# BeagleBone_Blue_3D.net
KiCad netlist of a schematic drawn in EAGLE
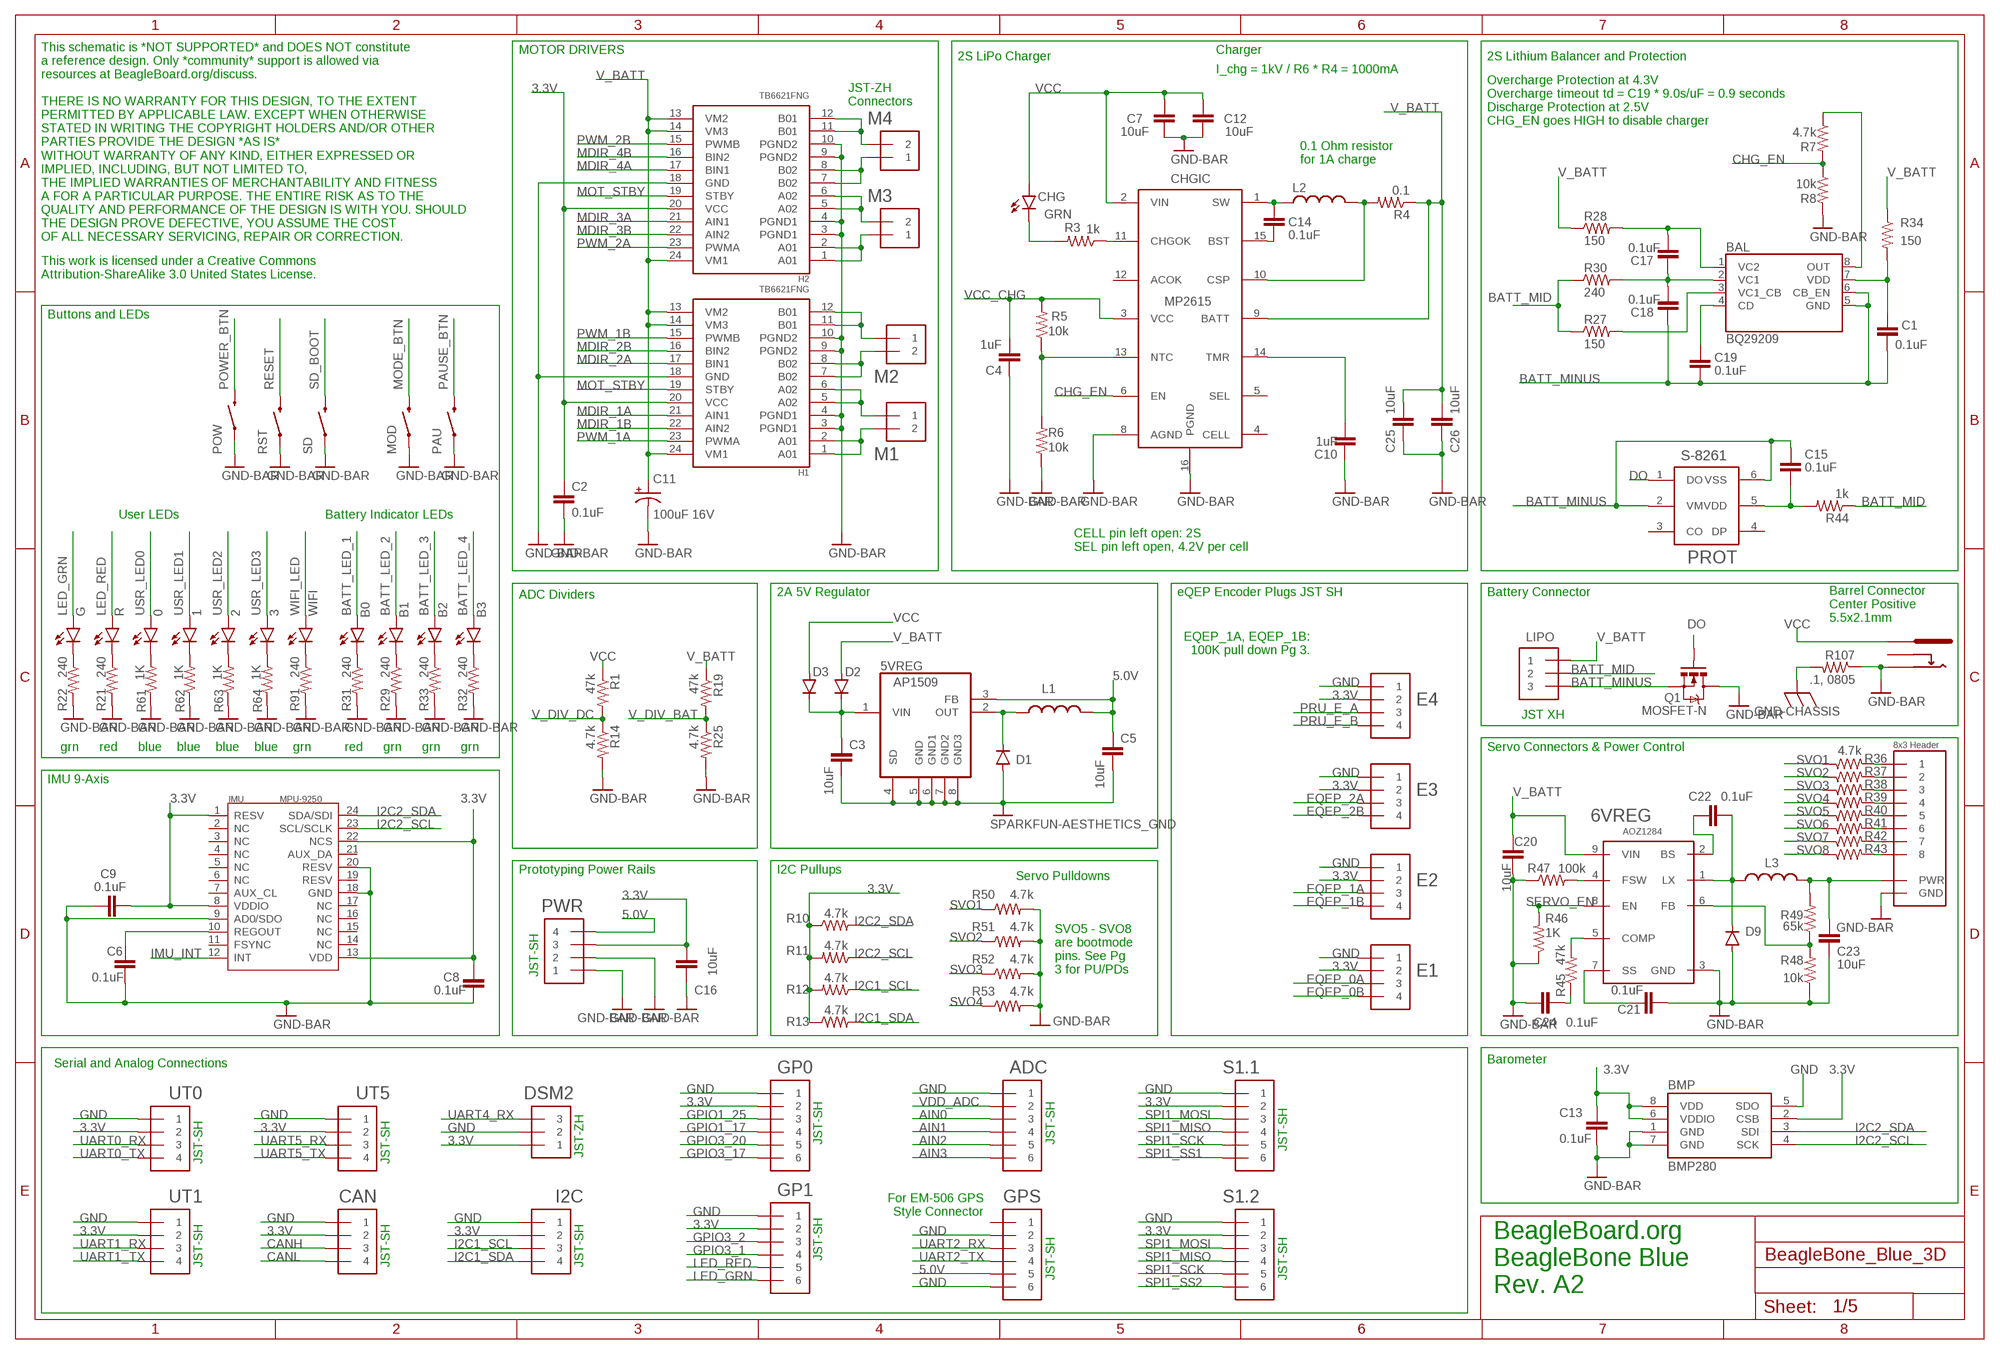
[diagram p0: schematic, sheet 1]
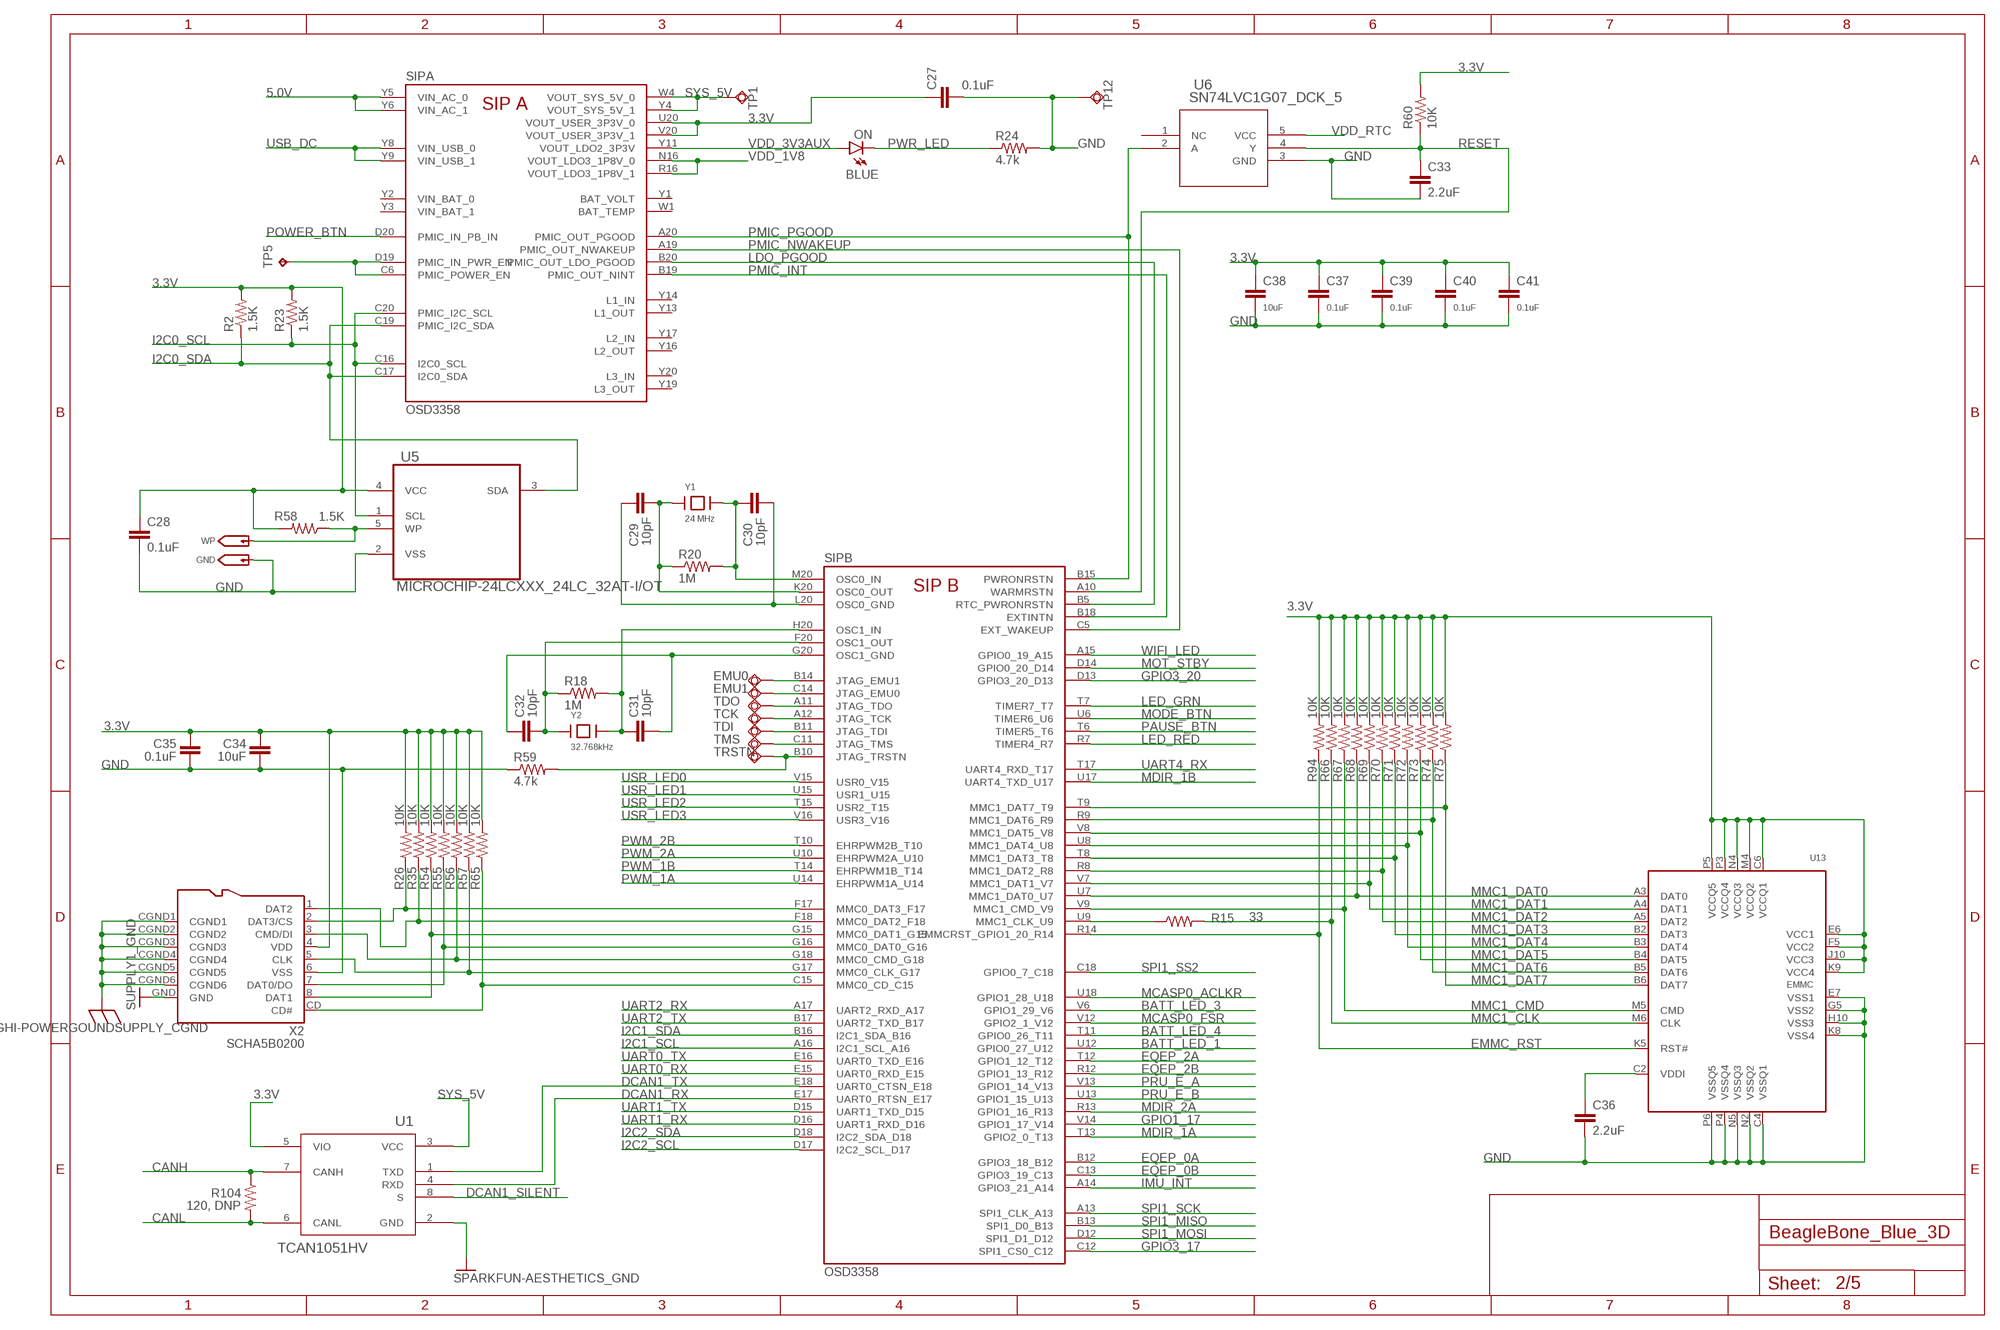
[diagram p1: schematic, sheet 2]
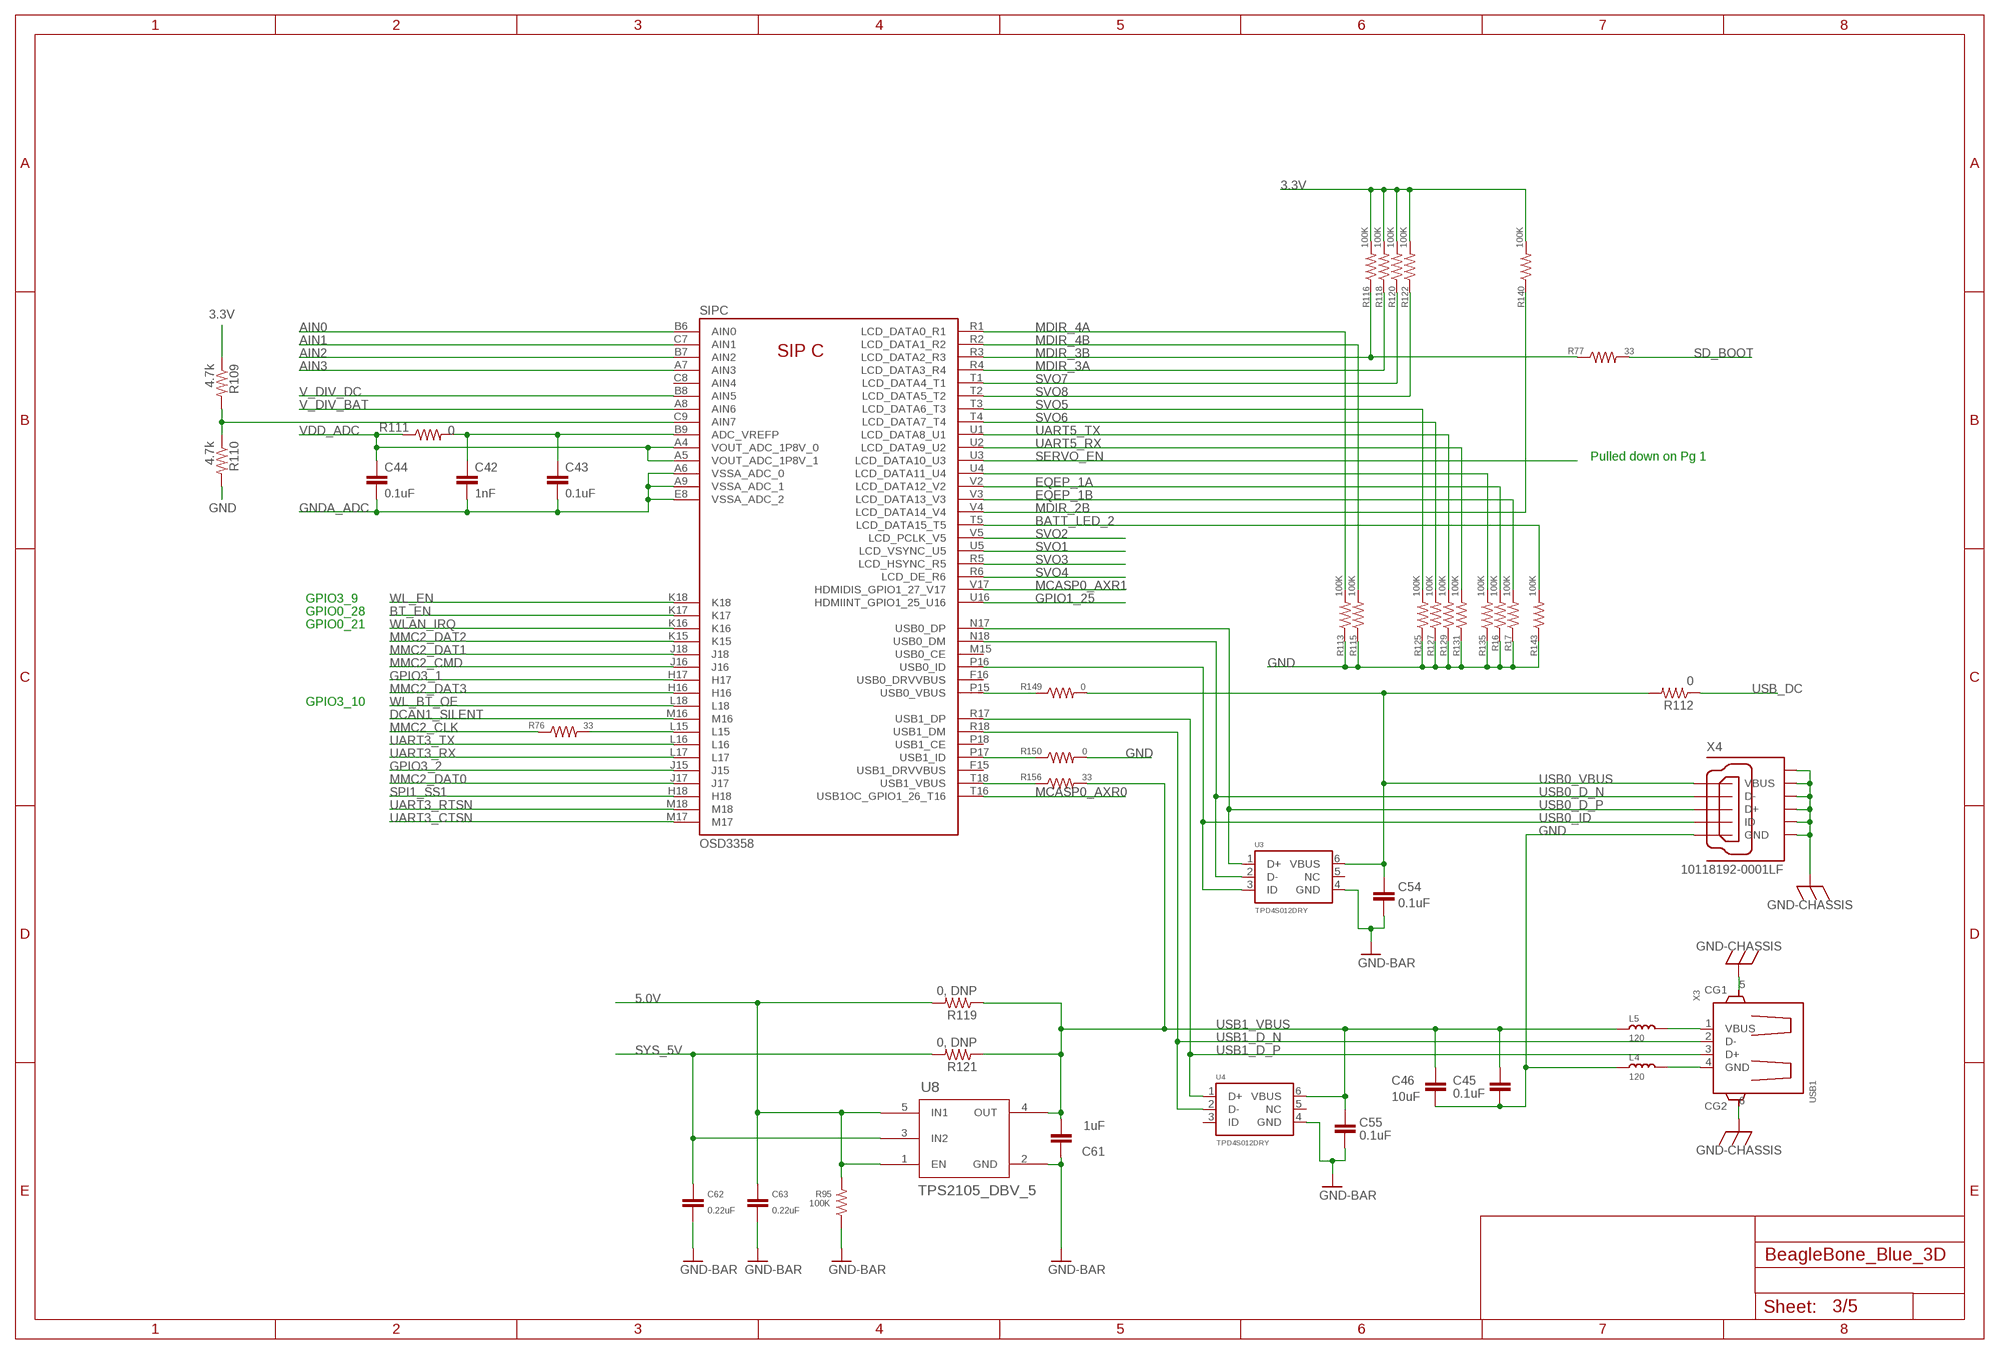
[diagram p2: schematic, sheet 3]
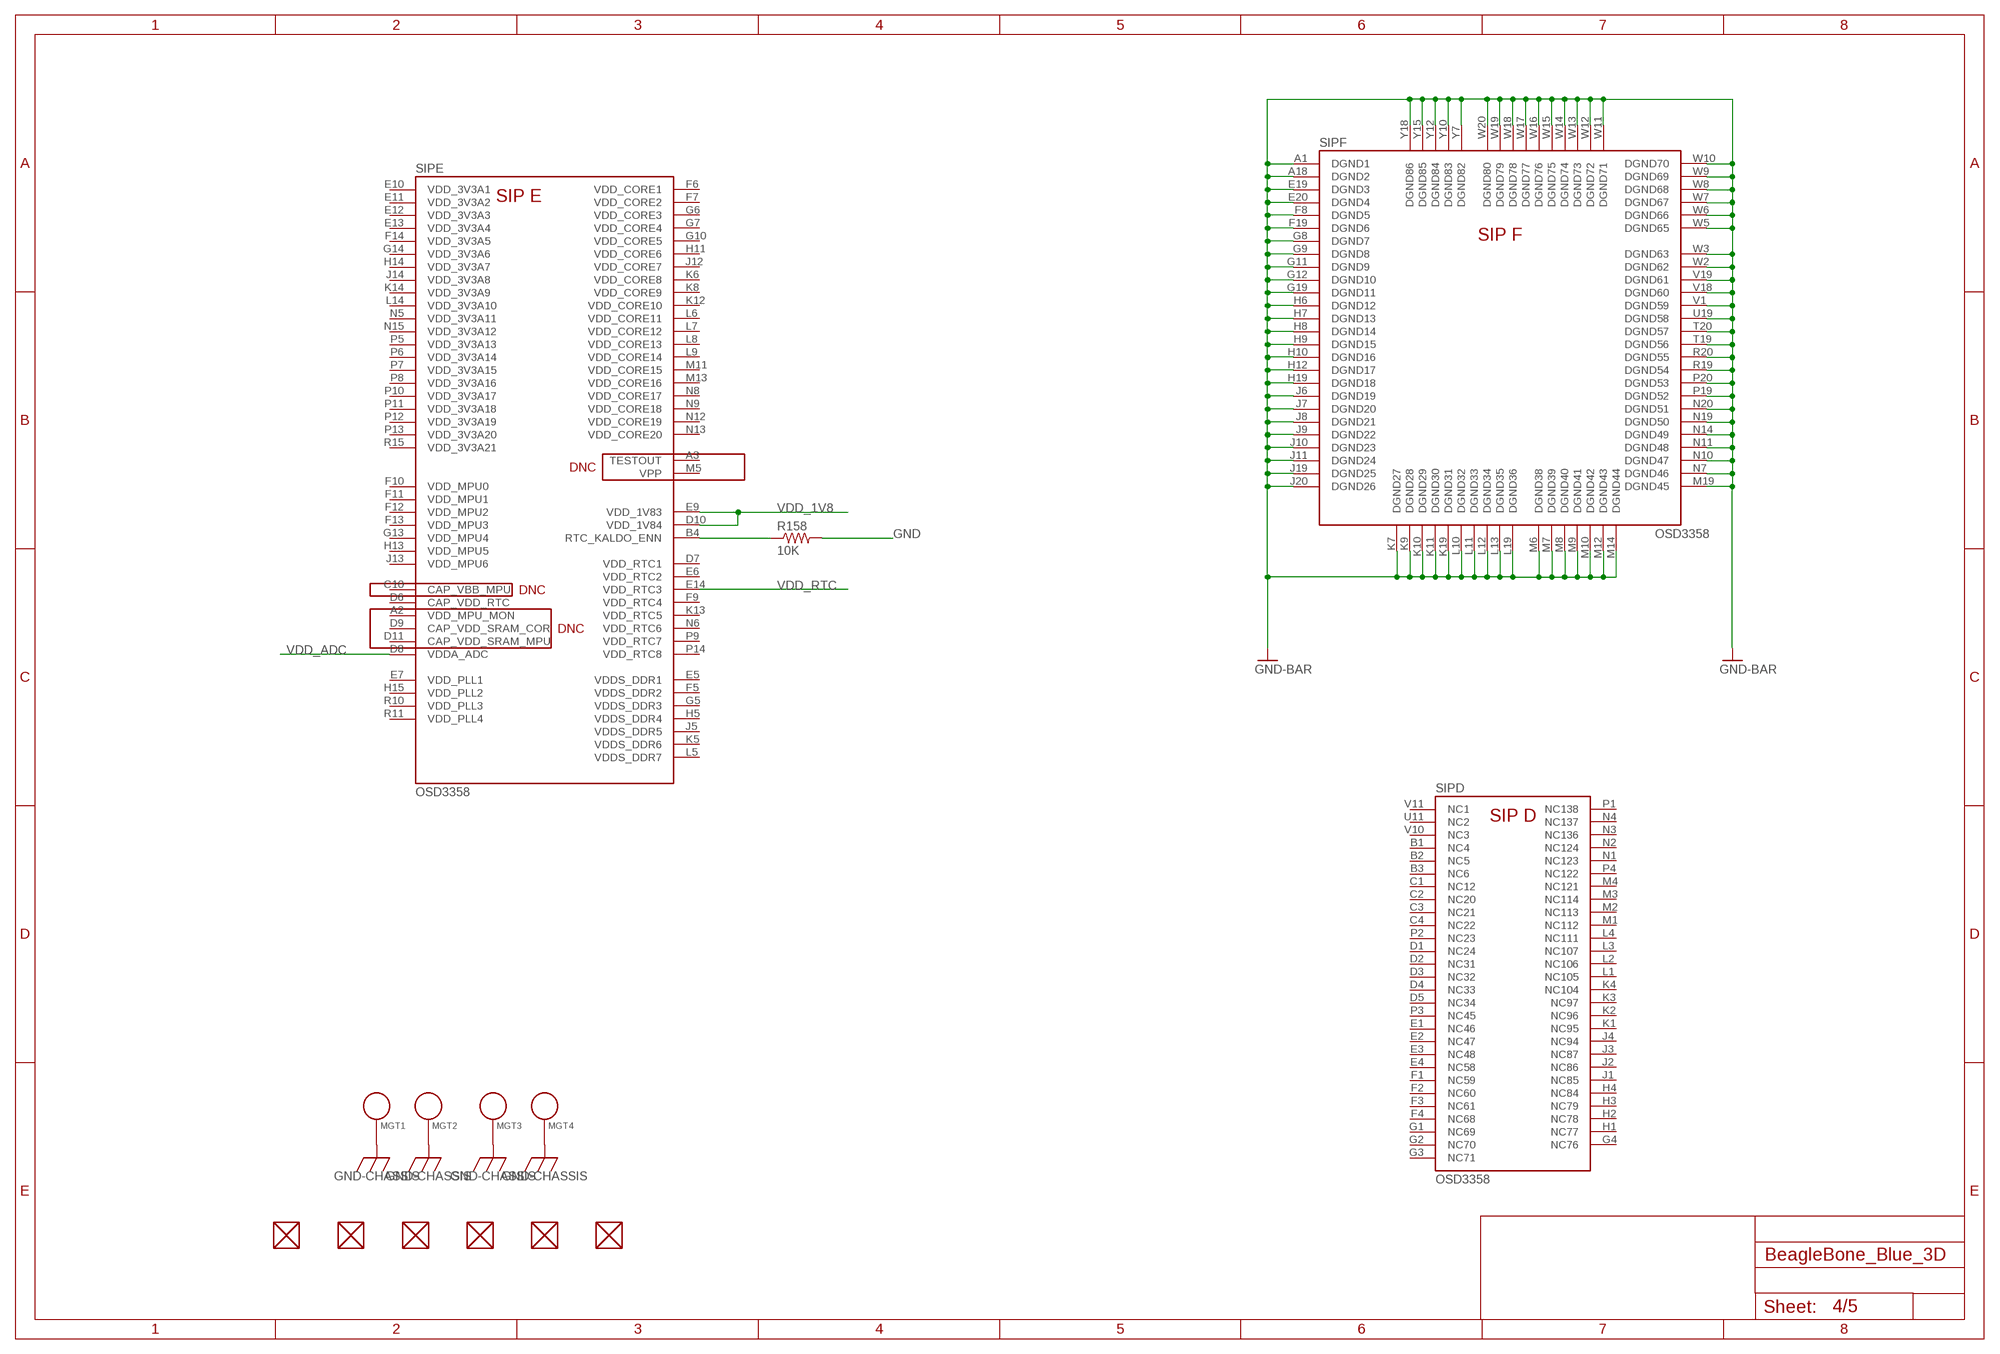
[diagram p3: schematic, sheet 4]
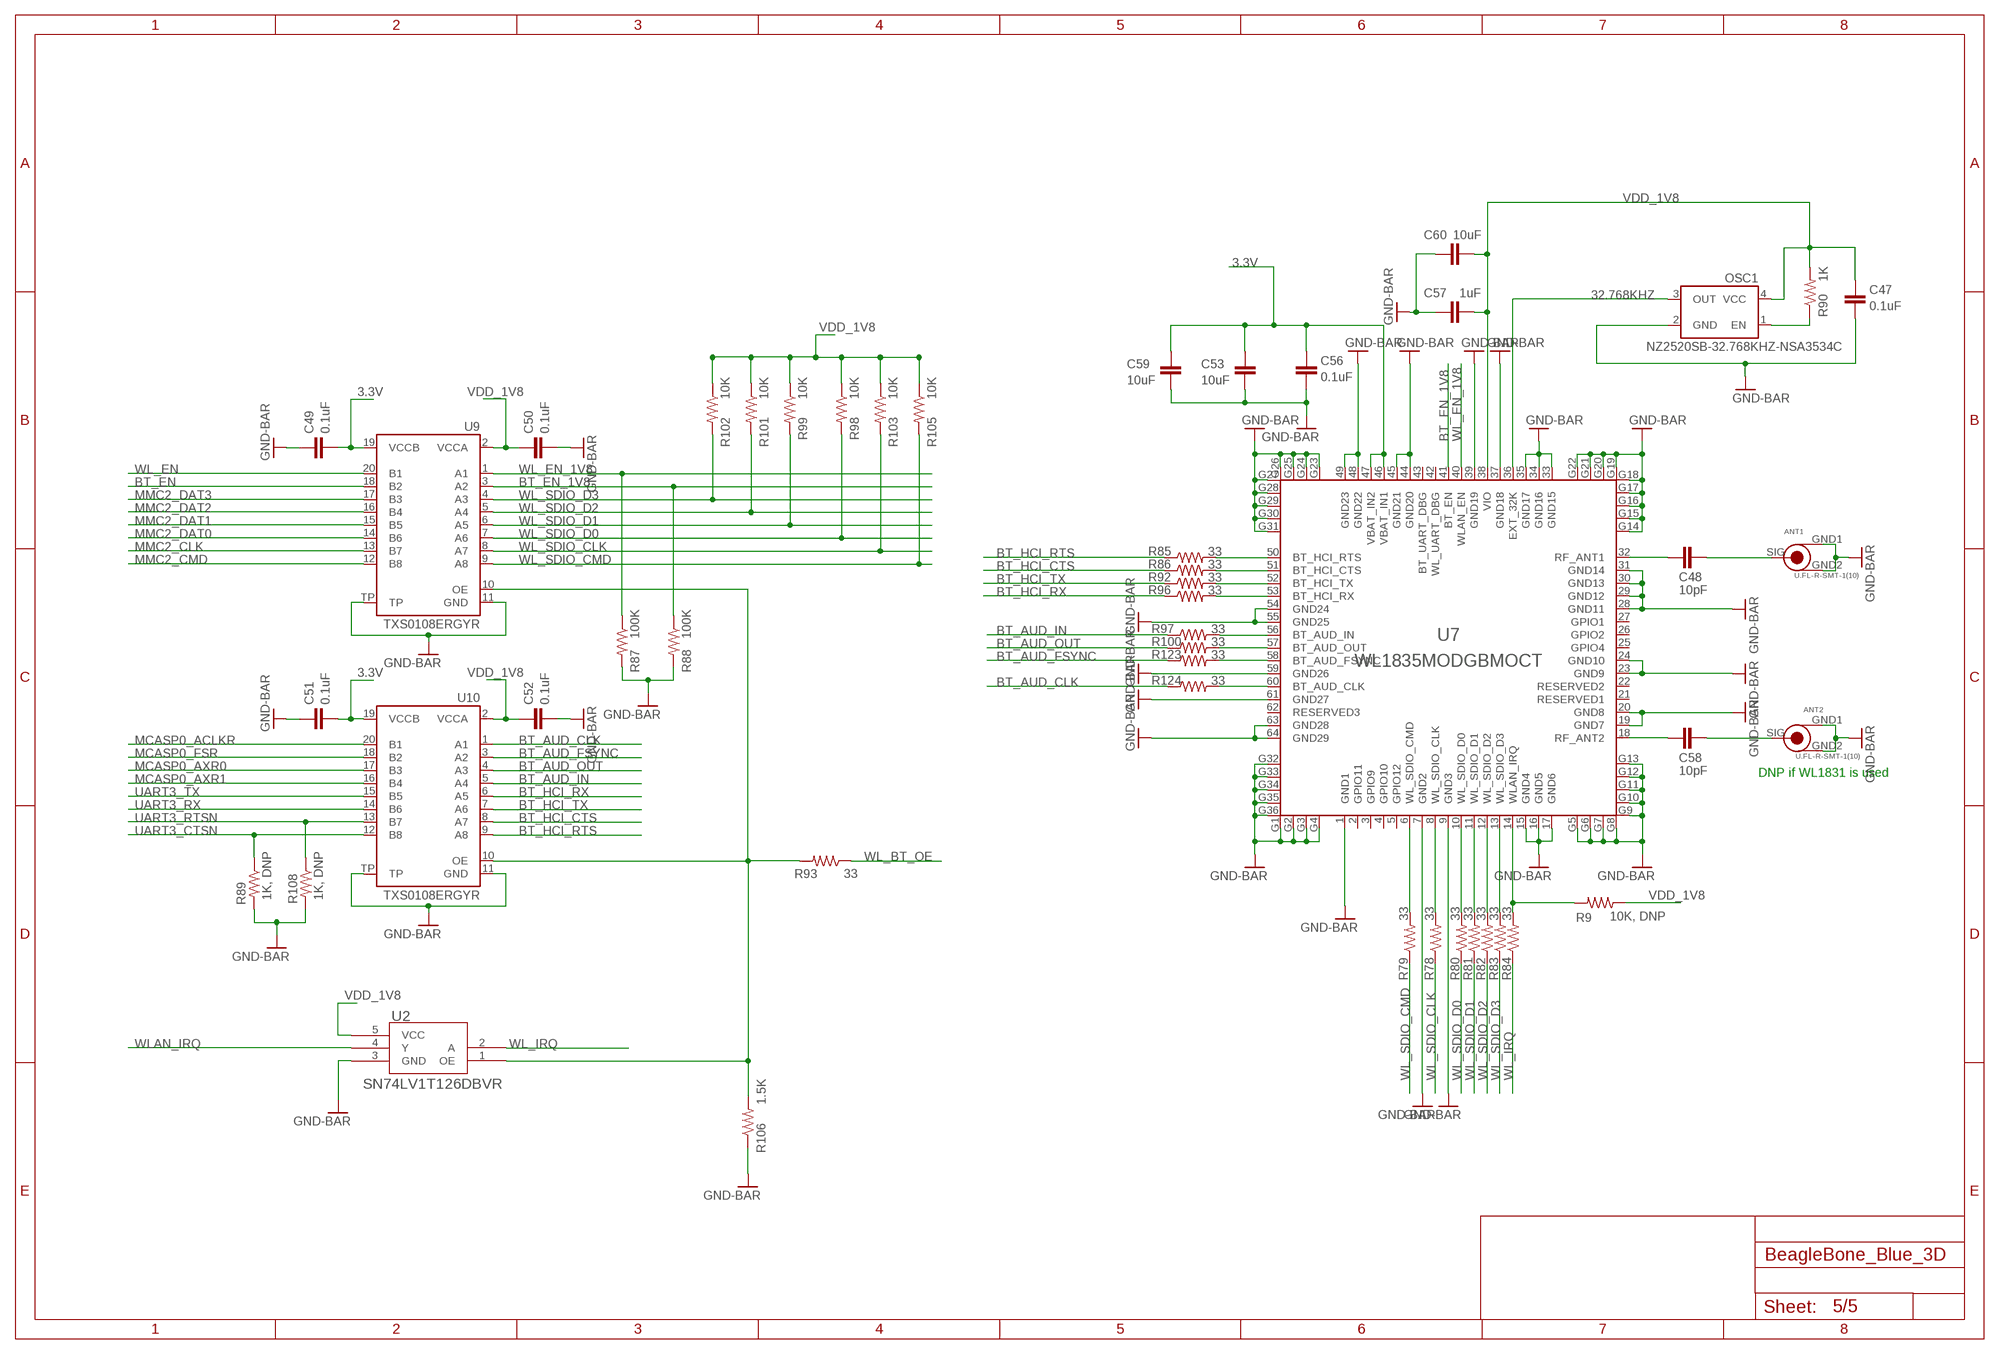
[diagram p4: schematic, sheet 5]

(export (version "E")
  (design (tool "Eeschema 10.0.6"))
  (components
    (comp (ref "FUD1")
      (value "FIDUCIAL")
      (footprint "eagle-import:GHI_FIDUCIAL_40MIL")
      (libsource (lib "eagle-import") (part "FIDUCIAL"))
    )
    (comp (ref "FUD2")
      (value "FIDUCIAL")
      (footprint "eagle-import:GHI_FIDUCIAL_40MIL")
      (libsource (lib "eagle-import") (part "FIDUCIAL"))
    )
    (comp (ref "FUD3")
      (value "FIDUCIAL")
      (footprint "eagle-import:GHI_FIDUCIAL_40MIL")
      (libsource (lib "eagle-import") (part "FIDUCIAL"))
    )
    (comp (ref "FUD4")
      (value "FIDUCIAL")
      (footprint "eagle-import:GHI_FIDUCIAL_40MIL")
      (libsource (lib "eagle-import") (part "FIDUCIAL"))
    )
    (comp (ref "FUD5")
      (value "FIDUCIAL")
      (footprint "eagle-import:GHI_FIDUCIAL_40MIL")
      (libsource (lib "eagle-import") (part "FIDUCIAL"))
    )
    (comp (ref "FUD6")
      (value "FIDUCIAL")
      (footprint "eagle-import:GHI_FIDUCIAL_40MIL")
      (libsource (lib "eagle-import") (part "FIDUCIAL"))
    )
    (comp (ref "MGT1")
      (value "MOUNTING_HOLE")
      (footprint "eagle-import:BEAGLEBONEBLACK_MOUNTING_HOLE")
      (libsource (lib "eagle-import") (part "MOUNTING_HOLE"))
    )
    (comp (ref "MGT2")
      (value "MOUNTING_HOLE")
      (footprint "eagle-import:BEAGLEBONEBLACK_MOUNTING_HOLE")
      (libsource (lib "eagle-import") (part "MOUNTING_HOLE"))
    )
    (comp (ref "MGT3")
      (value "MOUNTING_HOLE")
      (footprint "eagle-import:BEAGLEBONEBLACK_MOUNTING_HOLE")
      (libsource (lib "eagle-import") (part "MOUNTING_HOLE"))
    )
    (comp (ref "MGT4")
      (value "MOUNTING_HOLE")
      (footprint "eagle-import:BEAGLEBONEBLACK_MOUNTING_HOLE")
      (libsource (lib "eagle-import") (part "MOUNTING_HOLE"))
    )
    (comp (ref "R158")
      (value "10K")
      (footprint "eagle-import:0402-RES")
      (libsource (lib "eagle-import") (part "RESISTOR0402"))
    )
    (comp (ref "SIP")
      (value "OSD3358")
      (footprint "eagle-import:OSD3358")
      (libsource (lib "eagle-import") (part "OSD3358"))
    )
    (comp (ref "ANT1")
      (value "U.FL-R-SMT-1(10)")
      (footprint "eagle-import:GHI-CONNECTORS_U.FL-R-SMT-1")
      (libsource (lib "eagle-import") (part "U.FL-R-SMT-1"))
    )
    (comp (ref "ANT2")
      (value "U.FL-R-SMT-1(10)")
      (footprint "eagle-import:GHI-CONNECTORS_U.FL-R-SMT-1")
      (libsource (lib "eagle-import") (part "U.FL-R-SMT-1"))
    )
    (comp (ref "C47")
      (value "0.1uF")
      (footprint "eagle-import:0402-CAP")
      (libsource (lib "eagle-import") (part "CAPACITOR-N0402"))
    )
    (comp (ref "C48")
      (value "10pF")
      (footprint "eagle-import:0402-CAP")
      (libsource (lib "eagle-import") (part "CAPACITOR-N0402"))
    )
    (comp (ref "C49")
      (value "0.1uF")
      (footprint "eagle-import:0402-CAP")
      (libsource (lib "eagle-import") (part "CAPACITOR-N0402"))
    )
    (comp (ref "C50")
      (value "0.1uF")
      (footprint "eagle-import:0402-CAP")
      (libsource (lib "eagle-import") (part "CAPACITOR-N0402"))
    )
    (comp (ref "C51")
      (value "0.1uF")
      (footprint "eagle-import:0402-CAP")
      (libsource (lib "eagle-import") (part "CAPACITOR-N0402"))
    )
    (comp (ref "C52")
      (value "0.1uF")
      (footprint "eagle-import:0402-CAP")
      (libsource (lib "eagle-import") (part "CAPACITOR-N0402"))
    )
    (comp (ref "C53")
      (value "10uF")
      (footprint "eagle-import:0805")
      (libsource (lib "eagle-import") (part "CAPACITOR-N0805"))
    )
    (comp (ref "C56")
      (value "0.1uF")
      (footprint "eagle-import:0402-CAP")
      (libsource (lib "eagle-import") (part "CAPACITOR-N0402"))
    )
    (comp (ref "C57")
      (value "1uF")
      (footprint "eagle-import:0402-CAP")
      (libsource (lib "eagle-import") (part "CAPACITOR-N0402"))
    )
    (comp (ref "C58")
      (value "10pF")
      (footprint "eagle-import:0402-CAP")
      (libsource (lib "eagle-import") (part "CAPACITOR-N0402"))
    )
    (comp (ref "C59")
      (value "10uF")
      (footprint "eagle-import:0805")
      (libsource (lib "eagle-import") (part "CAPACITOR-N0805"))
    )
    (comp (ref "C60")
      (value "10uF")
      (footprint "eagle-import:0805")
      (libsource (lib "eagle-import") (part "CAPACITOR-N0805"))
    )
    (comp (ref "OSC1")
      (value "NZ2520SB-32.768KHZ-NSA3534C")
      (footprint "eagle-import:NZ2520S")
      (libsource (lib "eagle-import") (part "OSCILLATOR"))
    )
    (comp (ref "R9")
      (value "10K, DNP")
      (footprint "eagle-import:0402-RES")
      (libsource (lib "eagle-import") (part "RESISTOR0402"))
    )
    (comp (ref "R78")
      (value "33")
      (footprint "eagle-import:0402-RES")
      (libsource (lib "eagle-import") (part "RESISTOR0402"))
    )
    (comp (ref "R79")
      (value "33")
      (footprint "eagle-import:0402-RES")
      (libsource (lib "eagle-import") (part "RESISTOR0402"))
    )
    (comp (ref "R80")
      (value "33")
      (footprint "eagle-import:0402-RES")
      (libsource (lib "eagle-import") (part "RESISTOR0402"))
    )
    (comp (ref "R81")
      (value "33")
      (footprint "eagle-import:0402-RES")
      (libsource (lib "eagle-import") (part "RESISTOR0402"))
    )
    (comp (ref "R82")
      (value "33")
      (footprint "eagle-import:0402-RES")
      (libsource (lib "eagle-import") (part "RESISTOR0402"))
    )
    (comp (ref "R83")
      (value "33")
      (footprint "eagle-import:0402-RES")
      (libsource (lib "eagle-import") (part "RESISTOR0402"))
    )
    (comp (ref "R84")
      (value "33")
      (footprint "eagle-import:0402-RES")
      (libsource (lib "eagle-import") (part "RESISTOR0402"))
    )
    (comp (ref "R85")
      (value "33")
      (footprint "eagle-import:0402-RES")
      (libsource (lib "eagle-import") (part "RESISTOR0402"))
    )
    (comp (ref "R86")
      (value "33")
      (footprint "eagle-import:0402-RES")
      (libsource (lib "eagle-import") (part "RESISTOR0402"))
    )
    (comp (ref "R87")
      (value "100K")
      (footprint "eagle-import:0402-RES")
      (libsource (lib "eagle-import") (part "RESISTOR0402"))
    )
    (comp (ref "R88")
      (value "100K")
      (footprint "eagle-import:0402-RES")
      (libsource (lib "eagle-import") (part "RESISTOR0402"))
    )
    (comp (ref "R89")
      (value "1K, DNP")
      (footprint "eagle-import:0402-RES")
      (libsource (lib "eagle-import") (part "RESISTOR0402"))
    )
    (comp (ref "R90")
      (value "1K")
      (footprint "eagle-import:0402-RES")
      (libsource (lib "eagle-import") (part "RESISTOR0402"))
    )
    (comp (ref "R92")
      (value "33")
      (footprint "eagle-import:0402-RES")
      (libsource (lib "eagle-import") (part "RESISTOR0402"))
    )
    (comp (ref "R93")
      (value "33")
      (footprint "eagle-import:0402-RES")
      (libsource (lib "eagle-import") (part "RESISTOR0402"))
    )
    (comp (ref "R96")
      (value "33")
      (footprint "eagle-import:0402-RES")
      (libsource (lib "eagle-import") (part "RESISTOR0402"))
    )
    (comp (ref "R97")
      (value "33")
      (footprint "eagle-import:0402-RES")
      (libsource (lib "eagle-import") (part "RESISTOR0402"))
    )
    (comp (ref "R98")
      (value "10K")
      (footprint "eagle-import:0402-RES")
      (libsource (lib "eagle-import") (part "RESISTOR0402"))
    )
    (comp (ref "R99")
      (value "10K")
      (footprint "eagle-import:0402-RES")
      (libsource (lib "eagle-import") (part "RESISTOR0402"))
    )
    (comp (ref "R100")
      (value "33")
      (footprint "eagle-import:0402-RES")
      (libsource (lib "eagle-import") (part "RESISTOR0402"))
    )
    (comp (ref "R101")
      (value "10K")
      (footprint "eagle-import:0402-RES")
      (libsource (lib "eagle-import") (part "RESISTOR0402"))
    )
    (comp (ref "R102")
      (value "10K")
      (footprint "eagle-import:0402-RES")
      (libsource (lib "eagle-import") (part "RESISTOR0402"))
    )
    (comp (ref "R103")
      (value "10K")
      (footprint "eagle-import:0402-RES")
      (libsource (lib "eagle-import") (part "RESISTOR0402"))
    )
    (comp (ref "R105")
      (value "10K")
      (footprint "eagle-import:0402-RES")
      (libsource (lib "eagle-import") (part "RESISTOR0402"))
    )
    (comp (ref "R106")
      (value "1.5K")
      (footprint "eagle-import:0402-RES")
      (libsource (lib "eagle-import") (part "RESISTOR0402"))
    )
    (comp (ref "R108")
      (value "1K, DNP")
      (footprint "eagle-import:0402-RES")
      (libsource (lib "eagle-import") (part "RESISTOR0402"))
    )
    (comp (ref "R123")
      (value "33")
      (footprint "eagle-import:0402-RES")
      (libsource (lib "eagle-import") (part "RESISTOR0402"))
    )
    (comp (ref "R124")
      (value "33")
      (footprint "eagle-import:0402-RES")
      (libsource (lib "eagle-import") (part "RESISTOR0402"))
    )
    (comp (ref "U2")
      (value "SN74LV1T126DBVR")
      (footprint "eagle-import:SOT95P280X145-5")
      (libsource (lib "eagle-import") (part "SN74LV1T126DBVR"))
    )
    (comp (ref "U7")
      (value "WL1835MODGBMOCT")
      (footprint "eagle-import:MOC-100(TI)")
      (libsource (lib "eagle-import") (part "WL1835MOD"))
    )
    (comp (ref "U9")
      (value "TXS0108ERGYR")
      (footprint "eagle-import:R-PVQFN-N20(TI)")
      (libsource (lib "eagle-import") (part "TXS0108ERGYR"))
    )
    (comp (ref "U10")
      (value "TXS0108ERGYR")
      (footprint "eagle-import:R-PVQFN-N20(TI)")
      (libsource (lib "eagle-import") (part "TXS0108ERGYR"))
    )
    (comp (ref "C27")
      (value "0.1uF")
      (footprint "eagle-import:0402-CAP")
      (libsource (lib "eagle-import") (part "CAPACITOR-N0402"))
    )
    (comp (ref "C28")
      (value "0.1uF")
      (footprint "eagle-import:0402-CAP")
      (libsource (lib "eagle-import") (part "CAPACITOR-N0402"))
    )
    (comp (ref "C29")
      (value "10pF")
      (footprint "eagle-import:0402-CAP")
      (libsource (lib "eagle-import") (part "CAPACITOR-N0402"))
    )
    (comp (ref "C30")
      (value "10pF")
      (footprint "eagle-import:0402-CAP")
      (libsource (lib "eagle-import") (part "CAPACITOR-N0402"))
    )
    (comp (ref "C31")
      (value "10pF")
      (footprint "eagle-import:0402-CAP")
      (libsource (lib "eagle-import") (part "CAPACITOR-N0402"))
    )
    (comp (ref "C32")
      (value "10pF")
      (footprint "eagle-import:0402-CAP")
      (libsource (lib "eagle-import") (part "CAPACITOR-N0402"))
    )
    (comp (ref "C33")
      (value "2.2uF")
      (footprint "eagle-import:0402-CAP")
      (libsource (lib "eagle-import") (part "CAPACITOR-N0402"))
    )
    (comp (ref "C34")
      (value "10uF")
      (footprint "eagle-import:0805")
      (libsource (lib "eagle-import") (part "CAPACITOR-N0805"))
    )
    (comp (ref "C35")
      (value "0.1uF")
      (footprint "eagle-import:0402-CAP")
      (libsource (lib "eagle-import") (part "CAPACITOR-N0402"))
    )
    (comp (ref "C36")
      (value "2.2uF")
      (footprint "eagle-import:0402-CAP")
      (libsource (lib "eagle-import") (part "CAPACITOR-N0402"))
    )
    (comp (ref "C37")
      (value "0.1uF")
      (footprint "eagle-import:0402-CAP")
      (libsource (lib "eagle-import") (part "CAPACITOR-N0402"))
    )
    (comp (ref "C38")
      (value "10uF")
      (footprint "eagle-import:0805")
      (libsource (lib "eagle-import") (part "CAPACITOR-N0805"))
    )
    (comp (ref "C39")
      (value "0.1uF")
      (footprint "eagle-import:0402-CAP")
      (libsource (lib "eagle-import") (part "CAPACITOR-N0402"))
    )
    (comp (ref "C40")
      (value "0.1uF")
      (footprint "eagle-import:0402-CAP")
      (libsource (lib "eagle-import") (part "CAPACITOR-N0402"))
    )
    (comp (ref "C41")
      (value "0.1uF")
      (footprint "eagle-import:0402-CAP")
      (libsource (lib "eagle-import") (part "CAPACITOR-N0402"))
    )
    (comp (ref "EMU0")
      (value "TESTPAD_TPSQB1,27")
      (footprint "eagle-import:TESTPAD_B1,27")
      (libsource (lib "eagle-import") (part "TESTPAD_TPSQB1,27"))
    )
    (comp (ref "EMU1")
      (value "TESTPAD_TPSQB1,27")
      (footprint "eagle-import:TESTPAD_B1,27")
      (libsource (lib "eagle-import") (part "TESTPAD_TPSQB1,27"))
    )
    (comp (ref "GND")
      (value "TESTPAD/W_HOLE_1X1")
      (footprint "eagle-import:DIODE_GHI2_TESTPAD_W_HOLE_1X1")
      (libsource (lib "eagle-import") (part "TESTPAD/W_HOLE_1X1"))
    )
    (comp (ref "ON")
      (value "BLUE")
      (footprint "eagle-import:BEAGLEBONE_BLUE_BEAGLEBONE_BLUE_LED-0603")
      (libsource (lib "eagle-import") (part "BEAGLEBONE_BLUE_LED0603"))
    )
    (comp (ref "R2")
      (value "1.5K")
      (footprint "eagle-import:0402-RES")
      (libsource (lib "eagle-import") (part "RESISTOR0402"))
    )
    (comp (ref "R15")
      (value "33")
      (footprint "eagle-import:0402-RES")
      (libsource (lib "eagle-import") (part "RESISTOR0402"))
    )
    (comp (ref "R18")
      (value "1M")
      (footprint "eagle-import:0402-RES")
      (libsource (lib "eagle-import") (part "RESISTOR0402"))
    )
    (comp (ref "R20")
      (value "1M")
      (footprint "eagle-import:0402-RES")
      (libsource (lib "eagle-import") (part "RESISTOR0402"))
    )
    (comp (ref "R23")
      (value "1.5K")
      (footprint "eagle-import:0402-RES")
      (libsource (lib "eagle-import") (part "RESISTOR0402"))
    )
    (comp (ref "R24")
      (value "4.7k")
      (footprint "eagle-import:0402-RES")
      (libsource (lib "eagle-import") (part "RESISTOR0402"))
    )
    (comp (ref "R26")
      (value "10K")
      (footprint "eagle-import:0402-RES")
      (libsource (lib "eagle-import") (part "RESISTOR0402"))
    )
    (comp (ref "R35")
      (value "10K")
      (footprint "eagle-import:0402-RES")
      (libsource (lib "eagle-import") (part "RESISTOR0402"))
    )
    (comp (ref "R54")
      (value "10K")
      (footprint "eagle-import:0402-RES")
      (libsource (lib "eagle-import") (part "RESISTOR0402"))
    )
    (comp (ref "R55")
      (value "10K")
      (footprint "eagle-import:0402-RES")
      (libsource (lib "eagle-import") (part "RESISTOR0402"))
    )
    (comp (ref "R56")
      (value "10K")
      (footprint "eagle-import:0402-RES")
      (libsource (lib "eagle-import") (part "RESISTOR0402"))
    )
    (comp (ref "R57")
      (value "10K")
      (footprint "eagle-import:0402-RES")
      (libsource (lib "eagle-import") (part "RESISTOR0402"))
    )
    (comp (ref "R58")
      (value "1.5K")
      (footprint "eagle-import:0402-RES")
      (libsource (lib "eagle-import") (part "RESISTOR0402"))
    )
    (comp (ref "R59")
      (value "4.7k")
      (footprint "eagle-import:0402-RES")
      (libsource (lib "eagle-import") (part "RESISTOR0402"))
    )
    (comp (ref "R60")
      (value "10K")
      (footprint "eagle-import:0402-RES")
      (libsource (lib "eagle-import") (part "RESISTOR0402"))
    )
    (comp (ref "R65")
      (value "10K")
      (footprint "eagle-import:0402-RES")
      (libsource (lib "eagle-import") (part "RESISTOR0402"))
    )
    (comp (ref "R66")
      (value "10K")
      (footprint "eagle-import:0402-RES")
      (libsource (lib "eagle-import") (part "RESISTOR0402"))
    )
    (comp (ref "R67")
      (value "10K")
      (footprint "eagle-import:0402-RES")
      (libsource (lib "eagle-import") (part "RESISTOR0402"))
    )
    (comp (ref "R68")
      (value "10K")
      (footprint "eagle-import:0402-RES")
      (libsource (lib "eagle-import") (part "RESISTOR0402"))
    )
    (comp (ref "R69")
      (value "10K")
      (footprint "eagle-import:0402-RES")
      (libsource (lib "eagle-import") (part "RESISTOR0402"))
    )
    (comp (ref "R70")
      (value "10K")
      (footprint "eagle-import:0402-RES")
      (libsource (lib "eagle-import") (part "RESISTOR0402"))
    )
    (comp (ref "R71")
      (value "10K")
      (footprint "eagle-import:0402-RES")
      (libsource (lib "eagle-import") (part "RESISTOR0402"))
    )
    (comp (ref "R72")
      (value "10K")
      (footprint "eagle-import:0402-RES")
      (libsource (lib "eagle-import") (part "RESISTOR0402"))
    )
    (comp (ref "R73")
      (value "10K")
      (footprint "eagle-import:0402-RES")
      (libsource (lib "eagle-import") (part "RESISTOR0402"))
    )
    (comp (ref "R74")
      (value "10K")
      (footprint "eagle-import:0402-RES")
      (libsource (lib "eagle-import") (part "RESISTOR0402"))
    )
    (comp (ref "R75")
      (value "10K")
      (footprint "eagle-import:0402-RES")
      (libsource (lib "eagle-import") (part "RESISTOR0402"))
    )
    (comp (ref "R94")
      (value "10K")
      (footprint "eagle-import:0402-RES")
      (libsource (lib "eagle-import") (part "RESISTOR0402"))
    )
    (comp (ref "R104")
      (value "120, DNP")
      (footprint "eagle-import:R0603")
      (libsource (lib "eagle-import") (part "RESISTOR0603"))
    )
    (comp (ref "TCK")
      (value "TESTPAD_TPSQB1,27")
      (footprint "eagle-import:TESTPAD_B1,27")
      (libsource (lib "eagle-import") (part "TESTPAD_TPSQB1,27"))
    )
    (comp (ref "TDI")
      (value "TESTPAD_TPSQB1,27")
      (footprint "eagle-import:TESTPAD_B1,27")
      (libsource (lib "eagle-import") (part "TESTPAD_TPSQB1,27"))
    )
    (comp (ref "TDO")
      (value "TESTPAD_TPSQB1,27")
      (footprint "eagle-import:TESTPAD_B1,27")
      (libsource (lib "eagle-import") (part "TESTPAD_TPSQB1,27"))
    )
    (comp (ref "TMS")
      (value "TESTPAD_TPSQB1,27")
      (footprint "eagle-import:TESTPAD_B1,27")
      (libsource (lib "eagle-import") (part "TESTPAD_TPSQB1,27"))
    )
    (comp (ref "TP1")
      (value "TESTPAD_TPSQB1,27")
      (footprint "eagle-import:TESTPAD_B1,27")
      (libsource (lib "eagle-import") (part "TESTPAD_TPSQB1,27"))
    )
    (comp (ref "TP5")
      (value "TPB0,65")
      (footprint "eagle-import:B0,65")
      (libsource (lib "eagle-import") (part "TPB0,65"))
    )
    (comp (ref "TP12")
      (value "TESTPAD_TPSQB1,27")
      (footprint "eagle-import:TESTPAD_B1,27")
      (libsource (lib "eagle-import") (part "TESTPAD_TPSQB1,27"))
    )
    (comp (ref "TRSTN")
      (value "TESTPAD_TPSQB1,27")
      (footprint "eagle-import:TESTPAD_B1,27")
      (libsource (lib "eagle-import") (part "TESTPAD_TPSQB1,27"))
    )
    (comp (ref "U1")
      (value "TCAN1051HV")
      (footprint "eagle-import:D8")
      (fields
        (field (name "MANUFACTURER") "Texas Instruments")
        (field (name "MANUFACTURER_PART_NUMBER") "TCAN1051HVD")
      )
      (libsource (lib "eagle-import") (part "TCAN1051HV"))
    )
    (comp (ref "U5")
      (value "MICROCHIP-24LCXXX_24LC_32AT-I/OT")
      (footprint "eagle-import:MICROCHIP-24LCXXX_SOT95P290X145-5N")
      (fields (field (name "MPN") "24LC32AT-I/OT"))
      (libsource (lib "eagle-import") (part "MICROCHIP-24LCXXX_24LC_32AT-I/OT"))
    )
    (comp (ref "U6")
      (value "SN74LVC1G07_DCK_5")
      (footprint "eagle-import:DCK5")
      (fields
        (field (name "GENERIC_PART_NUMBER") "SN74LVC1G07")
        (field (name "MANUFACTURER") "Texas Instruments")
        (field (name "MANUFACTURER_PART_NUMBER") "sn74lvc1g07_dck_5")
      )
      (libsource (lib "eagle-import") (part "SN74LVC1G07_DCK_5"))
    )
    (comp (ref "U13")
      (value "EMMC")
      (footprint "eagle-import:MICRON_EMMC_153")
      (libsource (lib "eagle-import") (part "EMMC04G-S100-B08U"))
    )
    (comp (ref "WP")
      (value "TESTPAD/W_HOLE_1X1")
      (footprint "eagle-import:DIODE_GHI2_TESTPAD_W_HOLE_1X1")
      (libsource (lib "eagle-import") (part "TESTPAD/W_HOLE_1X1"))
    )
    (comp (ref "X2")
      (value "SCHA5B0200")
      (footprint "eagle-import:GHI-CONNECTORS_SCHA5B0200")
      (libsource (lib "eagle-import") (part "SCHA5B0200(ALPS_USD)"))
    )
    (comp (ref "Y1")
      (value "24 MHz")
      (footprint "eagle-import:GHI2_CRYSTAL_5X3.2MM")
      (libsource (lib "eagle-import") (part "CRYSTAL_5X3.2MM"))
    )
    (comp (ref "Y2")
      (value "32.768kHz")
      (footprint "eagle-import:GHI2_CRYSTAL_3.2X1.5")
      (libsource (lib "eagle-import") (part "CRYSTAL_3.2X1.5"))
    )
    (comp (ref "C42")
      (value "1nF")
      (footprint "eagle-import:0402-CAP")
      (libsource (lib "eagle-import") (part "CAPACITOR-N0402"))
    )
    (comp (ref "C43")
      (value "0.1uF")
      (footprint "eagle-import:0402-CAP")
      (libsource (lib "eagle-import") (part "CAPACITOR-N0402"))
    )
    (comp (ref "C44")
      (value "0.1uF")
      (footprint "eagle-import:0402-CAP")
      (libsource (lib "eagle-import") (part "CAPACITOR-N0402"))
    )
    (comp (ref "C45")
      (value "0.1uF")
      (footprint "eagle-import:0402-CAP")
      (libsource (lib "eagle-import") (part "CAPACITOR-N0402"))
    )
    (comp (ref "C46")
      (value "10uF")
      (footprint "eagle-import:0805")
      (libsource (lib "eagle-import") (part "CAPACITOR-N0805"))
    )
    (comp (ref "C54")
      (value "0.1uF")
      (footprint "eagle-import:0402-CAP")
      (libsource (lib "eagle-import") (part "CAPACITOR-N0402"))
    )
    (comp (ref "C55")
      (value "0.1uF")
      (footprint "eagle-import:0402-CAP")
      (libsource (lib "eagle-import") (part "CAPACITOR-N0402"))
    )
    (comp (ref "C61")
      (value "1uF")
      (footprint "eagle-import:0402-CAP")
      (libsource (lib "eagle-import") (part "CAPACITOR-N0402"))
    )
    (comp (ref "C62")
      (value "0.22uF")
      (footprint "eagle-import:0402-CAP")
      (libsource (lib "eagle-import") (part "CAPACITOR-N0402"))
    )
    (comp (ref "C63")
      (value "0.22uF")
      (footprint "eagle-import:0402-CAP")
      (libsource (lib "eagle-import") (part "CAPACITOR-N0402"))
    )
    (comp (ref "L4")
      (value "120")
      (footprint "eagle-import:INDUCTOR_L0603")
      (libsource (lib "eagle-import") (part "INDUCTOR/FERRITE-BEAD0603"))
    )
    (comp (ref "L5")
      (value "120")
      (footprint "eagle-import:INDUCTOR_L0603")
      (libsource (lib "eagle-import") (part "INDUCTOR/FERRITE-BEAD0603"))
    )
    (comp (ref "R16")
      (value "100K")
      (footprint "eagle-import:0402-RES")
      (libsource (lib "eagle-import") (part "RESISTOR0402"))
    )
    (comp (ref "R17")
      (value "100K")
      (footprint "eagle-import:0402-RES")
      (libsource (lib "eagle-import") (part "RESISTOR0402"))
    )
    (comp (ref "R76")
      (value "33")
      (footprint "eagle-import:0402-RES")
      (libsource (lib "eagle-import") (part "RESISTOR0402"))
    )
    (comp (ref "R77")
      (value "33")
      (footprint "eagle-import:0402-RES")
      (libsource (lib "eagle-import") (part "RESISTOR0402"))
    )
    (comp (ref "R95")
      (value "100K")
      (footprint "eagle-import:0402-RES")
      (libsource (lib "eagle-import") (part "RESISTOR0402"))
    )
    (comp (ref "R109")
      (value "4.7k")
      (footprint "eagle-import:0402-RES")
      (libsource (lib "eagle-import") (part "RESISTOR0402"))
    )
    (comp (ref "R110")
      (value "4.7k")
      (footprint "eagle-import:0402-RES")
      (libsource (lib "eagle-import") (part "RESISTOR0402"))
    )
    (comp (ref "R111")
      (value "0")
      (footprint "eagle-import:0402-RES")
      (libsource (lib "eagle-import") (part "RESISTOR0402"))
    )
    (comp (ref "R112")
      (value "0")
      (footprint "eagle-import:R0603")
      (libsource (lib "eagle-import") (part "RESISTOR0603"))
    )
    (comp (ref "R113")
      (value "100K")
      (footprint "eagle-import:0402-RES")
      (libsource (lib "eagle-import") (part "RESISTOR0402"))
    )
    (comp (ref "R115")
      (value "100K")
      (footprint "eagle-import:0402-RES")
      (libsource (lib "eagle-import") (part "RESISTOR0402"))
    )
    (comp (ref "R116")
      (value "100K")
      (footprint "eagle-import:0402-RES")
      (libsource (lib "eagle-import") (part "RESISTOR0402"))
    )
    (comp (ref "R118")
      (value "100K")
      (footprint "eagle-import:0402-RES")
      (libsource (lib "eagle-import") (part "RESISTOR0402"))
    )
    (comp (ref "R119")
      (value "0, DNP")
      (footprint "eagle-import:R0603")
      (libsource (lib "eagle-import") (part "RESISTOR0603"))
    )
    (comp (ref "R120")
      (value "100K")
      (footprint "eagle-import:0402-RES")
      (libsource (lib "eagle-import") (part "RESISTOR0402"))
    )
    (comp (ref "R121")
      (value "0, DNP")
      (footprint "eagle-import:R0603")
      (libsource (lib "eagle-import") (part "RESISTOR0603"))
    )
    (comp (ref "R122")
      (value "100K")
      (footprint "eagle-import:0402-RES")
      (libsource (lib "eagle-import") (part "RESISTOR0402"))
    )
    (comp (ref "R125")
      (value "100K")
      (footprint "eagle-import:0402-RES")
      (libsource (lib "eagle-import") (part "RESISTOR0402"))
    )
    (comp (ref "R127")
      (value "100K")
      (footprint "eagle-import:0402-RES")
      (libsource (lib "eagle-import") (part "RESISTOR0402"))
    )
    (comp (ref "R129")
      (value "100K")
      (footprint "eagle-import:0402-RES")
      (libsource (lib "eagle-import") (part "RESISTOR0402"))
    )
    (comp (ref "R131")
      (value "100K")
      (footprint "eagle-import:0402-RES")
      (libsource (lib "eagle-import") (part "RESISTOR0402"))
    )
    (comp (ref "R135")
      (value "100K")
      (footprint "eagle-import:0402-RES")
      (libsource (lib "eagle-import") (part "RESISTOR0402"))
    )
    (comp (ref "R140")
      (value "100K")
      (footprint "eagle-import:0402-RES")
      (libsource (lib "eagle-import") (part "RESISTOR0402"))
    )
    (comp (ref "R143")
      (value "100K")
      (footprint "eagle-import:0402-RES")
      (libsource (lib "eagle-import") (part "RESISTOR0402"))
    )
    (comp (ref "R149")
      (value "0")
      (footprint "eagle-import:0402-RES")
      (libsource (lib "eagle-import") (part "RESISTOR0402"))
    )
    (comp (ref "R150")
      (value "0")
      (footprint "eagle-import:0402-RES")
      (libsource (lib "eagle-import") (part "RESISTOR0402"))
    )
    (comp (ref "R156")
      (value "33")
      (footprint "eagle-import:0402-RES")
      (libsource (lib "eagle-import") (part "RESISTOR0402"))
    )
    (comp (ref "U3")
      (value "TPD4S012DRY")
      (footprint "eagle-import:SON-6(TI)-DRY")
      (libsource (lib "eagle-import") (part "TPD4S012DRYR"))
    )
    (comp (ref "U4")
      (value "TPD4S012DRY")
      (footprint "eagle-import:SON-6(TI)-DRY")
      (libsource (lib "eagle-import") (part "TPD4S012DRYR"))
    )
    (comp (ref "U8")
      (value "TPS2105_DBV_5")
      (footprint "eagle-import:DIODE_DBV5")
      (fields
        (field (name "GENERIC_PART_NUMBER") "TPS2105")
        (field (name "MANUFACTURER") "Texas Instruments")
        (field (name "MANUFACTURER_PART_NUMBER") "tps2105_dbv_5")
      )
      (libsource (lib "eagle-import") (part "TPS2105_DBV_5"))
    )
    (comp (ref "X3")
      (value "USB1")
      (footprint "eagle-import:GHI2_USB_HOST_HORIZONTAL_W_CHASSIS_GND")
      (libsource (lib "eagle-import") (part "USB_HOST_W/CHASSIS_GND"))
    )
    (comp (ref "X4")
      (value "10118192-0001LF")
      (footprint "eagle-import:GHI-CONNECTORS_10118192-0001LF(MICRO-USB-B-AMPHENOL-FCI)")
      (libsource (lib "eagle-import") (part "10118192-0001LF"))
    )
    (comp (ref "0")
      (value "BLUE")
      (footprint "eagle-import:0603-BLUE")
      (libsource (lib "eagle-import") (part "LED-BLUE0603"))
    )
    (comp (ref "1")
      (value "BLUE")
      (footprint "eagle-import:0603-BLUE")
      (libsource (lib "eagle-import") (part "LED-BLUE0603"))
    )
    (comp (ref "2")
      (value "BLUE")
      (footprint "eagle-import:0603-BLUE")
      (libsource (lib "eagle-import") (part "LED-BLUE0603"))
    )
    (comp (ref "3")
      (value "BLUE")
      (footprint "eagle-import:0603-BLUE")
      (libsource (lib "eagle-import") (part "LED-BLUE0603"))
    )
    (comp (ref "5VREG")
      (value "AP1509SOIC-8-TIGHT")
      (footprint "eagle-import:SO08-H")
      (libsource (lib "eagle-import") (part "AP1509SOIC-8-TIGHT"))
    )
    (comp (ref "6VREG")
      (value "AOZ1284")
      (footprint "eagle-import:SO08-EXPOSED")
      (libsource (lib "eagle-import") (part "AOZ1284"))
    )
    (comp (ref "12V")
      (value "PJ-102B_POWER_CON")
      (footprint "eagle-import:GHI_PJ-102B_POWER_CON")
      (libsource (lib "eagle-import") (part "PJ-102B_POWER_CON"))
    )
    (comp (ref "ADC")
      (value "JST_SH_6")
      (footprint "eagle-import:JST_SH_6")
      (libsource (lib "eagle-import") (part "JST_SH_6"))
    )
    (comp (ref "B0")
      (value "RED")
      (footprint "eagle-import:LED-0603")
      (libsource (lib "eagle-import") (part "BLUE_LED0603"))
    )
    (comp (ref "B1")
      (value "GREEN")
      (footprint "eagle-import:LED-0603")
      (libsource (lib "eagle-import") (part "BLUE_LED0603"))
    )
    (comp (ref "B2")
      (value "GREEN")
      (footprint "eagle-import:LED-0603")
      (libsource (lib "eagle-import") (part "BLUE_LED0603"))
    )
    (comp (ref "B3")
      (value "GREEN")
      (footprint "eagle-import:LED-0603")
      (libsource (lib "eagle-import") (part "BLUE_LED0603"))
    )
    (comp (ref "BAL")
      (value "BQ29209")
      (footprint "eagle-import:8-SON_3X3MM")
      (libsource (lib "eagle-import") (part "BQ29209"))
    )
    (comp (ref "BMP")
      (value "BMP280")
      (footprint "eagle-import:BMP280")
      (libsource (lib "eagle-import") (part "BMP280"))
    )
    (comp (ref "C1")
      (value "0.1uF")
      (footprint "eagle-import:0402-CAP")
      (libsource (lib "eagle-import") (part "CAPACITOR-N0402"))
    )
    (comp (ref "C2")
      (value "0.1uF")
      (footprint "eagle-import:0402-CAP")
      (libsource (lib "eagle-import") (part "CAPACITOR-N0402"))
    )
    (comp (ref "C3")
      (value "10uF")
      (footprint "eagle-import:0805")
      (libsource (lib "eagle-import") (part "CAPACITOR-N0805"))
    )
    (comp (ref "C4")
      (value "1uF")
      (footprint "eagle-import:0402-CAP")
      (libsource (lib "eagle-import") (part "CAPACITOR-N0402"))
    )
    (comp (ref "C5")
      (value "10uF")
      (footprint "eagle-import:0805")
      (libsource (lib "eagle-import") (part "CAPACITOR-N0805"))
    )
    (comp (ref "C6")
      (value "0.1uF")
      (footprint "eagle-import:0402-CAP")
      (libsource (lib "eagle-import") (part "CAPACITOR-N0402"))
    )
    (comp (ref "C7")
      (value "10uF")
      (footprint "eagle-import:0805")
      (libsource (lib "eagle-import") (part "CAPACITOR-N0805"))
    )
    (comp (ref "C8")
      (value "0.1uF")
      (footprint "eagle-import:0402-CAP")
      (libsource (lib "eagle-import") (part "CAPACITOR-N0402"))
    )
    (comp (ref "C9")
      (value "0.1uF")
      (footprint "eagle-import:0402-CAP")
      (libsource (lib "eagle-import") (part "CAPACITOR-N0402"))
    )
    (comp (ref "C10")
      (value "1uF")
      (footprint "eagle-import:0402-CAP")
      (libsource (lib "eagle-import") (part "CAPACITOR-N0402"))
    )
    (comp (ref "C11")
      (value "100uF 16V")
      (footprint "eagle-import:PANASONIC_D")
      (libsource (lib "eagle-import") (part "CAPACITOR-PD"))
    )
    (comp (ref "C12")
      (value "10uF")
      (footprint "eagle-import:0805")
      (libsource (lib "eagle-import") (part "CAPACITOR-N0805"))
    )
    (comp (ref "C13")
      (value "0.1uF")
      (footprint "eagle-import:0402-CAP")
      (libsource (lib "eagle-import") (part "CAPACITOR-N0402"))
    )
    (comp (ref "C14")
      (value "0.1uF")
      (footprint "eagle-import:0402-CAP")
      (libsource (lib "eagle-import") (part "CAPACITOR-N0402"))
    )
    (comp (ref "C15")
      (value "0.1uF")
      (footprint "eagle-import:0402-CAP")
      (libsource (lib "eagle-import") (part "CAPACITOR-N0402"))
    )
    (comp (ref "C16")
      (value "10uF")
      (footprint "eagle-import:0805")
      (libsource (lib "eagle-import") (part "CAPACITOR-N0805"))
    )
    (comp (ref "C17")
      (value "0.1uF")
      (footprint "eagle-import:0402-CAP")
      (libsource (lib "eagle-import") (part "CAPACITOR-N0402"))
    )
    (comp (ref "C18")
      (value "0.1uF")
      (footprint "eagle-import:0402-CAP")
      (libsource (lib "eagle-import") (part "CAPACITOR-N0402"))
    )
    (comp (ref "C19")
      (value "0.1uF")
      (footprint "eagle-import:0402-CAP")
      (libsource (lib "eagle-import") (part "CAPACITOR-N0402"))
    )
    (comp (ref "C20")
      (value "10uF")
      (footprint "eagle-import:0805")
      (libsource (lib "eagle-import") (part "CAPACITOR-N0805"))
    )
    (comp (ref "C21")
      (value "0.1uF")
      (footprint "eagle-import:0402-CAP")
      (libsource (lib "eagle-import") (part "CAPACITOR-N0402"))
    )
    (comp (ref "C22")
      (value "0.1uF")
      (footprint "eagle-import:0402-CAP")
      (libsource (lib "eagle-import") (part "CAPACITOR-N0402"))
    )
    (comp (ref "C23")
      (value "10uF")
      (footprint "eagle-import:0805")
      (libsource (lib "eagle-import") (part "CAPACITOR-N0805"))
    )
    (comp (ref "C24")
      (value "0.1uF")
      (footprint "eagle-import:0402-CAP")
      (libsource (lib "eagle-import") (part "CAPACITOR-N0402"))
    )
    (comp (ref "C25")
      (value "10uF")
      (footprint "eagle-import:0805")
      (libsource (lib "eagle-import") (part "CAPACITOR-N0805"))
    )
    (comp (ref "C26")
      (value "10uF")
      (footprint "eagle-import:0805")
      (libsource (lib "eagle-import") (part "CAPACITOR-N0805"))
    )
    (comp (ref "CAN")
      (value "JST_SH_4")
      (footprint "eagle-import:JST_SH_4_SMD")
      (libsource (lib "eagle-import") (part "JST_SH_4"))
    )
    (comp (ref "CHG")
      (value "GRN")
      (footprint "eagle-import:LED-0603")
      (libsource (lib "eagle-import") (part "BLUE_LED0603"))
    )
    (comp (ref "CHGIC")
      (value "MP2615")
      (footprint "eagle-import:QFN50P300X300X100-16")
      (libsource (lib "eagle-import") (part "MP2615"))
    )
    (comp (ref "D1")
      (value "DIODEDIODE-123FL")
      (footprint "eagle-import:DIODE_SOD-123FL")
      (libsource (lib "eagle-import") (part "DIODEDIODE-123FL"))
    )
    (comp (ref "D2")
      (value "DIODEDIODE-123FL")
      (footprint "eagle-import:DIODE_SOD-123FL")
      (libsource (lib "eagle-import") (part "DIODEDIODE-123FL"))
    )
    (comp (ref "D3")
      (value "DIODEDIODE-123FL")
      (footprint "eagle-import:DIODE_SOD-123FL")
      (libsource (lib "eagle-import") (part "DIODEDIODE-123FL"))
    )
    (comp (ref "D9")
      (value "DIODEDO214AA")
      (footprint "eagle-import:DO-214AA")
      (libsource (lib "eagle-import") (part "DIODEDO214AA"))
    )
    (comp (ref "DSM2")
      (value "JST_ZH_3")
      (footprint "eagle-import:JST_ZH_3")
      (libsource (lib "eagle-import") (part "JST_ZH_3"))
    )
    (comp (ref "E1")
      (value "JST_SH_4")
      (footprint "eagle-import:JST_SH_4_SMD")
      (libsource (lib "eagle-import") (part "JST_SH_4"))
    )
    (comp (ref "E2")
      (value "JST_SH_4")
      (footprint "eagle-import:JST_SH_4_SMD")
      (libsource (lib "eagle-import") (part "JST_SH_4"))
    )
    (comp (ref "E3")
      (value "JST_SH_4")
      (footprint "eagle-import:JST_SH_4_SMD")
      (libsource (lib "eagle-import") (part "JST_SH_4"))
    )
    (comp (ref "E4")
      (value "JST_SH_4")
      (footprint "eagle-import:JST_SH_4_SMD")
      (libsource (lib "eagle-import") (part "JST_SH_4"))
    )
    (comp (ref "G")
      (value "GREEN")
      (footprint "eagle-import:0603-GREEN")
      (libsource (lib "eagle-import") (part "LED-GREEN0603"))
    )
    (comp (ref "GP0")
      (value "JST_SH_6")
      (footprint "eagle-import:JST_SH_6")
      (libsource (lib "eagle-import") (part "JST_SH_6"))
    )
    (comp (ref "GP1")
      (value "JST_SH_6")
      (footprint "eagle-import:JST_SH_6")
      (libsource (lib "eagle-import") (part "JST_SH_6"))
    )
    (comp (ref "GPS")
      (value "JST_SH_6")
      (footprint "eagle-import:JST_SH_6")
      (libsource (lib "eagle-import") (part "JST_SH_6"))
    )
    (comp (ref "H1")
      (value "TB6621FNG")
      (footprint "eagle-import:SOP65P760X140-24")
      (libsource (lib "eagle-import") (part "TB6621FNG"))
    )
    (comp (ref "H2")
      (value "TB6621FNG")
      (footprint "eagle-import:SOP65P760X140-24")
      (libsource (lib "eagle-import") (part "TB6621FNG"))
    )
    (comp (ref "I2C")
      (value "JST_SH_4")
      (footprint "eagle-import:JST_SH_4_SMD")
      (libsource (lib "eagle-import") (part "JST_SH_4"))
    )
    (comp (ref "IMU")
      (value "MPU-9250")
      (footprint "eagle-import:QFN24G-0.4-3X3MM")
      (libsource (lib "eagle-import") (part "MPU-9250"))
    )
    (comp (ref "J2")
      (value "SERVO_HEADERS_8X")
      (footprint "eagle-import:DIODE_3X8_0.1__HEADER")
      (libsource (lib "eagle-import") (part "SERVO_HEADERS_8X"))
    )
    (comp (ref "L1")
      (value "6.8uH")
      (footprint "eagle-import:SRN6045")
      (libsource (lib "eagle-import") (part "INDUCTORSRN6045"))
    )
    (comp (ref "L2")
      (value "6.8uH")
      (footprint "eagle-import:SRN6045")
      (libsource (lib "eagle-import") (part "INDUCTORSRN6045"))
    )
    (comp (ref "L3")
      (value "3.6 uH")
      (footprint "eagle-import:INDUCTOR-8X8MM")
      (libsource (lib "eagle-import") (part "INDUCTOR8X8MM"))
    )
    (comp (ref "LIPO")
      (value "BATTERY")
      (footprint "eagle-import:JST_XH_3-PIN")
      (libsource (lib "eagle-import") (part "JST_XH_3-PIN"))
    )
    (comp (ref "M1")
      (value "JST_ZH_2")
      (footprint "eagle-import:JST_ZH_2")
      (libsource (lib "eagle-import") (part "JST_ZH_2"))
    )
    (comp (ref "M2")
      (value "JST_ZH_2")
      (footprint "eagle-import:JST_ZH_2")
      (libsource (lib "eagle-import") (part "JST_ZH_2"))
    )
    (comp (ref "M3")
      (value "JST_ZH_2")
      (footprint "eagle-import:JST_ZH_2")
      (libsource (lib "eagle-import") (part "JST_ZH_2"))
    )
    (comp (ref "M4")
      (value "JST_ZH_2")
      (footprint "eagle-import:JST_ZH_2")
      (libsource (lib "eagle-import") (part "JST_ZH_2"))
    )
    (comp (ref "MOD")
      (value "RS032G05A3SM-SPST-MOMENTARY-SWSMD-1101NE")
      (footprint "eagle-import:TACTILE-SWITCH-1101NE")
      (libsource (lib "eagle-import") (part "RS032G05A3SM-SPST-MOMENTARY-SWSMD-1101NE"))
    )
    (comp (ref "PAU")
      (value "RS032G05A3SM-SPST-MOMENTARY-SWSMD-1101NE")
      (footprint "eagle-import:TACTILE-SWITCH-1101NE")
      (libsource (lib "eagle-import") (part "RS032G05A3SM-SPST-MOMENTARY-SWSMD-1101NE"))
    )
    (comp (ref "POW")
      (value "RS032G05A3SM-SPST-MOMENTARY-SWSMD-1101NE")
      (footprint "eagle-import:TACTILE-SWITCH-1101NE")
      (libsource (lib "eagle-import") (part "RS032G05A3SM-SPST-MOMENTARY-SWSMD-1101NE"))
    )
    (comp (ref "PROT")
      (value "S-8261")
      (footprint "eagle-import:SOT-236")
      (libsource (lib "eagle-import") (part "S-8261"))
    )
    (comp (ref "PWR")
      (value "JST_SH_4")
      (footprint "eagle-import:JST_SH_4_SMD")
      (libsource (lib "eagle-import") (part "JST_SH_4"))
    )
    (comp (ref "Q1")
      (value "MOSFET-N")
      (footprint "eagle-import:SO08-TIGHT")
      (libsource (lib "eagle-import") (part "MOSFET-NCHANNEL"))
    )
    (comp (ref "R")
      (value "RED")
      (footprint "eagle-import:0603-RED")
      (libsource (lib "eagle-import") (part "LED-RED0603"))
    )
    (comp (ref "R1")
      (value "47k")
      (footprint "eagle-import:0402-RES")
      (libsource (lib "eagle-import") (part "RESISTOR0402"))
    )
    (comp (ref "R3")
      (value "1k")
      (footprint "eagle-import:0402-RES")
      (libsource (lib "eagle-import") (part "RESISTOR0402"))
    )
    (comp (ref "R4")
      (value "0.1")
      (footprint "eagle-import:0402-RES")
      (libsource (lib "eagle-import") (part "RESISTOR0402"))
    )
    (comp (ref "R5")
      (value "10k")
      (footprint "eagle-import:0402-RES")
      (libsource (lib "eagle-import") (part "RESISTOR0402"))
    )
    (comp (ref "R6")
      (value "10k")
      (footprint "eagle-import:0402-RES")
      (libsource (lib "eagle-import") (part "RESISTOR0402"))
    )
    (comp (ref "R7")
      (value "4.7k")
      (footprint "eagle-import:0402-RES")
      (libsource (lib "eagle-import") (part "RESISTOR0402"))
    )
    (comp (ref "R8")
      (value "10k")
      (footprint "eagle-import:0402-RES")
      (libsource (lib "eagle-import") (part "RESISTOR0402"))
    )
    (comp (ref "R10")
      (value "4.7k")
      (footprint "eagle-import:0402-RES")
      (libsource (lib "eagle-import") (part "RESISTOR0402"))
    )
    (comp (ref "R11")
      (value "4.7k")
      (footprint "eagle-import:0402-RES")
      (libsource (lib "eagle-import") (part "RESISTOR0402"))
    )
    (comp (ref "R12")
      (value "4.7k")
      (footprint "eagle-import:0402-RES")
      (libsource (lib "eagle-import") (part "RESISTOR0402"))
    )
    (comp (ref "R13")
      (value "4.7k")
      (footprint "eagle-import:0402-RES")
      (libsource (lib "eagle-import") (part "RESISTOR0402"))
    )
    (comp (ref "R14")
      (value "4.7k")
      (footprint "eagle-import:0402-RES")
      (libsource (lib "eagle-import") (part "RESISTOR0402"))
    )
    (comp (ref "R19")
      (value "47k")
      (footprint "eagle-import:0402-RES")
      (libsource (lib "eagle-import") (part "RESISTOR0402"))
    )
    (comp (ref "R21")
      (value "240")
      (footprint "eagle-import:0402-RES")
      (libsource (lib "eagle-import") (part "RESISTOR0402"))
    )
    (comp (ref "R22")
      (value "240")
      (footprint "eagle-import:0402-RES")
      (libsource (lib "eagle-import") (part "RESISTOR0402"))
    )
    (comp (ref "R25")
      (value "4.7k")
      (footprint "eagle-import:0402-RES")
      (libsource (lib "eagle-import") (part "RESISTOR0402"))
    )
    (comp (ref "R27")
      (value "150")
      (footprint "eagle-import:0402-RES")
      (libsource (lib "eagle-import") (part "RESISTOR0402"))
    )
    (comp (ref "R28")
      (value "150")
      (footprint "eagle-import:0402-RES")
      (libsource (lib "eagle-import") (part "RESISTOR0402"))
    )
    (comp (ref "R29")
      (value "240")
      (footprint "eagle-import:0402-RES")
      (libsource (lib "eagle-import") (part "RESISTOR0402"))
    )
    (comp (ref "R30")
      (value "240")
      (footprint "eagle-import:0402-RES")
      (libsource (lib "eagle-import") (part "RESISTOR0402"))
    )
    (comp (ref "R31")
      (value "240")
      (footprint "eagle-import:0402-RES")
      (libsource (lib "eagle-import") (part "RESISTOR0402"))
    )
    (comp (ref "R32")
      (value "240")
      (footprint "eagle-import:0402-RES")
      (libsource (lib "eagle-import") (part "RESISTOR0402"))
    )
    (comp (ref "R33")
      (value "240")
      (footprint "eagle-import:0402-RES")
      (libsource (lib "eagle-import") (part "RESISTOR0402"))
    )
    (comp (ref "R34")
      (value "150")
      (footprint "eagle-import:0402-RES")
      (libsource (lib "eagle-import") (part "RESISTOR0402"))
    )
    (comp (ref "R36")
      (value "4.7k")
      (footprint "eagle-import:0402-RES")
      (libsource (lib "eagle-import") (part "RESISTOR0402"))
    )
    (comp (ref "R37")
      (value "4.7k")
      (footprint "eagle-import:0402-RES")
      (libsource (lib "eagle-import") (part "RESISTOR0402"))
    )
    (comp (ref "R38")
      (value "4.7k")
      (footprint "eagle-import:0402-RES")
      (libsource (lib "eagle-import") (part "RESISTOR0402"))
    )
    (comp (ref "R39")
      (value "4.7k")
      (footprint "eagle-import:0402-RES")
      (libsource (lib "eagle-import") (part "RESISTOR0402"))
    )
    (comp (ref "R40")
      (value "4.7k")
      (footprint "eagle-import:0402-RES")
      (libsource (lib "eagle-import") (part "RESISTOR0402"))
    )
    (comp (ref "R41")
      (value "4.7k")
      (footprint "eagle-import:0402-RES")
      (libsource (lib "eagle-import") (part "RESISTOR0402"))
    )
    (comp (ref "R42")
      (value "4.7k")
      (footprint "eagle-import:0402-RES")
      (libsource (lib "eagle-import") (part "RESISTOR0402"))
    )
    (comp (ref "R43")
      (value "4.7k")
      (footprint "eagle-import:0402-RES")
      (libsource (lib "eagle-import") (part "RESISTOR0402"))
    )
    (comp (ref "R44")
      (value "1k")
      (footprint "eagle-import:0402-RES")
      (libsource (lib "eagle-import") (part "RESISTOR0402"))
    )
    (comp (ref "R45")
      (value "47k")
      (footprint "eagle-import:0402-RES")
      (libsource (lib "eagle-import") (part "RESISTOR0402"))
    )
    (comp (ref "R46")
      (value "1K")
      (footprint "eagle-import:0402-RES")
      (libsource (lib "eagle-import") (part "RESISTOR0402"))
    )
    (comp (ref "R47")
      (value "100k")
      (footprint "eagle-import:0402-RES")
      (libsource (lib "eagle-import") (part "RESISTOR0402"))
    )
    (comp (ref "R48")
      (value "10k")
      (footprint "eagle-import:0402-RES")
      (libsource (lib "eagle-import") (part "RESISTOR0402"))
    )
    (comp (ref "R49")
      (value "65k")
      (footprint "eagle-import:0402-RES")
      (libsource (lib "eagle-import") (part "RESISTOR0402"))
    )
    (comp (ref "R50")
      (value "4.7k")
      (footprint "eagle-import:0402-RES")
      (libsource (lib "eagle-import") (part "RESISTOR0402"))
    )
    (comp (ref "R51")
      (value "4.7k")
      (footprint "eagle-import:0402-RES")
      (libsource (lib "eagle-import") (part "RESISTOR0402"))
    )
    (comp (ref "R52")
      (value "4.7k")
      (footprint "eagle-import:0402-RES")
      (libsource (lib "eagle-import") (part "RESISTOR0402"))
    )
    (comp (ref "R53")
      (value "4.7k")
      (footprint "eagle-import:0402-RES")
      (libsource (lib "eagle-import") (part "RESISTOR0402"))
    )
    (comp (ref "R61")
      (value "1K")
      (footprint "eagle-import:0402-RES")
      (libsource (lib "eagle-import") (part "RESISTOR0402"))
    )
    (comp (ref "R62")
      (value "1K")
      (footprint "eagle-import:0402-RES")
      (libsource (lib "eagle-import") (part "RESISTOR0402"))
    )
    (comp (ref "R63")
      (value "1K")
      (footprint "eagle-import:0402-RES")
      (libsource (lib "eagle-import") (part "RESISTOR0402"))
    )
    (comp (ref "R64")
      (value "1K")
      (footprint "eagle-import:0402-RES")
      (libsource (lib "eagle-import") (part "RESISTOR0402"))
    )
    (comp (ref "R91")
      (value "240")
      (footprint "eagle-import:0402-RES")
      (libsource (lib "eagle-import") (part "RESISTOR0402"))
    )
    (comp (ref "R107")
      (value ".1, 0805")
      (footprint "eagle-import:R0805")
      (libsource (lib "eagle-import") (part "RESISTOR0805"))
    )
    (comp (ref "RST")
      (value "RS032G05A3SM-SPST-MOMENTARY-SWSMD-1101NE")
      (footprint "eagle-import:TACTILE-SWITCH-1101NE")
      (libsource (lib "eagle-import") (part "RS032G05A3SM-SPST-MOMENTARY-SWSMD-1101NE"))
    )
    (comp (ref "S1.1")
      (value "JST_SH_6")
      (footprint "eagle-import:JST_SH_6")
      (libsource (lib "eagle-import") (part "JST_SH_6"))
    )
    (comp (ref "S1.2")
      (value "JST_SH_6")
      (footprint "eagle-import:JST_SH_6")
      (libsource (lib "eagle-import") (part "JST_SH_6"))
    )
    (comp (ref "SD")
      (value "RS032G05A3SM-SPST-MOMENTARY-SWSMD-1101NE")
      (footprint "eagle-import:TACTILE-SWITCH-1101NE")
      (libsource (lib "eagle-import") (part "RS032G05A3SM-SPST-MOMENTARY-SWSMD-1101NE"))
    )
    (comp (ref "UT0")
      (value "JST_SH_4")
      (footprint "eagle-import:JST_SH_4_SMD")
      (libsource (lib "eagle-import") (part "JST_SH_4"))
    )
    (comp (ref "UT1")
      (value "JST_SH_4")
      (footprint "eagle-import:JST_SH_4_SMD")
      (libsource (lib "eagle-import") (part "JST_SH_4"))
    )
    (comp (ref "UT5")
      (value "JST_SH_4")
      (footprint "eagle-import:JST_SH_4_SMD")
      (libsource (lib "eagle-import") (part "JST_SH_4"))
    )
    (comp (ref "WIFI")
      (value "GREEN")
      (footprint "eagle-import:0603-GREEN")
      (libsource (lib "eagle-import") (part "LED-GREEN0603"))
    )
  )
  (nets
    (net (code "1") (name "3.3V") (class "Default")
      (node (ref "BMP") (pin "2") (pinfunction "CSB_2") (pintype "input"))
      (node (ref "BMP") (pin "6") (pinfunction "VDDIO_6") (pintype "input"))
      (node (ref "BMP") (pin "8") (pinfunction "VDD_8") (pintype "power_in"))
      (node (ref "C13") (pin "1") (pinfunction "1_1") (pintype "passive"))
      (node (ref "C16") (pin "1") (pinfunction "1_1") (pintype "passive"))
      (node (ref "C2") (pin "2") (pinfunction "2_2") (pintype "passive"))
      (node (ref "C27") (pin "1") (pinfunction "1_1") (pintype "passive"))
      (node (ref "C28") (pin "1") (pinfunction "1_1") (pintype "passive"))
      (node (ref "C34") (pin "2") (pinfunction "2_2") (pintype "passive"))
      (node (ref "C35") (pin "2") (pinfunction "2_2") (pintype "passive"))
      (node (ref "C37") (pin "1") (pinfunction "1_1") (pintype "passive"))
      (node (ref "C38") (pin "1") (pinfunction "1_1") (pintype "passive"))
      (node (ref "C39") (pin "1") (pinfunction "1_1") (pintype "passive"))
      (node (ref "C40") (pin "1") (pinfunction "1_1") (pintype "passive"))
      (node (ref "C41") (pin "1") (pinfunction "1_1") (pintype "passive"))
      (node (ref "C49") (pin "2") (pinfunction "2_2") (pintype "passive"))
      (node (ref "C51") (pin "2") (pinfunction "2_2") (pintype "passive"))
      (node (ref "C53") (pin "1") (pinfunction "1_1") (pintype "passive"))
      (node (ref "C56") (pin "1") (pinfunction "1_1") (pintype "passive"))
      (node (ref "C59") (pin "1") (pinfunction "1_1") (pintype "passive"))
      (node (ref "C8") (pin "1") (pinfunction "1_1") (pintype "passive"))
      (node (ref "C9") (pin "2") (pinfunction "2_2") (pintype "passive"))
      (node (ref "CAN") (pin "2") (pinfunction "2_2") (pintype "bidirectional"))
      (node (ref "DSM2") (pin "P$1") (pinfunction "1_P$1") (pintype "bidirectional"))
      (node (ref "E1") (pin "2") (pinfunction "2_2") (pintype "bidirectional"))
      (node (ref "E2") (pin "2") (pinfunction "2_2") (pintype "bidirectional"))
      (node (ref "E3") (pin "2") (pinfunction "2_2") (pintype "bidirectional"))
      (node (ref "E4") (pin "2") (pinfunction "2_2") (pintype "bidirectional"))
      (node (ref "GP0") (pin "2") (pinfunction "2_2") (pintype "bidirectional"))
      (node (ref "GP1") (pin "2") (pinfunction "2_2") (pintype "bidirectional"))
      (node (ref "H1") (pin "20") (pinfunction "VCC_20") (pintype "bidirectional"))
      (node (ref "H2") (pin "20") (pinfunction "VCC_20") (pintype "bidirectional"))
      (node (ref "I2C") (pin "2") (pinfunction "2_2") (pintype "bidirectional"))
      (node (ref "IMU") (pin "1") (pinfunction "RESV_1") (pintype "bidirectional"))
      (node (ref "IMU") (pin "13") (pinfunction "VDD_13") (pintype "bidirectional"))
      (node (ref "IMU") (pin "22") (pinfunction "NCS_22") (pintype "bidirectional"))
      (node (ref "IMU") (pin "8") (pinfunction "VDDIO_8") (pintype "bidirectional"))
      (node (ref "PWR") (pin "3") (pinfunction "3_3") (pintype "bidirectional"))
      (node (ref "R10") (pin "1") (pinfunction "1_1") (pintype "passive"))
      (node (ref "R109") (pin "1") (pinfunction "1_1") (pintype "passive"))
      (node (ref "R11") (pin "2") (pinfunction "2_2") (pintype "passive"))
      (node (ref "R116") (pin "2") (pinfunction "2_2") (pintype "passive"))
      (node (ref "R118") (pin "2") (pinfunction "2_2") (pintype "passive"))
      (node (ref "R12") (pin "2") (pinfunction "2_2") (pintype "passive"))
      (node (ref "R120") (pin "2") (pinfunction "2_2") (pintype "passive"))
      (node (ref "R122") (pin "2") (pinfunction "2_2") (pintype "passive"))
      (node (ref "R13") (pin "1") (pinfunction "1_1") (pintype "passive"))
      (node (ref "R140") (pin "2") (pinfunction "2_2") (pintype "passive"))
      (node (ref "R2") (pin "2") (pinfunction "2_2") (pintype "passive"))
      (node (ref "R23") (pin "2") (pinfunction "2_2") (pintype "passive"))
      (node (ref "R26") (pin "2") (pinfunction "2_2") (pintype "passive"))
      (node (ref "R35") (pin "2") (pinfunction "2_2") (pintype "passive"))
      (node (ref "R54") (pin "2") (pinfunction "2_2") (pintype "passive"))
      (node (ref "R55") (pin "2") (pinfunction "2_2") (pintype "passive"))
      (node (ref "R56") (pin "2") (pinfunction "2_2") (pintype "passive"))
      (node (ref "R57") (pin "2") (pinfunction "2_2") (pintype "passive"))
      (node (ref "R58") (pin "2") (pinfunction "2_2") (pintype "passive"))
      (node (ref "R60") (pin "2") (pinfunction "2_2") (pintype "passive"))
      (node (ref "R65") (pin "2") (pinfunction "2_2") (pintype "passive"))
      (node (ref "R66") (pin "2") (pinfunction "2_2") (pintype "passive"))
      (node (ref "R67") (pin "2") (pinfunction "2_2") (pintype "passive"))
      (node (ref "R68") (pin "2") (pinfunction "2_2") (pintype "passive"))
      (node (ref "R69") (pin "2") (pinfunction "2_2") (pintype "passive"))
      (node (ref "R70") (pin "2") (pinfunction "2_2") (pintype "passive"))
      (node (ref "R71") (pin "2") (pinfunction "2_2") (pintype "passive"))
      (node (ref "R72") (pin "2") (pinfunction "2_2") (pintype "passive"))
      (node (ref "R73") (pin "2") (pinfunction "2_2") (pintype "passive"))
      (node (ref "R74") (pin "2") (pinfunction "2_2") (pintype "passive"))
      (node (ref "R75") (pin "2") (pinfunction "2_2") (pintype "passive"))
      (node (ref "R94") (pin "2") (pinfunction "2_2") (pintype "passive"))
      (node (ref "S1.1") (pin "2") (pinfunction "2_2") (pintype "bidirectional"))
      (node (ref "S1.2") (pin "2") (pinfunction "2_2") (pintype "bidirectional"))
      (node (ref "SIP") (pin "U20") (pinfunction "VOUT_USER_3P3V_0_U20") (pintype "power_in"))
      (node (ref "SIP") (pin "V20") (pinfunction "VOUT_USER_3P3V_1_V20") (pintype "power_in"))
      (node (ref "U1") (pin "5") (pinfunction "VIO_5") (pintype "power_in"))
      (node (ref "U10") (pin "19") (pinfunction "VCCB_19") (pintype "bidirectional"))
      (node (ref "U13") (pin "C6") (pinfunction "VCCQ1_C6") (pintype "bidirectional"))
      (node (ref "U13") (pin "E6") (pinfunction "VCC1_E6") (pintype "bidirectional"))
      (node (ref "U13") (pin "F5") (pinfunction "VCC2_F5") (pintype "bidirectional"))
      (node (ref "U13") (pin "J10") (pinfunction "VCC3_J10") (pintype "bidirectional"))
      (node (ref "U13") (pin "K9") (pinfunction "VCC4_K9") (pintype "bidirectional"))
      (node (ref "U13") (pin "M4") (pinfunction "VCCQ2_M4") (pintype "bidirectional"))
      (node (ref "U13") (pin "N4") (pinfunction "VCCQ3_N4") (pintype "bidirectional"))
      (node (ref "U13") (pin "P3") (pinfunction "VCCQ4_P3") (pintype "bidirectional"))
      (node (ref "U13") (pin "P5") (pinfunction "VCCQ5_P5") (pintype "bidirectional"))
      (node (ref "U5") (pin "4") (pinfunction "VCC_4") (pintype "power_in"))
      (node (ref "U7") (pin "46") (pinfunction "VBAT_IN1_46") (pintype "bidirectional"))
      (node (ref "U7") (pin "47") (pinfunction "VBAT_IN2_47") (pintype "bidirectional"))
      (node (ref "U9") (pin "19") (pinfunction "VCCB_19") (pintype "bidirectional"))
      (node (ref "UT0") (pin "2") (pinfunction "2_2") (pintype "bidirectional"))
      (node (ref "UT1") (pin "2") (pinfunction "2_2") (pintype "bidirectional"))
      (node (ref "UT5") (pin "2") (pinfunction "2_2") (pintype "bidirectional"))
      (node (ref "X2") (pin "4") (pinfunction "VDD_4") (pintype "bidirectional"))
    )
    (net (code "2") (name "5.0V") (class "Default")
      (node (ref "5VREG") (pin "3") (pinfunction "FB_3") (pintype "power_in"))
      (node (ref "C5") (pin "1") (pinfunction "1_1") (pintype "passive"))
      (node (ref "C63") (pin "1") (pinfunction "1_1") (pintype "passive"))
      (node (ref "GPS") (pin "5") (pinfunction "5_5") (pintype "bidirectional"))
      (node (ref "L1") (pin "2") (pinfunction "2_2") (pintype "passive"))
      (node (ref "PWR") (pin "4") (pinfunction "4_4") (pintype "bidirectional"))
      (node (ref "R119") (pin "2") (pinfunction "2_2") (pintype "passive"))
      (node (ref "R95") (pin "2") (pinfunction "2_2") (pintype "passive"))
      (node (ref "SIP") (pin "Y5") (pinfunction "VIN_AC_0_Y5") (pintype "power_in"))
      (node (ref "SIP") (pin "Y6") (pinfunction "VIN_AC_1_Y6") (pintype "power_in"))
      (node (ref "U8") (pin "1") (pinfunction "EN_1") (pintype "input"))
      (node (ref "U8") (pin "5") (pinfunction "IN1_5") (pintype "input"))
    )
    (net (code "3") (name "32.768KHZ") (class "Default")
      (node (ref "OSC1") (pin "3") (pinfunction "OUT_3") (pintype "bidirectional"))
      (node (ref "U7") (pin "36") (pinfunction "EXT_32K_36") (pintype "bidirectional"))
    )
    (net (code "4") (name "AIN0") (class "Default")
      (node (ref "ADC") (pin "3") (pinfunction "3_3") (pintype "bidirectional"))
      (node (ref "SIP") (pin "B6") (pinfunction "AIN0_B6") (pintype "bidirectional"))
    )
    (net (code "5") (name "AIN1") (class "Default")
      (node (ref "ADC") (pin "4") (pinfunction "4_4") (pintype "bidirectional"))
      (node (ref "SIP") (pin "C7") (pinfunction "AIN1_C7") (pintype "bidirectional"))
    )
    (net (code "6") (name "AIN2") (class "Default")
      (node (ref "ADC") (pin "5") (pinfunction "5_5") (pintype "bidirectional"))
      (node (ref "SIP") (pin "B7") (pinfunction "AIN2_B7") (pintype "bidirectional"))
    )
    (net (code "7") (name "AIN3") (class "Default")
      (node (ref "ADC") (pin "6") (pinfunction "6_6") (pintype "bidirectional"))
      (node (ref "SIP") (pin "A7") (pinfunction "AIN3_A7") (pintype "bidirectional"))
    )
    (net (code "8") (name "BATT_LED_1") (class "Default")
      (node (ref "B0") (pin "A") (pinfunction "A_A") (pintype "passive"))
      (node (ref "SIP") (pin "U12") (pinfunction "GPIO0_27_U12_U12") (pintype "bidirectional"))
    )
    (net (code "9") (name "BATT_LED_2") (class "Default")
      (node (ref "B1") (pin "A") (pinfunction "A_A") (pintype "passive"))
      (node (ref "R143") (pin "2") (pinfunction "2_2") (pintype "passive"))
      (node (ref "SIP") (pin "T5") (pinfunction "LCD_DATA15_T5_T5") (pintype "bidirectional"))
    )
    (net (code "10") (name "BATT_LED_3") (class "Default")
      (node (ref "B2") (pin "A") (pinfunction "A_A") (pintype "passive"))
      (node (ref "SIP") (pin "V6") (pinfunction "GPIO1_29_V6_V6") (pintype "bidirectional"))
    )
    (net (code "11") (name "BATT_LED_4") (class "Default")
      (node (ref "B3") (pin "A") (pinfunction "A_A") (pintype "passive"))
      (node (ref "SIP") (pin "T11") (pinfunction "GPIO0_26_T11_T11") (pintype "bidirectional"))
    )
    (net (code "12") (name "BATT_MID") (class "Default")
      (node (ref "LIPO") (pin "P$2") (pinfunction "2_P$2") (pintype "passive"))
      (node (ref "R27") (pin "1") (pinfunction "1_1") (pintype "passive"))
      (node (ref "R30") (pin "1") (pinfunction "1_1") (pintype "passive"))
      (node (ref "R44") (pin "1") (pinfunction "1_1") (pintype "passive"))
    )
    (net (code "13") (name "BATT_MINUS") (class "Default")
      (node (ref "BAL") (pin "5") (pinfunction "GND_5") (pintype "bidirectional"))
      (node (ref "BAL") (pin "6") (pinfunction "CB_EN_6") (pintype "bidirectional"))
      (node (ref "C1") (pin "2") (pinfunction "2_2") (pintype "passive"))
      (node (ref "C15") (pin "1") (pinfunction "1_1") (pintype "passive"))
      (node (ref "C18") (pin "1") (pinfunction "1_1") (pintype "passive"))
      (node (ref "C19") (pin "2") (pinfunction "2_2") (pintype "passive"))
      (node (ref "LIPO") (pin "P$3") (pinfunction "3_P$3") (pintype "passive"))
      (node (ref "PROT") (pin "2") (pinfunction "VM_2") (pintype "bidirectional"))
      (node (ref "PROT") (pin "6") (pinfunction "VSS_6") (pintype "bidirectional"))
      (node (ref "Q1") (pin "1") (pinfunction "S_1") (pintype "passive"))
      (node (ref "Q1") (pin "2") (pinfunction "S_2") (pintype "passive"))
      (node (ref "Q1") (pin "3") (pinfunction "S_3") (pintype "passive"))
    )
    (net (code "14") (name "BT_AUD_CLK") (class "Default")
      (node (ref "R124") (pin "1") (pinfunction "1_1") (pintype "passive"))
      (node (ref "U10") (pin "1") (pinfunction "A1_1") (pintype "bidirectional"))
    )
    (net (code "15") (name "BT_AUD_FSYNC") (class "Default")
      (node (ref "R123") (pin "1") (pinfunction "1_1") (pintype "passive"))
      (node (ref "U10") (pin "3") (pinfunction "A2_3") (pintype "bidirectional"))
    )
    (net (code "16") (name "BT_AUD_IN") (class "Default")
      (node (ref "R97") (pin "1") (pinfunction "1_1") (pintype "passive"))
      (node (ref "U10") (pin "5") (pinfunction "A4_5") (pintype "bidirectional"))
    )
    (net (code "17") (name "BT_AUD_OUT") (class "Default")
      (node (ref "R100") (pin "1") (pinfunction "1_1") (pintype "passive"))
      (node (ref "U10") (pin "4") (pinfunction "A3_4") (pintype "bidirectional"))
    )
    (net (code "18") (name "BT_EN") (class "Default")
      (node (ref "SIP") (pin "K17") (pinfunction "K17_K17") (pintype "bidirectional"))
      (node (ref "U9") (pin "18") (pinfunction "B2_18") (pintype "bidirectional"))
    )
    (net (code "19") (name "BT_EN_1V8") (class "Default")
      (node (ref "R88") (pin "1") (pinfunction "1_1") (pintype "passive"))
      (node (ref "U7") (pin "41") (pinfunction "BT_EN_41") (pintype "bidirectional"))
      (node (ref "U9") (pin "3") (pinfunction "A2_3") (pintype "bidirectional"))
    )
    (net (code "20") (name "BT_HCI_CTS") (class "Default")
      (node (ref "R86") (pin "1") (pinfunction "1_1") (pintype "passive"))
      (node (ref "U10") (pin "8") (pinfunction "A7_8") (pintype "bidirectional"))
    )
    (net (code "21") (name "BT_HCI_RTS") (class "Default")
      (node (ref "R85") (pin "1") (pinfunction "1_1") (pintype "passive"))
      (node (ref "U10") (pin "9") (pinfunction "A8_9") (pintype "bidirectional"))
    )
    (net (code "22") (name "BT_HCI_RX") (class "Default")
      (node (ref "R96") (pin "1") (pinfunction "1_1") (pintype "passive"))
      (node (ref "U10") (pin "6") (pinfunction "A5_6") (pintype "bidirectional"))
    )
    (net (code "23") (name "BT_HCI_TX") (class "Default")
      (node (ref "R92") (pin "1") (pinfunction "1_1") (pintype "passive"))
      (node (ref "U10") (pin "7") (pinfunction "A6_7") (pintype "bidirectional"))
    )
    (net (code "24") (name "CANH") (class "Default")
      (node (ref "CAN") (pin "3") (pinfunction "3_3") (pintype "bidirectional"))
      (node (ref "R104") (pin "1") (pinfunction "1_1") (pintype "passive"))
      (node (ref "U1") (pin "7") (pinfunction "CANH_7") (pintype "bidirectional"))
    )
    (net (code "25") (name "CANL") (class "Default")
      (node (ref "CAN") (pin "4") (pinfunction "4_4") (pintype "bidirectional"))
      (node (ref "R104") (pin "2") (pinfunction "2_2") (pintype "passive"))
      (node (ref "U1") (pin "6") (pinfunction "CANL_6") (pintype "bidirectional"))
    )
    (net (code "26") (name "CGND") (class "Default")
      (node (ref "MGT1") (pin "P$1") (pinfunction "P$1_P$1") (pintype "bidirectional"))
      (node (ref "MGT2") (pin "P$1") (pinfunction "P$1_P$1") (pintype "bidirectional"))
      (node (ref "MGT3") (pin "P$1") (pinfunction "P$1_P$1") (pintype "bidirectional"))
      (node (ref "MGT4") (pin "P$1") (pinfunction "P$1_P$1") (pintype "bidirectional"))
      (node (ref "R107") (pin "2") (pinfunction "2_2") (pintype "passive"))
      (node (ref "X2") (pin "CGND1") (pinfunction "CGND1_CGND1") (pintype "bidirectional"))
      (node (ref "X2") (pin "CGND2") (pinfunction "CGND2_CGND2") (pintype "bidirectional"))
      (node (ref "X2") (pin "CGND3") (pinfunction "CGND3_CGND3") (pintype "bidirectional"))
      (node (ref "X2") (pin "CGND4") (pinfunction "CGND4_CGND4") (pintype "bidirectional"))
      (node (ref "X2") (pin "CGND5") (pinfunction "CGND5_CGND5") (pintype "bidirectional"))
      (node (ref "X2") (pin "CGND6") (pinfunction "CGND6_CGND6") (pintype "bidirectional"))
      (node (ref "X3") (pin "5") (pinfunction "CG1_5") (pintype "bidirectional"))
      (node (ref "X3") (pin "6") (pinfunction "CG2_6") (pintype "bidirectional"))
      (node (ref "X4") (pin "CGND1") (pinfunction "SGND1_CGND1") (pintype "bidirectional"))
      (node (ref "X4") (pin "CGND2") (pinfunction "SGND2_CGND2") (pintype "bidirectional"))
      (node (ref "X4") (pin "CGND3") (pinfunction "SGND3_CGND3") (pintype "bidirectional"))
      (node (ref "X4") (pin "CGND4") (pinfunction "SGND4_CGND4") (pintype "bidirectional"))
      (node (ref "X4") (pin "CGND5") (pinfunction "SGND5_CGND5") (pintype "bidirectional"))
      (node (ref "X4") (pin "CGND6") (pinfunction "SGND6_CGND6") (pintype "bidirectional"))
    )
    (net (code "27") (name "CHG_EN") (class "Default")
      (node (ref "CHGIC") (pin "6") (pinfunction "EN_6") (pintype "bidirectional"))
      (node (ref "R7") (pin "2") (pinfunction "2_2") (pintype "passive"))
      (node (ref "R8") (pin "1") (pinfunction "1_1") (pintype "passive"))
    )
    (net (code "28") (name "DCAN1_RX") (class "Default")
      (node (ref "SIP") (pin "E17") (pinfunction "UART0_RTSN_E17_E17") (pintype "bidirectional"))
      (node (ref "U1") (pin "4") (pinfunction "RXD_4") (pintype "output"))
    )
    (net (code "29") (name "DCAN1_SILENT") (class "Default")
      (node (ref "SIP") (pin "M16") (pinfunction "M16_M16") (pintype "bidirectional"))
      (node (ref "U1") (pin "8") (pinfunction "S_8") (pintype "input"))
    )
    (net (code "30") (name "DCAN1_TX") (class "Default")
      (node (ref "SIP") (pin "E18") (pinfunction "UART0_CTSN_E18_E18") (pintype "bidirectional"))
      (node (ref "U1") (pin "1") (pinfunction "TXD_1") (pintype "input"))
    )
    (net (code "31") (name "DO") (class "Default")
      (node (ref "PROT") (pin "1") (pinfunction "DO_1") (pintype "bidirectional"))
      (node (ref "Q1") (pin "4") (pinfunction "G_4") (pintype "passive"))
    )
    (net (code "32") (name "EMMC_RST") (class "Default")
      (node (ref "R94") (pin "1") (pinfunction "1_1") (pintype "passive"))
      (node (ref "SIP") (pin "R14") (pinfunction "EMMCRST_GPIO1_20_R14_R14") (pintype "bidirectional"))
      (node (ref "U13") (pin "K5") (pinfunction "RST#_K5") (pintype "bidirectional"))
    )
    (net (code "33") (name "EQEP_0A") (class "Default")
      (node (ref "E1") (pin "3") (pinfunction "3_3") (pintype "bidirectional"))
      (node (ref "SIP") (pin "B12") (pinfunction "GPIO3_18_B12_B12") (pintype "bidirectional"))
    )
    (net (code "34") (name "EQEP_0B") (class "Default")
      (node (ref "E1") (pin "4") (pinfunction "4_4") (pintype "bidirectional"))
      (node (ref "SIP") (pin "C13") (pinfunction "GPIO3_19_C13_C13") (pintype "bidirectional"))
    )
    (net (code "35") (name "EQEP_1A") (class "Default")
      (node (ref "E2") (pin "3") (pinfunction "3_3") (pintype "bidirectional"))
      (node (ref "R16") (pin "2") (pinfunction "2_2") (pintype "passive"))
      (node (ref "SIP") (pin "V2") (pinfunction "LCD_DATA12_V2_V2") (pintype "bidirectional"))
    )
    (net (code "36") (name "EQEP_1B") (class "Default")
      (node (ref "E2") (pin "4") (pinfunction "4_4") (pintype "bidirectional"))
      (node (ref "R17") (pin "2") (pinfunction "2_2") (pintype "passive"))
      (node (ref "SIP") (pin "V3") (pinfunction "LCD_DATA13_V3_V3") (pintype "bidirectional"))
    )
    (net (code "37") (name "EQEP_2A") (class "Default")
      (node (ref "E3") (pin "3") (pinfunction "3_3") (pintype "bidirectional"))
      (node (ref "SIP") (pin "T12") (pinfunction "GPIO1_12_T12_T12") (pintype "bidirectional"))
    )
    (net (code "38") (name "EQEP_2B") (class "Default")
      (node (ref "E3") (pin "4") (pinfunction "4_4") (pintype "bidirectional"))
      (node (ref "SIP") (pin "R12") (pinfunction "GPIO1_13_R12_R12") (pintype "bidirectional"))
    )
    (net (code "39") (name "GND") (class "Default")
      (node (ref "12V") (pin "OUT") (pinfunction "OUT_OUT") (pintype "bidirectional"))
      (node (ref "5VREG") (pin "4") (pinfunction "SD_4") (pintype "input"))
      (node (ref "5VREG") (pin "5") (pinfunction "GND_5") (pintype "power_in"))
      (node (ref "5VREG") (pin "6") (pinfunction "GND1_6") (pintype "input"))
      (node (ref "5VREG") (pin "7") (pinfunction "GND2_7") (pintype "passive"))
      (node (ref "5VREG") (pin "8") (pinfunction "GND3_8") (pintype "power_in"))
      (node (ref "6VREG") (pin "3") (pinfunction "GND_3") (pintype "bidirectional"))
      (node (ref "ADC") (pin "1") (pinfunction "1_1") (pintype "bidirectional"))
      (node (ref "ANT1") (pin "GND1") (pinfunction "GND1_GND1") (pintype "bidirectional"))
      (node (ref "ANT1") (pin "GND2") (pinfunction "GND2_GND2") (pintype "bidirectional"))
      (node (ref "ANT2") (pin "GND1") (pinfunction "GND1_GND1") (pintype "bidirectional"))
      (node (ref "ANT2") (pin "GND2") (pinfunction "GND2_GND2") (pintype "bidirectional"))
      (node (ref "BMP") (pin "1") (pinfunction "GND_1") (pintype "power_in"))
      (node (ref "BMP") (pin "5") (pinfunction "SDO_5") (pintype "bidirectional"))
      (node (ref "BMP") (pin "7") (pinfunction "GND_7") (pintype "power_in"))
      (node (ref "C10") (pin "1") (pinfunction "1_1") (pintype "passive"))
      (node (ref "C11") (pin "-") (pinfunction "-_-") (pintype "passive"))
      (node (ref "C12") (pin "2") (pinfunction "2_2") (pintype "passive"))
      (node (ref "C13") (pin "2") (pinfunction "2_2") (pintype "passive"))
      (node (ref "C16") (pin "2") (pinfunction "2_2") (pintype "passive"))
      (node (ref "C2") (pin "1") (pinfunction "1_1") (pintype "passive"))
      (node (ref "C20") (pin "1") (pinfunction "1_1") (pintype "passive"))
      (node (ref "C21") (pin "1") (pinfunction "1_1") (pintype "passive"))
      (node (ref "C23") (pin "1") (pinfunction "1_1") (pintype "passive"))
      (node (ref "C24") (pin "1") (pinfunction "1_1") (pintype "passive"))
      (node (ref "C25") (pin "2") (pinfunction "2_2") (pintype "passive"))
      (node (ref "C26") (pin "2") (pinfunction "2_2") (pintype "passive"))
      (node (ref "C27") (pin "2") (pinfunction "2_2") (pintype "passive"))
      (node (ref "C28") (pin "2") (pinfunction "2_2") (pintype "passive"))
      (node (ref "C3") (pin "2") (pinfunction "2_2") (pintype "passive"))
      (node (ref "C33") (pin "2") (pinfunction "2_2") (pintype "passive"))
      (node (ref "C34") (pin "1") (pinfunction "1_1") (pintype "passive"))
      (node (ref "C35") (pin "1") (pinfunction "1_1") (pintype "passive"))
      (node (ref "C36") (pin "2") (pinfunction "2_2") (pintype "passive"))
      (node (ref "C37") (pin "2") (pinfunction "2_2") (pintype "passive"))
      (node (ref "C38") (pin "2") (pinfunction "2_2") (pintype "passive"))
      (node (ref "C39") (pin "2") (pinfunction "2_2") (pintype "passive"))
      (node (ref "C4") (pin "1") (pinfunction "1_1") (pintype "passive"))
      (node (ref "C40") (pin "2") (pinfunction "2_2") (pintype "passive"))
      (node (ref "C41") (pin "2") (pinfunction "2_2") (pintype "passive"))
      (node (ref "C45") (pin "2") (pinfunction "2_2") (pintype "passive"))
      (node (ref "C46") (pin "2") (pinfunction "2_2") (pintype "passive"))
      (node (ref "C47") (pin "2") (pinfunction "2_2") (pintype "passive"))
      (node (ref "C49") (pin "1") (pinfunction "1_1") (pintype "passive"))
      (node (ref "C5") (pin "2") (pinfunction "2_2") (pintype "passive"))
      (node (ref "C50") (pin "2") (pinfunction "2_2") (pintype "passive"))
      (node (ref "C51") (pin "1") (pinfunction "1_1") (pintype "passive"))
      (node (ref "C52") (pin "2") (pinfunction "2_2") (pintype "passive"))
      (node (ref "C53") (pin "2") (pinfunction "2_2") (pintype "passive"))
      (node (ref "C54") (pin "2") (pinfunction "2_2") (pintype "passive"))
      (node (ref "C55") (pin "2") (pinfunction "2_2") (pintype "passive"))
      (node (ref "C56") (pin "2") (pinfunction "2_2") (pintype "passive"))
      (node (ref "C57") (pin "1") (pinfunction "1_1") (pintype "passive"))
      (node (ref "C59") (pin "2") (pinfunction "2_2") (pintype "passive"))
      (node (ref "C6") (pin "2") (pinfunction "2_2") (pintype "passive"))
      (node (ref "C60") (pin "1") (pinfunction "1_1") (pintype "passive"))
      (node (ref "C61") (pin "1") (pinfunction "1_1") (pintype "passive"))
      (node (ref "C62") (pin "2") (pinfunction "2_2") (pintype "passive"))
      (node (ref "C63") (pin "2") (pinfunction "2_2") (pintype "passive"))
      (node (ref "C7") (pin "2") (pinfunction "2_2") (pintype "passive"))
      (node (ref "C8") (pin "2") (pinfunction "2_2") (pintype "passive"))
      (node (ref "C9") (pin "1") (pinfunction "1_1") (pintype "passive"))
      (node (ref "CAN") (pin "1") (pinfunction "1_1") (pintype "bidirectional"))
      (node (ref "CHGIC") (pin "16") (pinfunction "PGND_16") (pintype "bidirectional"))
      (node (ref "CHGIC") (pin "8") (pinfunction "AGND_8") (pintype "bidirectional"))
      (node (ref "D1") (pin "A") (pinfunction "A_A") (pintype "passive"))
      (node (ref "D9") (pin "A") (pinfunction "A_A") (pintype "passive"))
      (node (ref "DSM2") (pin "P$2") (pinfunction "2_P$2") (pintype "bidirectional"))
      (node (ref "E1") (pin "1") (pinfunction "1_1") (pintype "bidirectional"))
      (node (ref "E2") (pin "1") (pinfunction "1_1") (pintype "bidirectional"))
      (node (ref "E3") (pin "1") (pinfunction "1_1") (pintype "bidirectional"))
      (node (ref "E4") (pin "1") (pinfunction "1_1") (pintype "bidirectional"))
      (node (ref "GND") (pin "P$1") (pinfunction "TP_P$1") (pintype "bidirectional"))
      (node (ref "GP0") (pin "1") (pinfunction "1_1") (pintype "bidirectional"))
      (node (ref "GP1") (pin "1") (pinfunction "1_1") (pintype "bidirectional"))
      (node (ref "GPS") (pin "2") (pinfunction "2_2") (pintype "bidirectional"))
      (node (ref "GPS") (pin "6") (pinfunction "6_6") (pintype "bidirectional"))
      (node (ref "H1") (pin "10") (pinfunction "PGND2_10") (pintype "bidirectional"))
      (node (ref "H1") (pin "18") (pinfunction "GND_18") (pintype "bidirectional"))
      (node (ref "H1") (pin "3") (pinfunction "PGND1_3") (pintype "bidirectional"))
      (node (ref "H1") (pin "4") (pinfunction "PGND1_4") (pintype "bidirectional"))
      (node (ref "H1") (pin "9") (pinfunction "PGND2_9") (pintype "bidirectional"))
      (node (ref "H2") (pin "10") (pinfunction "PGND2_10") (pintype "bidirectional"))
      (node (ref "H2") (pin "18") (pinfunction "GND_18") (pintype "bidirectional"))
      (node (ref "H2") (pin "3") (pinfunction "PGND1_3") (pintype "bidirectional"))
      (node (ref "H2") (pin "4") (pinfunction "PGND1_4") (pintype "bidirectional"))
      (node (ref "H2") (pin "9") (pinfunction "PGND2_9") (pintype "bidirectional"))
      (node (ref "I2C") (pin "1") (pinfunction "1_1") (pintype "bidirectional"))
      (node (ref "IMU") (pin "18") (pinfunction "GND_18") (pintype "bidirectional"))
      (node (ref "IMU") (pin "20") (pinfunction "RESV_20") (pintype "bidirectional"))
      (node (ref "IMU") (pin "9") (pinfunction "AD0/SDO_9") (pintype "bidirectional"))
      (node (ref "J2") (pin "P$13") (pinfunction "GND_P$13") (pintype "bidirectional"))
      (node (ref "J2") (pin "P$14") (pinfunction "GND_P$14") (pintype "bidirectional"))
      (node (ref "J2") (pin "P$15") (pinfunction "GND_P$15") (pintype "bidirectional"))
      (node (ref "J2") (pin "P$16") (pinfunction "GND_P$16") (pintype "bidirectional"))
      (node (ref "J2") (pin "P$17") (pinfunction "GND_P$17") (pintype "bidirectional"))
      (node (ref "J2") (pin "P$18") (pinfunction "GND_P$18") (pintype "bidirectional"))
      (node (ref "J2") (pin "P$23") (pinfunction "GND_P$23") (pintype "bidirectional"))
      (node (ref "J2") (pin "P$24") (pinfunction "GND_P$24") (pintype "bidirectional"))
      (node (ref "L4") (pin "1") (pinfunction "1_1") (pintype "passive"))
      (node (ref "MOD") (pin "1") (pinfunction "1_1") (pintype "passive"))
      (node (ref "OSC1") (pin "2") (pinfunction "GND_2") (pintype "bidirectional"))
      (node (ref "PAU") (pin "1") (pinfunction "1_1") (pintype "passive"))
      (node (ref "POW") (pin "1") (pinfunction "1_1") (pintype "passive"))
      (node (ref "PWR") (pin "1") (pinfunction "1_1") (pintype "bidirectional"))
      (node (ref "PWR") (pin "2") (pinfunction "2_2") (pintype "bidirectional"))
      (node (ref "Q1") (pin "5") (pinfunction "D_5") (pintype "passive"))
      (node (ref "Q1") (pin "6") (pinfunction "D_6") (pintype "passive"))
      (node (ref "Q1") (pin "7") (pinfunction "D_7") (pintype "passive"))
      (node (ref "Q1") (pin "8") (pinfunction "D_8") (pintype "passive"))
      (node (ref "R106") (pin "1") (pinfunction "1_1") (pintype "passive"))
      (node (ref "R107") (pin "1") (pinfunction "1_1") (pintype "passive"))
      (node (ref "R108") (pin "2") (pinfunction "2_2") (pintype "passive"))
      (node (ref "R110") (pin "2") (pinfunction "2_2") (pintype "passive"))
      (node (ref "R113") (pin "1") (pinfunction "1_1") (pintype "passive"))
      (node (ref "R115") (pin "1") (pinfunction "1_1") (pintype "passive"))
      (node (ref "R125") (pin "1") (pinfunction "1_1") (pintype "passive"))
      (node (ref "R127") (pin "1") (pinfunction "1_1") (pintype "passive"))
      (node (ref "R129") (pin "1") (pinfunction "1_1") (pintype "passive"))
      (node (ref "R131") (pin "1") (pinfunction "1_1") (pintype "passive"))
      (node (ref "R135") (pin "1") (pinfunction "1_1") (pintype "passive"))
      (node (ref "R14") (pin "2") (pinfunction "2_2") (pintype "passive"))
      (node (ref "R143") (pin "1") (pinfunction "1_1") (pintype "passive"))
      (node (ref "R150") (pin "2") (pinfunction "2_2") (pintype "passive"))
      (node (ref "R158") (pin "2") (pinfunction "2_2") (pintype "passive"))
      (node (ref "R16") (pin "1") (pinfunction "1_1") (pintype "passive"))
      (node (ref "R17") (pin "1") (pinfunction "1_1") (pintype "passive"))
      (node (ref "R21") (pin "2") (pinfunction "2_2") (pintype "passive"))
      (node (ref "R22") (pin "2") (pinfunction "2_2") (pintype "passive"))
      (node (ref "R24") (pin "2") (pinfunction "2_2") (pintype "passive"))
      (node (ref "R25") (pin "2") (pinfunction "2_2") (pintype "passive"))
      (node (ref "R29") (pin "2") (pinfunction "2_2") (pintype "passive"))
      (node (ref "R31") (pin "2") (pinfunction "2_2") (pintype "passive"))
      (node (ref "R32") (pin "2") (pinfunction "2_2") (pintype "passive"))
      (node (ref "R33") (pin "2") (pinfunction "2_2") (pintype "passive"))
      (node (ref "R46") (pin "1") (pinfunction "1_1") (pintype "passive"))
      (node (ref "R47") (pin "1") (pinfunction "1_1") (pintype "passive"))
      (node (ref "R48") (pin "1") (pinfunction "1_1") (pintype "passive"))
      (node (ref "R50") (pin "2") (pinfunction "2_2") (pintype "passive"))
      (node (ref "R51") (pin "2") (pinfunction "2_2") (pintype "passive"))
      (node (ref "R52") (pin "2") (pinfunction "2_2") (pintype "passive"))
      (node (ref "R53") (pin "2") (pinfunction "2_2") (pintype "passive"))
      (node (ref "R59") (pin "1") (pinfunction "1_1") (pintype "passive"))
      (node (ref "R6") (pin "1") (pinfunction "1_1") (pintype "passive"))
      (node (ref "R61") (pin "1") (pinfunction "1_1") (pintype "passive"))
      (node (ref "R62") (pin "1") (pinfunction "1_1") (pintype "passive"))
      (node (ref "R63") (pin "1") (pinfunction "1_1") (pintype "passive"))
      (node (ref "R64") (pin "1") (pinfunction "1_1") (pintype "passive"))
      (node (ref "R8") (pin "2") (pinfunction "2_2") (pintype "passive"))
      (node (ref "R87") (pin "2") (pinfunction "2_2") (pintype "passive"))
      (node (ref "R88") (pin "2") (pinfunction "2_2") (pintype "passive"))
      (node (ref "R89") (pin "2") (pinfunction "2_2") (pintype "passive"))
      (node (ref "R91") (pin "2") (pinfunction "2_2") (pintype "passive"))
      (node (ref "R95") (pin "1") (pinfunction "1_1") (pintype "passive"))
      (node (ref "RST") (pin "1") (pinfunction "1_1") (pintype "passive"))
      (node (ref "S1.1") (pin "1") (pinfunction "1_1") (pintype "bidirectional"))
      (node (ref "S1.2") (pin "1") (pinfunction "1_1") (pintype "bidirectional"))
      (node (ref "SD") (pin "1") (pinfunction "1_1") (pintype "passive"))
      (node (ref "SIP") (pin "A1") (pinfunction "DGND1_A1") (pintype "bidirectional"))
      (node (ref "SIP") (pin "A18") (pinfunction "DGND2_A18") (pintype "bidirectional"))
      (node (ref "SIP") (pin "E19") (pinfunction "DGND3_E19") (pintype "bidirectional"))
      (node (ref "SIP") (pin "E20") (pinfunction "DGND4_E20") (pintype "bidirectional"))
      (node (ref "SIP") (pin "F19") (pinfunction "DGND6_F19") (pintype "bidirectional"))
      (node (ref "SIP") (pin "F8") (pinfunction "DGND5_F8") (pintype "bidirectional"))
      (node (ref "SIP") (pin "G11") (pinfunction "DGND9_G11") (pintype "bidirectional"))
      (node (ref "SIP") (pin "G12") (pinfunction "DGND10_G12") (pintype "bidirectional"))
      (node (ref "SIP") (pin "G19") (pinfunction "DGND11_G19") (pintype "bidirectional"))
      (node (ref "SIP") (pin "G8") (pinfunction "DGND7_G8") (pintype "bidirectional"))
      (node (ref "SIP") (pin "G9") (pinfunction "DGND8_G9") (pintype "bidirectional"))
      (node (ref "SIP") (pin "H10") (pinfunction "DGND16_H10") (pintype "bidirectional"))
      (node (ref "SIP") (pin "H12") (pinfunction "DGND17_H12") (pintype "bidirectional"))
      (node (ref "SIP") (pin "H19") (pinfunction "DGND18_H19") (pintype "bidirectional"))
      (node (ref "SIP") (pin "H6") (pinfunction "DGND12_H6") (pintype "bidirectional"))
      (node (ref "SIP") (pin "H7") (pinfunction "DGND13_H7") (pintype "bidirectional"))
      (node (ref "SIP") (pin "H8") (pinfunction "DGND14_H8") (pintype "bidirectional"))
      (node (ref "SIP") (pin "H9") (pinfunction "DGND15_H9") (pintype "bidirectional"))
      (node (ref "SIP") (pin "J10") (pinfunction "DGND23_J10") (pintype "bidirectional"))
      (node (ref "SIP") (pin "J11") (pinfunction "DGND24_J11") (pintype "bidirectional"))
      (node (ref "SIP") (pin "J19") (pinfunction "DGND25_J19") (pintype "bidirectional"))
      (node (ref "SIP") (pin "J20") (pinfunction "DGND26_J20") (pintype "bidirectional"))
      (node (ref "SIP") (pin "J6") (pinfunction "DGND19_J6") (pintype "bidirectional"))
      (node (ref "SIP") (pin "J7") (pinfunction "DGND20_J7") (pintype "bidirectional"))
      (node (ref "SIP") (pin "J8") (pinfunction "DGND21_J8") (pintype "bidirectional"))
      (node (ref "SIP") (pin "J9") (pinfunction "DGND22_J9") (pintype "bidirectional"))
      (node (ref "SIP") (pin "K10") (pinfunction "DGND29_K10") (pintype "bidirectional"))
      (node (ref "SIP") (pin "K11") (pinfunction "DGND30_K11") (pintype "bidirectional"))
      (node (ref "SIP") (pin "K19") (pinfunction "DGND31_K19") (pintype "bidirectional"))
      (node (ref "SIP") (pin "K7") (pinfunction "DGND27_K7") (pintype "bidirectional"))
      (node (ref "SIP") (pin "K9") (pinfunction "DGND28_K9") (pintype "bidirectional"))
      (node (ref "SIP") (pin "L10") (pinfunction "DGND32_L10") (pintype "bidirectional"))
      (node (ref "SIP") (pin "L11") (pinfunction "DGND33_L11") (pintype "bidirectional"))
      (node (ref "SIP") (pin "L12") (pinfunction "DGND34_L12") (pintype "bidirectional"))
      (node (ref "SIP") (pin "L13") (pinfunction "DGND35_L13") (pintype "bidirectional"))
      (node (ref "SIP") (pin "L19") (pinfunction "DGND36_L19") (pintype "bidirectional"))
      (node (ref "SIP") (pin "M10") (pinfunction "DGND42_M10") (pintype "bidirectional"))
      (node (ref "SIP") (pin "M12") (pinfunction "DGND43_M12") (pintype "bidirectional"))
      (node (ref "SIP") (pin "M14") (pinfunction "DGND44_M14") (pintype "bidirectional"))
      (node (ref "SIP") (pin "M19") (pinfunction "DGND45_M19") (pintype "bidirectional"))
      (node (ref "SIP") (pin "M6") (pinfunction "DGND38_M6") (pintype "bidirectional"))
      (node (ref "SIP") (pin "M7") (pinfunction "DGND39_M7") (pintype "bidirectional"))
      (node (ref "SIP") (pin "M8") (pinfunction "DGND40_M8") (pintype "bidirectional"))
      (node (ref "SIP") (pin "M9") (pinfunction "DGND41_M9") (pintype "bidirectional"))
      (node (ref "SIP") (pin "N10") (pinfunction "DGND47_N10") (pintype "bidirectional"))
      (node (ref "SIP") (pin "N11") (pinfunction "DGND48_N11") (pintype "bidirectional"))
      (node (ref "SIP") (pin "N14") (pinfunction "DGND49_N14") (pintype "bidirectional"))
      (node (ref "SIP") (pin "N19") (pinfunction "DGND50_N19") (pintype "bidirectional"))
      (node (ref "SIP") (pin "N20") (pinfunction "DGND51_N20") (pintype "bidirectional"))
      (node (ref "SIP") (pin "N7") (pinfunction "DGND46_N7") (pintype "bidirectional"))
      (node (ref "SIP") (pin "P19") (pinfunction "DGND52_P19") (pintype "bidirectional"))
      (node (ref "SIP") (pin "P20") (pinfunction "DGND53_P20") (pintype "bidirectional"))
      (node (ref "SIP") (pin "R19") (pinfunction "DGND54_R19") (pintype "bidirectional"))
      (node (ref "SIP") (pin "R20") (pinfunction "DGND55_R20") (pintype "bidirectional"))
      (node (ref "SIP") (pin "T19") (pinfunction "DGND56_T19") (pintype "bidirectional"))
      (node (ref "SIP") (pin "T20") (pinfunction "DGND57_T20") (pintype "bidirectional"))
      (node (ref "SIP") (pin "U19") (pinfunction "DGND58_U19") (pintype "bidirectional"))
      (node (ref "SIP") (pin "V1") (pinfunction "DGND59_V1") (pintype "bidirectional"))
      (node (ref "SIP") (pin "V18") (pinfunction "DGND60_V18") (pintype "bidirectional"))
      (node (ref "SIP") (pin "V19") (pinfunction "DGND61_V19") (pintype "bidirectional"))
      (node (ref "SIP") (pin "W10") (pinfunction "DGND70_W10") (pintype "bidirectional"))
      (node (ref "SIP") (pin "W11") (pinfunction "DGND71_W11") (pintype "bidirectional"))
      (node (ref "SIP") (pin "W12") (pinfunction "DGND72_W12") (pintype "bidirectional"))
      (node (ref "SIP") (pin "W13") (pinfunction "DGND73_W13") (pintype "bidirectional"))
      (node (ref "SIP") (pin "W14") (pinfunction "DGND74_W14") (pintype "bidirectional"))
      (node (ref "SIP") (pin "W15") (pinfunction "DGND75_W15") (pintype "bidirectional"))
      (node (ref "SIP") (pin "W16") (pinfunction "DGND76_W16") (pintype "bidirectional"))
      (node (ref "SIP") (pin "W17") (pinfunction "DGND77_W17") (pintype "bidirectional"))
      (node (ref "SIP") (pin "W18") (pinfunction "DGND78_W18") (pintype "bidirectional"))
      (node (ref "SIP") (pin "W19") (pinfunction "DGND79_W19") (pintype "bidirectional"))
      (node (ref "SIP") (pin "W2") (pinfunction "DGND62_W2") (pintype "bidirectional"))
      (node (ref "SIP") (pin "W20") (pinfunction "DGND80_W20") (pintype "bidirectional"))
      (node (ref "SIP") (pin "W3") (pinfunction "DGND63_W3") (pintype "bidirectional"))
      (node (ref "SIP") (pin "W5") (pinfunction "DGND65_W5") (pintype "bidirectional"))
      (node (ref "SIP") (pin "W6") (pinfunction "DGND66_W6") (pintype "bidirectional"))
      (node (ref "SIP") (pin "W7") (pinfunction "DGND67_W7") (pintype "bidirectional"))
      (node (ref "SIP") (pin "W8") (pinfunction "DGND68_W8") (pintype "bidirectional"))
      (node (ref "SIP") (pin "W9") (pinfunction "DGND69_W9") (pintype "bidirectional"))
      (node (ref "SIP") (pin "Y10") (pinfunction "DGND83_Y10") (pintype "bidirectional"))
      (node (ref "SIP") (pin "Y12") (pinfunction "DGND84_Y12") (pintype "bidirectional"))
      (node (ref "SIP") (pin "Y15") (pinfunction "DGND85_Y15") (pintype "bidirectional"))
      (node (ref "SIP") (pin "Y18") (pinfunction "DGND86_Y18") (pintype "bidirectional"))
      (node (ref "SIP") (pin "Y7") (pinfunction "DGND82_Y7") (pintype "bidirectional"))
      (node (ref "TP12") (pin "TP") (pinfunction "TP_TP") (pintype "input"))
      (node (ref "U1") (pin "2") (pinfunction "GND_2") (pintype "power_in"))
      (node (ref "U10") (pin "11") (pinfunction "GND_11") (pintype "bidirectional"))
      (node (ref "U10") (pin "TP") (pinfunction "TP_TP") (pintype "bidirectional"))
      (node (ref "U13") (pin "C4") (pinfunction "VSSQ1_C4") (pintype "bidirectional"))
      (node (ref "U13") (pin "E7") (pinfunction "VSS1_E7") (pintype "bidirectional"))
      (node (ref "U13") (pin "G5") (pinfunction "VSS2_G5") (pintype "bidirectional"))
      (node (ref "U13") (pin "H10") (pinfunction "VSS3_H10") (pintype "bidirectional"))
      (node (ref "U13") (pin "K8") (pinfunction "VSS4_K8") (pintype "bidirectional"))
      (node (ref "U13") (pin "N2") (pinfunction "VSSQ2_N2") (pintype "bidirectional"))
      (node (ref "U13") (pin "N5") (pinfunction "VSSQ3_N5") (pintype "bidirectional"))
      (node (ref "U13") (pin "P4") (pinfunction "VSSQ4_P4") (pintype "bidirectional"))
      (node (ref "U13") (pin "P6") (pinfunction "VSSQ5_P6") (pintype "bidirectional"))
      (node (ref "U2") (pin "3") (pinfunction "GND_3") (pintype "power_in"))
      (node (ref "U3") (pin "4") (pinfunction "GND_4") (pintype "bidirectional"))
      (node (ref "U4") (pin "4") (pinfunction "GND_4") (pintype "bidirectional"))
      (node (ref "U5") (pin "2") (pinfunction "VSS_2") (pintype "passive"))
      (node (ref "U6") (pin "3") (pinfunction "GND_3") (pintype "power_in"))
      (node (ref "U7") (pin "1") (pinfunction "GND1_1") (pintype "bidirectional"))
      (node (ref "U7") (pin "15") (pinfunction "GND4_15") (pintype "bidirectional"))
      (node (ref "U7") (pin "16") (pinfunction "GND5_16") (pintype "bidirectional"))
      (node (ref "U7") (pin "17") (pinfunction "GND6_17") (pintype "bidirectional"))
      (node (ref "U7") (pin "19") (pinfunction "GND7_19") (pintype "bidirectional"))
      (node (ref "U7") (pin "20") (pinfunction "GND8_20") (pintype "bidirectional"))
      (node (ref "U7") (pin "23") (pinfunction "GND9_23") (pintype "bidirectional"))
      (node (ref "U7") (pin "24") (pinfunction "GND10_24") (pintype "bidirectional"))
      (node (ref "U7") (pin "28") (pinfunction "GND11_28") (pintype "bidirectional"))
      (node (ref "U7") (pin "29") (pinfunction "GND12_29") (pintype "bidirectional"))
      (node (ref "U7") (pin "30") (pinfunction "GND13_30") (pintype "bidirectional"))
      (node (ref "U7") (pin "31") (pinfunction "GND14_31") (pintype "bidirectional"))
      (node (ref "U7") (pin "33") (pinfunction "GND15_33") (pintype "bidirectional"))
      (node (ref "U7") (pin "34") (pinfunction "GND16_34") (pintype "bidirectional"))
      (node (ref "U7") (pin "35") (pinfunction "GND17_35") (pintype "bidirectional"))
      (node (ref "U7") (pin "37") (pinfunction "GND18_37") (pintype "bidirectional"))
      (node (ref "U7") (pin "39") (pinfunction "GND19_39") (pintype "bidirectional"))
      (node (ref "U7") (pin "44") (pinfunction "GND20_44") (pintype "bidirectional"))
      (node (ref "U7") (pin "45") (pinfunction "GND21_45") (pintype "bidirectional"))
      (node (ref "U7") (pin "48") (pinfunction "GND22_48") (pintype "bidirectional"))
      (node (ref "U7") (pin "49") (pinfunction "GND23_49") (pintype "bidirectional"))
      (node (ref "U7") (pin "54") (pinfunction "GND24_54") (pintype "bidirectional"))
      (node (ref "U7") (pin "55") (pinfunction "GND25_55") (pintype "bidirectional"))
      (node (ref "U7") (pin "59") (pinfunction "GND26_59") (pintype "bidirectional"))
      (node (ref "U7") (pin "61") (pinfunction "GND27_61") (pintype "bidirectional"))
      (node (ref "U7") (pin "63") (pinfunction "GND28_63") (pintype "bidirectional"))
      (node (ref "U7") (pin "64") (pinfunction "GND29_64") (pintype "bidirectional"))
      (node (ref "U7") (pin "7") (pinfunction "GND2_7") (pintype "bidirectional"))
      (node (ref "U7") (pin "9") (pinfunction "GND3_9") (pintype "bidirectional"))
      (node (ref "U7") (pin "G1") (pinfunction "G1_G1") (pintype "bidirectional"))
      (node (ref "U7") (pin "G10") (pinfunction "G10_G10") (pintype "bidirectional"))
      (node (ref "U7") (pin "G11") (pinfunction "G11_G11") (pintype "bidirectional"))
      (node (ref "U7") (pin "G12") (pinfunction "G12_G12") (pintype "bidirectional"))
      (node (ref "U7") (pin "G13") (pinfunction "G13_G13") (pintype "bidirectional"))
      (node (ref "U7") (pin "G14") (pinfunction "G14_G14") (pintype "bidirectional"))
      (node (ref "U7") (pin "G15") (pinfunction "G15_G15") (pintype "bidirectional"))
      (node (ref "U7") (pin "G16") (pinfunction "G16_G16") (pintype "bidirectional"))
      (node (ref "U7") (pin "G17") (pinfunction "G17_G17") (pintype "bidirectional"))
      (node (ref "U7") (pin "G18") (pinfunction "G18_G18") (pintype "bidirectional"))
      (node (ref "U7") (pin "G19") (pinfunction "G19_G19") (pintype "bidirectional"))
      (node (ref "U7") (pin "G2") (pinfunction "G2_G2") (pintype "bidirectional"))
      (node (ref "U7") (pin "G20") (pinfunction "G20_G20") (pintype "bidirectional"))
      (node (ref "U7") (pin "G21") (pinfunction "G21_G21") (pintype "bidirectional"))
      (node (ref "U7") (pin "G22") (pinfunction "G22_G22") (pintype "bidirectional"))
      (node (ref "U7") (pin "G23") (pinfunction "G23_G23") (pintype "bidirectional"))
      (node (ref "U7") (pin "G24") (pinfunction "G24_G24") (pintype "bidirectional"))
      (node (ref "U7") (pin "G25") (pinfunction "G25_G25") (pintype "bidirectional"))
      (node (ref "U7") (pin "G26") (pinfunction "G26_G26") (pintype "bidirectional"))
      (node (ref "U7") (pin "G27") (pinfunction "G27_G27") (pintype "bidirectional"))
      (node (ref "U7") (pin "G28") (pinfunction "G28_G28") (pintype "bidirectional"))
      (node (ref "U7") (pin "G29") (pinfunction "G29_G29") (pintype "bidirectional"))
      (node (ref "U7") (pin "G3") (pinfunction "G3_G3") (pintype "bidirectional"))
      (node (ref "U7") (pin "G30") (pinfunction "G30_G30") (pintype "bidirectional"))
      (node (ref "U7") (pin "G31") (pinfunction "G31_G31") (pintype "bidirectional"))
      (node (ref "U7") (pin "G32") (pinfunction "G32_G32") (pintype "bidirectional"))
      (node (ref "U7") (pin "G33") (pinfunction "G33_G33") (pintype "bidirectional"))
      (node (ref "U7") (pin "G34") (pinfunction "G34_G34") (pintype "bidirectional"))
      (node (ref "U7") (pin "G35") (pinfunction "G35_G35") (pintype "bidirectional"))
      (node (ref "U7") (pin "G36") (pinfunction "G36_G36") (pintype "bidirectional"))
      (node (ref "U7") (pin "G4") (pinfunction "G4_G4") (pintype "bidirectional"))
      (node (ref "U7") (pin "G5") (pinfunction "G5_G5") (pintype "bidirectional"))
      (node (ref "U7") (pin "G6") (pinfunction "G6_G6") (pintype "bidirectional"))
      (node (ref "U7") (pin "G7") (pinfunction "G7_G7") (pintype "bidirectional"))
      (node (ref "U7") (pin "G8") (pinfunction "G8_G8") (pintype "bidirectional"))
      (node (ref "U7") (pin "G9") (pinfunction "G9_G9") (pintype "bidirectional"))
      (node (ref "U8") (pin "2") (pinfunction "GND_2") (pintype "power_in"))
      (node (ref "U9") (pin "11") (pinfunction "GND_11") (pintype "bidirectional"))
      (node (ref "U9") (pin "TP") (pinfunction "TP_TP") (pintype "bidirectional"))
      (node (ref "UT0") (pin "1") (pinfunction "1_1") (pintype "bidirectional"))
      (node (ref "UT1") (pin "1") (pinfunction "1_1") (pintype "bidirectional"))
      (node (ref "UT5") (pin "1") (pinfunction "1_1") (pintype "bidirectional"))
      (node (ref "X2") (pin "6") (pinfunction "VSS_6") (pintype "bidirectional"))
      (node (ref "X2") (pin "GND") (pinfunction "GND_GND") (pintype "bidirectional"))
      (node (ref "X4") (pin "GND") (pinfunction "GND_GND") (pintype "input"))
    )
    (net (code "40") (name "GNDA_ADC") (class "Default")
      (node (ref "C42") (pin "2") (pinfunction "2_2") (pintype "passive"))
      (node (ref "C43") (pin "2") (pinfunction "2_2") (pintype "passive"))
      (node (ref "C44") (pin "2") (pinfunction "2_2") (pintype "passive"))
      (node (ref "SIP") (pin "A6") (pinfunction "VSSA_ADC_0_A6") (pintype "bidirectional"))
      (node (ref "SIP") (pin "A9") (pinfunction "VSSA_ADC_1_A9") (pintype "bidirectional"))
      (node (ref "SIP") (pin "E8") (pinfunction "VSSA_ADC_2_E8") (pintype "bidirectional"))
    )
    (net (code "41") (name "GPIO1_17") (class "Default")
      (node (ref "GP0") (pin "4") (pinfunction "4_4") (pintype "bidirectional"))
      (node (ref "SIP") (pin "V14") (pinfunction "GPIO1_17_V14_V14") (pintype "bidirectional"))
    )
    (net (code "42") (name "GPIO1_25") (class "Default")
      (node (ref "GP0") (pin "3") (pinfunction "3_3") (pintype "bidirectional"))
      (node (ref "SIP") (pin "U16") (pinfunction "HDMIINT_GPIO1_25_U16_U16") (pintype "bidirectional"))
    )
    (net (code "43") (name "GPIO3_1") (class "Default")
      (node (ref "GP1") (pin "4") (pinfunction "4_4") (pintype "bidirectional"))
      (node (ref "SIP") (pin "H17") (pinfunction "H17_H17") (pintype "bidirectional"))
    )
    (net (code "44") (name "GPIO3_2") (class "Default")
      (node (ref "GP1") (pin "3") (pinfunction "3_3") (pintype "bidirectional"))
      (node (ref "SIP") (pin "J15") (pinfunction "J15_J15") (pintype "bidirectional"))
    )
    (net (code "45") (name "GPIO3_17") (class "Default")
      (node (ref "GP0") (pin "6") (pinfunction "6_6") (pintype "bidirectional"))
      (node (ref "SIP") (pin "C12") (pinfunction "SPI1_CS0_C12_C12") (pintype "bidirectional"))
    )
    (net (code "46") (name "GPIO3_20") (class "Default")
      (node (ref "GP0") (pin "5") (pinfunction "5_5") (pintype "bidirectional"))
      (node (ref "SIP") (pin "D13") (pinfunction "GPIO3_20_D13_D13") (pintype "bidirectional"))
    )
    (net (code "47") (name "I2C0_SCL") (class "Default")
      (node (ref "R23") (pin "1") (pinfunction "1_1") (pintype "passive"))
      (node (ref "SIP") (pin "C16") (pinfunction "I2C0_SCL_C16") (pintype "bidirectional"))
      (node (ref "SIP") (pin "C20") (pinfunction "PMIC_I2C_SCL_C20") (pintype "bidirectional"))
      (node (ref "U5") (pin "1") (pinfunction "SCL_1") (pintype "input"))
    )
    (net (code "48") (name "I2C0_SDA") (class "Default")
      (node (ref "R2") (pin "1") (pinfunction "1_1") (pintype "passive"))
      (node (ref "SIP") (pin "C17") (pinfunction "I2C0_SDA_C17") (pintype "bidirectional"))
      (node (ref "SIP") (pin "C19") (pinfunction "PMIC_I2C_SDA_C19") (pintype "bidirectional"))
      (node (ref "U5") (pin "3") (pinfunction "SDA_3") (pintype "bidirectional"))
    )
    (net (code "49") (name "I2C1_SCL") (class "Default")
      (node (ref "I2C") (pin "3") (pinfunction "3_3") (pintype "bidirectional"))
      (node (ref "R12") (pin "1") (pinfunction "1_1") (pintype "passive"))
      (node (ref "SIP") (pin "A16") (pinfunction "I2C1_SCL_A16_A16") (pintype "bidirectional"))
    )
    (net (code "50") (name "I2C1_SDA") (class "Default")
      (node (ref "I2C") (pin "4") (pinfunction "4_4") (pintype "bidirectional"))
      (node (ref "R13") (pin "2") (pinfunction "2_2") (pintype "passive"))
      (node (ref "SIP") (pin "B16") (pinfunction "I2C1_SDA_B16_B16") (pintype "bidirectional"))
    )
    (net (code "51") (name "I2C2_SCL") (class "Default")
      (node (ref "BMP") (pin "4") (pinfunction "SCK_4") (pintype "input"))
      (node (ref "IMU") (pin "23") (pinfunction "SCL/SCLK_23") (pintype "bidirectional"))
      (node (ref "R11") (pin "1") (pinfunction "1_1") (pintype "passive"))
      (node (ref "SIP") (pin "D17") (pinfunction "I2C2_SCL_D17_D17") (pintype "bidirectional"))
    )
    (net (code "52") (name "I2C2_SDA") (class "Default")
      (node (ref "BMP") (pin "3") (pinfunction "SDI_3") (pintype "bidirectional"))
      (node (ref "IMU") (pin "24") (pinfunction "SDA/SDI_24") (pintype "bidirectional"))
      (node (ref "R10") (pin "2") (pinfunction "2_2") (pintype "passive"))
      (node (ref "SIP") (pin "D18") (pinfunction "I2C2_SDA_D18_D18") (pintype "bidirectional"))
    )
    (net (code "53") (name "IMU_INT") (class "Default")
      (node (ref "IMU") (pin "12") (pinfunction "INT_12") (pintype "bidirectional"))
      (node (ref "SIP") (pin "A14") (pinfunction "GPIO3_21_A14_A14") (pintype "bidirectional"))
    )
    (net (code "54") (name "LDO_PGOOD") (class "Default")
      (node (ref "SIP") (pin "B20") (pinfunction "PMIC_OUT_LDO_PGOOD_B20") (pintype "output"))
      (node (ref "SIP") (pin "B5") (pinfunction "RTC_PWRONRSTN_B5") (pintype "bidirectional"))
    )
    (net (code "55") (name "LED_GRN") (class "Default")
      (node (ref "G") (pin "A") (pinfunction "A_A") (pintype "passive"))
      (node (ref "GP1") (pin "6") (pinfunction "6_6") (pintype "bidirectional"))
      (node (ref "SIP") (pin "T7") (pinfunction "TIMER7_T7_T7") (pintype "bidirectional"))
    )
    (net (code "56") (name "LED_RED") (class "Default")
      (node (ref "GP1") (pin "5") (pinfunction "5_5") (pintype "bidirectional"))
      (node (ref "R") (pin "A") (pinfunction "A_A") (pintype "passive"))
      (node (ref "SIP") (pin "R7") (pinfunction "TIMER4_R7_R7") (pintype "bidirectional"))
    )
    (net (code "57") (name "MCASP0_ACLKR") (class "Default")
      (node (ref "SIP") (pin "U18") (pinfunction "GPIO1_28_U18_U18") (pintype "bidirectional"))
      (node (ref "U10") (pin "20") (pinfunction "B1_20") (pintype "bidirectional"))
    )
    (net (code "58") (name "MCASP0_AXR0") (class "Default")
      (node (ref "SIP") (pin "T16") (pinfunction "USB1OC_GPIO1_26_T16_T16") (pintype "bidirectional"))
      (node (ref "U10") (pin "17") (pinfunction "B3_17") (pintype "bidirectional"))
    )
    (net (code "59") (name "MCASP0_AXR1") (class "Default")
      (node (ref "SIP") (pin "V17") (pinfunction "HDMIDIS_GPIO1_27_V17_V17") (pintype "bidirectional"))
      (node (ref "U10") (pin "16") (pinfunction "B4_16") (pintype "bidirectional"))
    )
    (net (code "60") (name "MCASP0_FSR") (class "Default")
      (node (ref "SIP") (pin "V12") (pinfunction "GPIO2_1_V12_V12") (pintype "bidirectional"))
      (node (ref "U10") (pin "18") (pinfunction "B2_18") (pintype "bidirectional"))
    )
    (net (code "61") (name "MDIR_1A") (class "Default")
      (node (ref "H1") (pin "21") (pinfunction "AIN1_21") (pintype "bidirectional"))
      (node (ref "SIP") (pin "T13") (pinfunction "GPIO2_0_T13_T13") (pintype "bidirectional"))
    )
    (net (code "62") (name "MDIR_1B") (class "Default")
      (node (ref "H1") (pin "22") (pinfunction "AIN2_22") (pintype "bidirectional"))
      (node (ref "SIP") (pin "U17") (pinfunction "UART4_TXD_U17_U17") (pintype "bidirectional"))
    )
    (net (code "63") (name "MDIR_2A") (class "Default")
      (node (ref "H1") (pin "17") (pinfunction "BIN1_17") (pintype "bidirectional"))
      (node (ref "SIP") (pin "R13") (pinfunction "GPIO1_16_R13_R13") (pintype "bidirectional"))
    )
    (net (code "64") (name "MDIR_2B") (class "Default")
      (node (ref "H1") (pin "16") (pinfunction "BIN2_16") (pintype "bidirectional"))
      (node (ref "R140") (pin "1") (pinfunction "1_1") (pintype "passive"))
      (node (ref "SIP") (pin "V4") (pinfunction "LCD_DATA14_V4_V4") (pintype "bidirectional"))
    )
    (net (code "65") (name "MDIR_3A") (class "Default")
      (node (ref "H2") (pin "21") (pinfunction "AIN1_21") (pintype "bidirectional"))
      (node (ref "R118") (pin "1") (pinfunction "1_1") (pintype "passive"))
      (node (ref "SIP") (pin "R4") (pinfunction "LCD_DATA3_R4_R4") (pintype "bidirectional"))
    )
    (net (code "66") (name "MDIR_3B") (class "Default")
      (node (ref "H2") (pin "22") (pinfunction "AIN2_22") (pintype "bidirectional"))
      (node (ref "R116") (pin "1") (pinfunction "1_1") (pintype "passive"))
      (node (ref "R77") (pin "1") (pinfunction "1_1") (pintype "passive"))
      (node (ref "SIP") (pin "R3") (pinfunction "LCD_DATA2_R3_R3") (pintype "bidirectional"))
    )
    (net (code "67") (name "MDIR_4A") (class "Default")
      (node (ref "H2") (pin "17") (pinfunction "BIN1_17") (pintype "bidirectional"))
      (node (ref "R113") (pin "2") (pinfunction "2_2") (pintype "passive"))
      (node (ref "SIP") (pin "R1") (pinfunction "LCD_DATA0_R1_R1") (pintype "bidirectional"))
    )
    (net (code "68") (name "MDIR_4B") (class "Default")
      (node (ref "H2") (pin "16") (pinfunction "BIN2_16") (pintype "bidirectional"))
      (node (ref "R115") (pin "2") (pinfunction "2_2") (pintype "passive"))
      (node (ref "SIP") (pin "R2") (pinfunction "LCD_DATA1_R2_R2") (pintype "bidirectional"))
    )
    (net (code "69") (name "MMC1_CLK") (class "Default")
      (node (ref "R15") (pin "2") (pinfunction "2_2") (pintype "passive"))
      (node (ref "R66") (pin "1") (pinfunction "1_1") (pintype "passive"))
      (node (ref "U13") (pin "M6") (pinfunction "CLK_M6") (pintype "bidirectional"))
    )
    (net (code "70") (name "MMC1_CMD") (class "Default")
      (node (ref "R67") (pin "1") (pinfunction "1_1") (pintype "passive"))
      (node (ref "SIP") (pin "V9") (pinfunction "MMC1_CMD_V9_V9") (pintype "bidirectional"))
      (node (ref "U13") (pin "M5") (pinfunction "CMD_M5") (pintype "bidirectional"))
    )
    (net (code "71") (name "MMC1_DAT0") (class "Default")
      (node (ref "R68") (pin "1") (pinfunction "1_1") (pintype "passive"))
      (node (ref "SIP") (pin "U7") (pinfunction "MMC1_DAT0_U7_U7") (pintype "bidirectional"))
      (node (ref "U13") (pin "A3") (pinfunction "DAT0_A3") (pintype "bidirectional"))
    )
    (net (code "72") (name "MMC1_DAT1") (class "Default")
      (node (ref "R69") (pin "1") (pinfunction "1_1") (pintype "passive"))
      (node (ref "SIP") (pin "V7") (pinfunction "MMC1_DAT1_V7_V7") (pintype "bidirectional"))
      (node (ref "U13") (pin "A4") (pinfunction "DAT1_A4") (pintype "bidirectional"))
    )
    (net (code "73") (name "MMC1_DAT2") (class "Default")
      (node (ref "R70") (pin "1") (pinfunction "1_1") (pintype "passive"))
      (node (ref "SIP") (pin "R8") (pinfunction "MMC1_DAT2_R8_R8") (pintype "bidirectional"))
      (node (ref "U13") (pin "A5") (pinfunction "DAT2_A5") (pintype "bidirectional"))
    )
    (net (code "74") (name "MMC1_DAT3") (class "Default")
      (node (ref "R71") (pin "1") (pinfunction "1_1") (pintype "passive"))
      (node (ref "SIP") (pin "T8") (pinfunction "MMC1_DAT3_T8_T8") (pintype "bidirectional"))
      (node (ref "U13") (pin "B2") (pinfunction "DAT3_B2") (pintype "bidirectional"))
    )
    (net (code "75") (name "MMC1_DAT4") (class "Default")
      (node (ref "R72") (pin "1") (pinfunction "1_1") (pintype "passive"))
      (node (ref "SIP") (pin "U8") (pinfunction "MMC1_DAT4_U8_U8") (pintype "bidirectional"))
      (node (ref "U13") (pin "B3") (pinfunction "DAT4_B3") (pintype "bidirectional"))
    )
    (net (code "76") (name "MMC1_DAT5") (class "Default")
      (node (ref "R73") (pin "1") (pinfunction "1_1") (pintype "passive"))
      (node (ref "SIP") (pin "V8") (pinfunction "MMC1_DAT5_V8_V8") (pintype "bidirectional"))
      (node (ref "U13") (pin "B4") (pinfunction "DAT5_B4") (pintype "bidirectional"))
    )
    (net (code "77") (name "MMC1_DAT6") (class "Default")
      (node (ref "R74") (pin "1") (pinfunction "1_1") (pintype "passive"))
      (node (ref "SIP") (pin "R9") (pinfunction "MMC1_DAT6_R9_R9") (pintype "bidirectional"))
      (node (ref "U13") (pin "B5") (pinfunction "DAT6_B5") (pintype "bidirectional"))
    )
    (net (code "78") (name "MMC1_DAT7") (class "Default")
      (node (ref "R75") (pin "1") (pinfunction "1_1") (pintype "passive"))
      (node (ref "SIP") (pin "T9") (pinfunction "MMC1_DAT7_T9_T9") (pintype "bidirectional"))
      (node (ref "U13") (pin "B6") (pinfunction "DAT7_B6") (pintype "bidirectional"))
    )
    (net (code "79") (name "MMC2_CLK") (class "Default")
      (node (ref "R76") (pin "1") (pinfunction "1_1") (pintype "passive"))
      (node (ref "U9") (pin "13") (pinfunction "B7_13") (pintype "bidirectional"))
    )
    (net (code "80") (name "MMC2_CMD") (class "Default")
      (node (ref "SIP") (pin "J16") (pinfunction "J16_J16") (pintype "bidirectional"))
      (node (ref "U9") (pin "12") (pinfunction "B8_12") (pintype "bidirectional"))
    )
    (net (code "81") (name "MMC2_DAT0") (class "Default")
      (node (ref "SIP") (pin "J17") (pinfunction "J17_J17") (pintype "bidirectional"))
      (node (ref "U9") (pin "14") (pinfunction "B6_14") (pintype "bidirectional"))
    )
    (net (code "82") (name "MMC2_DAT1") (class "Default")
      (node (ref "SIP") (pin "J18") (pinfunction "J18_J18") (pintype "bidirectional"))
      (node (ref "U9") (pin "15") (pinfunction "B5_15") (pintype "bidirectional"))
    )
    (net (code "83") (name "MMC2_DAT2") (class "Default")
      (node (ref "SIP") (pin "K15") (pinfunction "K15_K15") (pintype "bidirectional"))
      (node (ref "U9") (pin "16") (pinfunction "B4_16") (pintype "bidirectional"))
    )
    (net (code "84") (name "MMC2_DAT3") (class "Default")
      (node (ref "SIP") (pin "H16") (pinfunction "H16_H16") (pintype "bidirectional"))
      (node (ref "U9") (pin "17") (pinfunction "B3_17") (pintype "bidirectional"))
    )
    (net (code "85") (name "MODE_BTN") (class "Default")
      (node (ref "MOD") (pin "2") (pinfunction "2_2") (pintype "passive"))
      (node (ref "SIP") (pin "U6") (pinfunction "TIMER6_U6_U6") (pintype "bidirectional"))
    )
    (net (code "86") (name "MOT_STBY") (class "Default")
      (node (ref "H1") (pin "19") (pinfunction "STBY_19") (pintype "bidirectional"))
      (node (ref "H2") (pin "19") (pinfunction "STBY_19") (pintype "bidirectional"))
      (node (ref "SIP") (pin "D14") (pinfunction "GPIO0_20_D14_D14") (pintype "bidirectional"))
    )
    (net (code "87") (name "Net-(0-PadC)") (class "Default")
      (node (ref "0") (pin "C") (pinfunction "C_C") (pintype "passive"))
      (node (ref "R61") (pin "2") (pinfunction "2_2") (pintype "passive"))
    )
    (net (code "88") (name "Net-(1-PadC)") (class "Default")
      (node (ref "1") (pin "C") (pinfunction "C_C") (pintype "passive"))
      (node (ref "R62") (pin "2") (pinfunction "2_2") (pintype "passive"))
    )
    (net (code "89") (name "Net-(2-PadC)") (class "Default")
      (node (ref "2") (pin "C") (pinfunction "C_C") (pintype "passive"))
      (node (ref "R63") (pin "2") (pinfunction "2_2") (pintype "passive"))
    )
    (net (code "90") (name "Net-(3-PadC)") (class "Default")
      (node (ref "3") (pin "C") (pinfunction "C_C") (pintype "passive"))
      (node (ref "R64") (pin "2") (pinfunction "2_2") (pintype "passive"))
    )
    (net (code "91") (name "Net-(5VREG-OUT)") (class "Default")
      (node (ref "5VREG") (pin "2") (pinfunction "OUT_2") (pintype "power_in"))
      (node (ref "D1") (pin "C") (pinfunction "C_C") (pintype "passive"))
      (node (ref "L1") (pin "1") (pinfunction "1_1") (pintype "passive"))
    )
    (net (code "92") (name "Net-(5VREG-VIN)") (class "Default")
      (node (ref "5VREG") (pin "1") (pinfunction "VIN_1") (pintype "input"))
      (node (ref "C3") (pin "1") (pinfunction "1_1") (pintype "passive"))
      (node (ref "D2") (pin "C") (pinfunction "C_C") (pintype "passive"))
      (node (ref "D3") (pin "C") (pinfunction "C_C") (pintype "passive"))
    )
    (net (code "93") (name "Net-(6VREG-BS)") (class "Default")
      (node (ref "6VREG") (pin "2") (pinfunction "BS_2") (pintype "bidirectional"))
      (node (ref "C22") (pin "1") (pinfunction "1_1") (pintype "passive"))
    )
    (net (code "94") (name "Net-(6VREG-COMP)") (class "Default")
      (node (ref "6VREG") (pin "5") (pinfunction "COMP_5") (pintype "bidirectional"))
      (node (ref "R45") (pin "2") (pinfunction "2_2") (pintype "passive"))
    )
    (net (code "95") (name "Net-(6VREG-FB)") (class "Default")
      (node (ref "6VREG") (pin "6") (pinfunction "FB_6") (pintype "bidirectional"))
      (node (ref "R48") (pin "2") (pinfunction "2_2") (pintype "passive"))
      (node (ref "R49") (pin "1") (pinfunction "1_1") (pintype "passive"))
    )
    (net (code "96") (name "Net-(6VREG-FSW)") (class "Default")
      (node (ref "6VREG") (pin "4") (pinfunction "FSW_4") (pintype "bidirectional"))
      (node (ref "R47") (pin "2") (pinfunction "2_2") (pintype "passive"))
    )
    (net (code "97") (name "Net-(6VREG-LX)") (class "Default")
      (node (ref "6VREG") (pin "1") (pinfunction "LX_1") (pintype "bidirectional"))
      (node (ref "C22") (pin "2") (pinfunction "2_2") (pintype "passive"))
      (node (ref "D9") (pin "C") (pinfunction "C_C") (pintype "passive"))
      (node (ref "L3") (pin "1") (pinfunction "1_1") (pintype "passive"))
    )
    (net (code "98") (name "Net-(6VREG-SS)") (class "Default")
      (node (ref "6VREG") (pin "7") (pinfunction "SS_7") (pintype "bidirectional"))
      (node (ref "C21") (pin "2") (pinfunction "2_2") (pintype "passive"))
    )
    (net (code "99") (name "Net-(ANT1-PadSIG)") (class "Default")
      (node (ref "ANT1") (pin "SIG") (pinfunction "SIG_SIG") (pintype "bidirectional"))
      (node (ref "C48") (pin "1") (pinfunction "1_1") (pintype "passive"))
    )
    (net (code "100") (name "Net-(ANT2-PadSIG)") (class "Default")
      (node (ref "ANT2") (pin "SIG") (pinfunction "SIG_SIG") (pintype "bidirectional"))
      (node (ref "C58") (pin "1") (pinfunction "1_1") (pintype "passive"))
    )
    (net (code "101") (name "Net-(B0-PadC)") (class "Default")
      (node (ref "B0") (pin "C") (pinfunction "C_C") (pintype "passive"))
      (node (ref "R31") (pin "1") (pinfunction "1_1") (pintype "passive"))
    )
    (net (code "102") (name "Net-(B1-PadC)") (class "Default")
      (node (ref "B1") (pin "C") (pinfunction "C_C") (pintype "passive"))
      (node (ref "R29") (pin "1") (pinfunction "1_1") (pintype "passive"))
    )
    (net (code "103") (name "Net-(B2-PadC)") (class "Default")
      (node (ref "B2") (pin "C") (pinfunction "C_C") (pintype "passive"))
      (node (ref "R33") (pin "1") (pinfunction "1_1") (pintype "passive"))
    )
    (net (code "104") (name "Net-(B3-PadC)") (class "Default")
      (node (ref "B3") (pin "C") (pinfunction "C_C") (pintype "passive"))
      (node (ref "R32") (pin "1") (pinfunction "1_1") (pintype "passive"))
    )
    (net (code "105") (name "Net-(BAL-CD)") (class "Default")
      (node (ref "BAL") (pin "4") (pinfunction "CD_4") (pintype "bidirectional"))
      (node (ref "C19") (pin "1") (pinfunction "1_1") (pintype "passive"))
    )
    (net (code "106") (name "Net-(BAL-OUT)") (class "Default")
      (node (ref "BAL") (pin "8") (pinfunction "OUT_8") (pintype "bidirectional"))
      (node (ref "R7") (pin "1") (pinfunction "1_1") (pintype "passive"))
    )
    (net (code "107") (name "Net-(BAL-VC1)") (class "Default")
      (node (ref "BAL") (pin "2") (pinfunction "VC1_2") (pintype "bidirectional"))
      (node (ref "C17") (pin "1") (pinfunction "1_1") (pintype "passive"))
      (node (ref "C18") (pin "2") (pinfunction "2_2") (pintype "passive"))
      (node (ref "R30") (pin "2") (pinfunction "2_2") (pintype "passive"))
    )
    (net (code "108") (name "Net-(BAL-VC1_CB)") (class "Default")
      (node (ref "BAL") (pin "3") (pinfunction "VC1_CB_3") (pintype "bidirectional"))
      (node (ref "R27") (pin "2") (pinfunction "2_2") (pintype "passive"))
    )
    (net (code "109") (name "Net-(BAL-VC2)") (class "Default")
      (node (ref "BAL") (pin "1") (pinfunction "VC2_1") (pintype "bidirectional"))
      (node (ref "C17") (pin "2") (pinfunction "2_2") (pintype "passive"))
      (node (ref "R28") (pin "2") (pinfunction "2_2") (pintype "passive"))
    )
    (net (code "110") (name "Net-(BAL-VDD)") (class "Default")
      (node (ref "BAL") (pin "7") (pinfunction "VDD_7") (pintype "bidirectional"))
      (node (ref "C1") (pin "1") (pinfunction "1_1") (pintype "passive"))
      (node (ref "R34") (pin "2") (pinfunction "2_2") (pintype "passive"))
    )
    (net (code "111") (name "Net-(C23-Pad2)") (class "Default")
      (node (ref "C23") (pin "2") (pinfunction "2_2") (pintype "passive"))
      (node (ref "J2") (pin "P$10") (pinfunction "PWR_P$10") (pintype "bidirectional"))
      (node (ref "J2") (pin "P$11") (pinfunction "PWR_P$11") (pintype "bidirectional"))
      (node (ref "J2") (pin "P$12") (pinfunction "PWR_P$12") (pintype "bidirectional"))
      (node (ref "J2") (pin "P$21") (pinfunction "PWR_P$21") (pintype "bidirectional"))
      (node (ref "J2") (pin "P$22") (pinfunction "PWR_P$22") (pintype "bidirectional"))
      (node (ref "J2") (pin "P$7") (pinfunction "PWR_P$7") (pintype "bidirectional"))
      (node (ref "J2") (pin "P$8") (pinfunction "PWR_P$8") (pintype "bidirectional"))
      (node (ref "J2") (pin "P$9") (pinfunction "PWR_P$9") (pintype "bidirectional"))
      (node (ref "L3") (pin "2") (pinfunction "2_2") (pintype "passive"))
      (node (ref "R49") (pin "2") (pinfunction "2_2") (pintype "passive"))
    )
    (net (code "112") (name "Net-(C24-Pad2)") (class "Default")
      (node (ref "C24") (pin "2") (pinfunction "2_2") (pintype "passive"))
      (node (ref "R45") (pin "1") (pinfunction "1_1") (pintype "passive"))
    )
    (net (code "113") (name "Net-(CHG-PadC)") (class "Default")
      (node (ref "CHG") (pin "C") (pinfunction "C_C") (pintype "passive"))
      (node (ref "R3") (pin "2") (pinfunction "2_2") (pintype "passive"))
    )
    (net (code "114") (name "Net-(CHGIC-BST)") (class "Default")
      (node (ref "C14") (pin "1") (pinfunction "1_1") (pintype "passive"))
      (node (ref "CHGIC") (pin "15") (pinfunction "BST_15") (pintype "bidirectional"))
    )
    (net (code "115") (name "Net-(CHGIC-CHGOK)") (class "Default")
      (node (ref "CHGIC") (pin "11") (pinfunction "CHGOK_11") (pintype "bidirectional"))
      (node (ref "R3") (pin "1") (pinfunction "1_1") (pintype "passive"))
    )
    (net (code "116") (name "Net-(CHGIC-CSP)") (class "Default")
      (node (ref "CHGIC") (pin "10") (pinfunction "CSP_10") (pintype "bidirectional"))
      (node (ref "L2") (pin "2") (pinfunction "2_2") (pintype "passive"))
      (node (ref "R4") (pin "2") (pinfunction "2_2") (pintype "passive"))
    )
    (net (code "117") (name "Net-(CHGIC-NTC)") (class "Default")
      (node (ref "CHGIC") (pin "13") (pinfunction "NTC_13") (pintype "bidirectional"))
      (node (ref "R5") (pin "1") (pinfunction "1_1") (pintype "passive"))
      (node (ref "R6") (pin "2") (pinfunction "2_2") (pintype "passive"))
    )
    (net (code "118") (name "Net-(CHGIC-SW)") (class "Default")
      (node (ref "C14") (pin "2") (pinfunction "2_2") (pintype "passive"))
      (node (ref "CHGIC") (pin "1") (pinfunction "SW_1") (pintype "bidirectional"))
      (node (ref "L2") (pin "1") (pinfunction "1_1") (pintype "passive"))
    )
    (net (code "119") (name "Net-(CHGIC-TMR)") (class "Default")
      (node (ref "C10") (pin "2") (pinfunction "2_2") (pintype "passive"))
      (node (ref "CHGIC") (pin "14") (pinfunction "TMR_14") (pintype "bidirectional"))
    )
    (net (code "120") (name "Net-(G-PadC)") (class "Default")
      (node (ref "G") (pin "C") (pinfunction "C_C") (pintype "passive"))
      (node (ref "R22") (pin "1") (pinfunction "1_1") (pintype "passive"))
    )
    (net (code "121") (name "Net-(IMU-REGOUT)") (class "Default")
      (node (ref "C6") (pin "1") (pinfunction "1_1") (pintype "passive"))
      (node (ref "IMU") (pin "10") (pinfunction "REGOUT_10") (pintype "bidirectional"))
    )
    (net (code "122") (name "Net-(J2-1)") (class "Default")
      (node (ref "J2") (pin "P$1") (pinfunction "1_P$1") (pintype "bidirectional"))
      (node (ref "R36") (pin "2") (pinfunction "2_2") (pintype "passive"))
    )
    (net (code "123") (name "Net-(J2-2)") (class "Default")
      (node (ref "J2") (pin "P$2") (pinfunction "2_P$2") (pintype "bidirectional"))
      (node (ref "R37") (pin "2") (pinfunction "2_2") (pintype "passive"))
    )
    (net (code "124") (name "Net-(J2-3)") (class "Default")
      (node (ref "J2") (pin "P$3") (pinfunction "3_P$3") (pintype "bidirectional"))
      (node (ref "R38") (pin "2") (pinfunction "2_2") (pintype "passive"))
    )
    (net (code "125") (name "Net-(J2-4)") (class "Default")
      (node (ref "J2") (pin "P$4") (pinfunction "4_P$4") (pintype "bidirectional"))
      (node (ref "R39") (pin "2") (pinfunction "2_2") (pintype "passive"))
    )
    (net (code "126") (name "Net-(J2-5)") (class "Default")
      (node (ref "J2") (pin "P$5") (pinfunction "5_P$5") (pintype "bidirectional"))
      (node (ref "R40") (pin "2") (pinfunction "2_2") (pintype "passive"))
    )
    (net (code "127") (name "Net-(J2-6)") (class "Default")
      (node (ref "J2") (pin "P$6") (pinfunction "6_P$6") (pintype "bidirectional"))
      (node (ref "R41") (pin "2") (pinfunction "2_2") (pintype "passive"))
    )
    (net (code "128") (name "Net-(J2-7)") (class "Default")
      (node (ref "J2") (pin "P$19") (pinfunction "7_P$19") (pintype "bidirectional"))
      (node (ref "R42") (pin "2") (pinfunction "2_2") (pintype "passive"))
    )
    (net (code "129") (name "Net-(J2-8)") (class "Default")
      (node (ref "J2") (pin "P$20") (pinfunction "8_P$20") (pintype "bidirectional"))
      (node (ref "R43") (pin "2") (pinfunction "2_2") (pintype "passive"))
    )
    (net (code "130") (name "Net-(M1-1)") (class "Default")
      (node (ref "H1") (pin "5") (pinfunction "A02_5") (pintype "bidirectional"))
      (node (ref "H1") (pin "6") (pinfunction "A02_6") (pintype "bidirectional"))
      (node (ref "M1") (pin "P$1") (pinfunction "1_P$1") (pintype "bidirectional"))
    )
    (net (code "131") (name "Net-(M1-2)") (class "Default")
      (node (ref "H1") (pin "1") (pinfunction "A01_1") (pintype "bidirectional"))
      (node (ref "H1") (pin "2") (pinfunction "A01_2") (pintype "bidirectional"))
      (node (ref "M1") (pin "P$2") (pinfunction "2_P$2") (pintype "bidirectional"))
    )
    (net (code "132") (name "Net-(M2-1)") (class "Default")
      (node (ref "H1") (pin "11") (pinfunction "B01_11") (pintype "bidirectional"))
      (node (ref "H1") (pin "12") (pinfunction "B01_12") (pintype "bidirectional"))
      (node (ref "M2") (pin "P$1") (pinfunction "1_P$1") (pintype "bidirectional"))
    )
    (net (code "133") (name "Net-(M2-2)") (class "Default")
      (node (ref "H1") (pin "7") (pinfunction "B02_7") (pintype "bidirectional"))
      (node (ref "H1") (pin "8") (pinfunction "B02_8") (pintype "bidirectional"))
      (node (ref "M2") (pin "P$2") (pinfunction "2_P$2") (pintype "bidirectional"))
    )
    (net (code "134") (name "Net-(M3-1)") (class "Default")
      (node (ref "H2") (pin "1") (pinfunction "A01_1") (pintype "bidirectional"))
      (node (ref "H2") (pin "2") (pinfunction "A01_2") (pintype "bidirectional"))
      (node (ref "M3") (pin "P$1") (pinfunction "1_P$1") (pintype "bidirectional"))
    )
    (net (code "135") (name "Net-(M3-2)") (class "Default")
      (node (ref "H2") (pin "5") (pinfunction "A02_5") (pintype "bidirectional"))
      (node (ref "H2") (pin "6") (pinfunction "A02_6") (pintype "bidirectional"))
      (node (ref "M3") (pin "P$2") (pinfunction "2_P$2") (pintype "bidirectional"))
    )
    (net (code "136") (name "Net-(M4-1)") (class "Default")
      (node (ref "H2") (pin "7") (pinfunction "B02_7") (pintype "bidirectional"))
      (node (ref "H2") (pin "8") (pinfunction "B02_8") (pintype "bidirectional"))
      (node (ref "M4") (pin "P$1") (pinfunction "1_P$1") (pintype "bidirectional"))
    )
    (net (code "137") (name "Net-(M4-2)") (class "Default")
      (node (ref "H2") (pin "11") (pinfunction "B01_11") (pintype "bidirectional"))
      (node (ref "H2") (pin "12") (pinfunction "B01_12") (pintype "bidirectional"))
      (node (ref "M4") (pin "P$2") (pinfunction "2_P$2") (pintype "bidirectional"))
    )
    (net (code "138") (name "Net-(OSC1-EN)") (class "Default")
      (node (ref "OSC1") (pin "1") (pinfunction "EN_1") (pintype "bidirectional"))
      (node (ref "R90") (pin "1") (pinfunction "1_1") (pintype "passive"))
    )
    (net (code "139") (name "Net-(PROT-VDD)") (class "Default")
      (node (ref "C15") (pin "2") (pinfunction "2_2") (pintype "passive"))
      (node (ref "PROT") (pin "5") (pinfunction "VDD_5") (pintype "bidirectional"))
      (node (ref "R44") (pin "2") (pinfunction "2_2") (pintype "passive"))
    )
    (net (code "140") (name "Net-(R-PadC)") (class "Default")
      (node (ref "R") (pin "C") (pinfunction "C_C") (pintype "passive"))
      (node (ref "R21") (pin "1") (pinfunction "1_1") (pintype "passive"))
    )
    (net (code "141") (name "Net-(R76-Pad2)") (class "Default")
      (node (ref "R76") (pin "2") (pinfunction "2_2") (pintype "passive"))
      (node (ref "SIP") (pin "L15") (pinfunction "L15_L15") (pintype "bidirectional"))
    )
    (net (code "142") (name "Net-(R91-Pad1)") (class "Default")
      (node (ref "R91") (pin "1") (pinfunction "1_1") (pintype "passive"))
      (node (ref "WIFI") (pin "C") (pinfunction "C_C") (pintype "passive"))
    )
    (net (code "143") (name "Net-(SIPA-PMIC_IN_PWR_EN)") (class "Default")
      (node (ref "SIP") (pin "C6") (pinfunction "PMIC_POWER_EN_C6") (pintype "output"))
      (node (ref "SIP") (pin "D19") (pinfunction "PMIC_IN_PWR_EN_D19") (pintype "input"))
      (node (ref "TP5") (pin "TP") (pinfunction "TP_TP") (pintype "input"))
    )
    (net (code "144") (name "Net-(SIPB-JTAG_EMU0)") (class "Default")
      (node (ref "EMU1") (pin "TP") (pinfunction "TP_TP") (pintype "input"))
      (node (ref "SIP") (pin "C14") (pinfunction "JTAG_EMU0_C14") (pintype "bidirectional"))
    )
    (net (code "145") (name "Net-(SIPB-JTAG_EMU1)") (class "Default")
      (node (ref "EMU0") (pin "TP") (pinfunction "TP_TP") (pintype "input"))
      (node (ref "SIP") (pin "B14") (pinfunction "JTAG_EMU1_B14") (pintype "bidirectional"))
    )
    (net (code "146") (name "Net-(SIPB-JTAG_TCK)") (class "Default")
      (node (ref "SIP") (pin "A12") (pinfunction "JTAG_TCK_A12") (pintype "bidirectional"))
      (node (ref "TCK") (pin "TP") (pinfunction "TP_TP") (pintype "input"))
    )
    (net (code "147") (name "Net-(SIPB-JTAG_TDI)") (class "Default")
      (node (ref "SIP") (pin "B11") (pinfunction "JTAG_TDI_B11") (pintype "bidirectional"))
      (node (ref "TDI") (pin "TP") (pinfunction "TP_TP") (pintype "input"))
    )
    (net (code "148") (name "Net-(SIPB-JTAG_TDO)") (class "Default")
      (node (ref "SIP") (pin "A11") (pinfunction "JTAG_TDO_A11") (pintype "bidirectional"))
      (node (ref "TDO") (pin "TP") (pinfunction "TP_TP") (pintype "input"))
    )
    (net (code "149") (name "Net-(SIPB-JTAG_TMS)") (class "Default")
      (node (ref "SIP") (pin "C11") (pinfunction "JTAG_TMS_C11") (pintype "bidirectional"))
      (node (ref "TMS") (pin "TP") (pinfunction "TP_TP") (pintype "input"))
    )
    (net (code "150") (name "Net-(SIPB-JTAG_TRSTN)") (class "Default")
      (node (ref "R59") (pin "2") (pinfunction "2_2") (pintype "passive"))
      (node (ref "SIP") (pin "B10") (pinfunction "JTAG_TRSTN_B10") (pintype "bidirectional"))
      (node (ref "TRSTN") (pin "TP") (pinfunction "TP_TP") (pintype "input"))
    )
    (net (code "151") (name "Net-(SIPB-MMC0_CD_C15)") (class "Default")
      (node (ref "R65") (pin "1") (pinfunction "1_1") (pintype "passive"))
      (node (ref "SIP") (pin "C15") (pinfunction "MMC0_CD_C15_C15") (pintype "bidirectional"))
      (node (ref "X2") (pin "CD") (pinfunction "CD#_CD") (pintype "bidirectional"))
    )
    (net (code "152") (name "Net-(SIPB-MMC0_CLK_G17)") (class "Default")
      (node (ref "R57") (pin "1") (pinfunction "1_1") (pintype "passive"))
      (node (ref "SIP") (pin "G17") (pinfunction "MMC0_CLK_G17_G17") (pintype "bidirectional"))
      (node (ref "X2") (pin "5") (pinfunction "CLK_5") (pintype "bidirectional"))
    )
    (net (code "153") (name "Net-(SIPB-MMC0_CMD_G18)") (class "Default")
      (node (ref "R56") (pin "1") (pinfunction "1_1") (pintype "passive"))
      (node (ref "SIP") (pin "G18") (pinfunction "MMC0_CMD_G18_G18") (pintype "bidirectional"))
      (node (ref "X2") (pin "3") (pinfunction "CMD/DI_3") (pintype "bidirectional"))
    )
    (net (code "154") (name "Net-(SIPB-MMC0_DAT0_G16)") (class "Default")
      (node (ref "R55") (pin "1") (pinfunction "1_1") (pintype "passive"))
      (node (ref "SIP") (pin "G16") (pinfunction "MMC0_DAT0_G16_G16") (pintype "bidirectional"))
      (node (ref "X2") (pin "7") (pinfunction "DAT0/DO_7") (pintype "bidirectional"))
    )
    (net (code "155") (name "Net-(SIPB-MMC0_DAT1_G15)") (class "Default")
      (node (ref "R54") (pin "1") (pinfunction "1_1") (pintype "passive"))
      (node (ref "SIP") (pin "G15") (pinfunction "MMC0_DAT1_G15_G15") (pintype "bidirectional"))
      (node (ref "X2") (pin "8") (pinfunction "DAT1_8") (pintype "bidirectional"))
    )
    (net (code "156") (name "Net-(SIPB-MMC0_DAT2_F18)") (class "Default")
      (node (ref "R35") (pin "1") (pinfunction "1_1") (pintype "passive"))
      (node (ref "SIP") (pin "F18") (pinfunction "MMC0_DAT2_F18_F18") (pintype "bidirectional"))
      (node (ref "X2") (pin "1") (pinfunction "DAT2_1") (pintype "bidirectional"))
    )
    (net (code "157") (name "Net-(SIPB-MMC0_DAT3_F17)") (class "Default")
      (node (ref "R26") (pin "1") (pinfunction "1_1") (pintype "passive"))
      (node (ref "SIP") (pin "F17") (pinfunction "MMC0_DAT3_F17_F17") (pintype "bidirectional"))
      (node (ref "X2") (pin "2") (pinfunction "DAT3/CS_2") (pintype "bidirectional"))
    )
    (net (code "158") (name "Net-(SIPB-MMC1_CLK_U9)") (class "Default")
      (node (ref "R15") (pin "1") (pinfunction "1_1") (pintype "passive"))
      (node (ref "SIP") (pin "U9") (pinfunction "MMC1_CLK_U9_U9") (pintype "bidirectional"))
    )
    (net (code "159") (name "Net-(SIPB-OSC0_GND)") (class "Default")
      (node (ref "C29") (pin "2") (pinfunction "2_2") (pintype "passive"))
      (node (ref "C30") (pin "2") (pinfunction "2_2") (pintype "passive"))
      (node (ref "SIP") (pin "L20") (pinfunction "OSC0_GND_L20") (pintype "bidirectional"))
    )
    (net (code "160") (name "Net-(SIPB-OSC0_IN)") (class "Default")
      (node (ref "C30") (pin "1") (pinfunction "1_1") (pintype "passive"))
      (node (ref "R20") (pin "2") (pinfunction "2_2") (pintype "passive"))
      (node (ref "SIP") (pin "M20") (pinfunction "OSC0_IN_M20") (pintype "bidirectional"))
      (node (ref "Y1") (pin "2") (pinfunction "P$2_2") (pintype "passive"))
    )
    (net (code "161") (name "Net-(SIPB-OSC0_OUT)") (class "Default")
      (node (ref "C29") (pin "1") (pinfunction "1_1") (pintype "passive"))
      (node (ref "R20") (pin "1") (pinfunction "1_1") (pintype "passive"))
      (node (ref "SIP") (pin "K20") (pinfunction "OSC0_OUT_K20") (pintype "bidirectional"))
      (node (ref "Y1") (pin "1") (pinfunction "P$1_1") (pintype "passive"))
    )
    (net (code "162") (name "Net-(SIPB-OSC1_GND)") (class "Default")
      (node (ref "C31") (pin "2") (pinfunction "2_2") (pintype "passive"))
      (node (ref "C32") (pin "1") (pinfunction "1_1") (pintype "passive"))
      (node (ref "SIP") (pin "G20") (pinfunction "OSC1_GND_G20") (pintype "bidirectional"))
    )
    (net (code "163") (name "Net-(SIPB-OSC1_IN)") (class "Default")
      (node (ref "C31") (pin "1") (pinfunction "1_1") (pintype "passive"))
      (node (ref "R18") (pin "2") (pinfunction "2_2") (pintype "passive"))
      (node (ref "SIP") (pin "H20") (pinfunction "OSC1_IN_H20") (pintype "bidirectional"))
      (node (ref "Y2") (pin "P$2") (pinfunction "P$2_P$2") (pintype "passive"))
    )
    (net (code "164") (name "Net-(SIPB-OSC1_OUT)") (class "Default")
      (node (ref "C32") (pin "2") (pinfunction "2_2") (pintype "passive"))
      (node (ref "R18") (pin "1") (pinfunction "1_1") (pintype "passive"))
      (node (ref "SIP") (pin "F20") (pinfunction "OSC1_OUT_F20") (pintype "bidirectional"))
      (node (ref "Y2") (pin "P$1") (pinfunction "P$1_P$1") (pintype "passive"))
    )
    (net (code "165") (name "Net-(SIPC-ADC_VREFP)") (class "Default")
      (node (ref "C42") (pin "1") (pinfunction "1_1") (pintype "passive"))
      (node (ref "C43") (pin "1") (pinfunction "1_1") (pintype "passive"))
      (node (ref "R111") (pin "2") (pinfunction "2_2") (pintype "passive"))
      (node (ref "SIP") (pin "B9") (pinfunction "ADC_VREFP_B9") (pintype "bidirectional"))
    )
    (net (code "166") (name "Net-(SIPC-AIN7)") (class "Default")
      (node (ref "R109") (pin "2") (pinfunction "2_2") (pintype "passive"))
      (node (ref "R110") (pin "1") (pinfunction "1_1") (pintype "passive"))
      (node (ref "SIP") (pin "C9") (pinfunction "AIN7_C9") (pintype "bidirectional"))
    )
    (net (code "167") (name "Net-(SIPC-LCD_DATA11_U4)") (class "Default")
      (node (ref "R135") (pin "2") (pinfunction "2_2") (pintype "passive"))
      (node (ref "SIP") (pin "U4") (pinfunction "LCD_DATA11_U4_U4") (pintype "bidirectional"))
    )
    (net (code "168") (name "Net-(SIPC-USB0_VBUS)") (class "Default")
      (node (ref "R149") (pin "1") (pinfunction "1_1") (pintype "passive"))
      (node (ref "SIP") (pin "P15") (pinfunction "USB0_VBUS_P15") (pintype "bidirectional"))
    )
    (net (code "169") (name "Net-(SIPC-USB1_ID)") (class "Default")
      (node (ref "R150") (pin "1") (pinfunction "1_1") (pintype "passive"))
      (node (ref "SIP") (pin "P17") (pinfunction "USB1_ID_P17") (pintype "bidirectional"))
    )
    (net (code "170") (name "Net-(SIPC-USB1_VBUS)") (class "Default")
      (node (ref "R156") (pin "1") (pinfunction "1_1") (pintype "passive"))
      (node (ref "SIP") (pin "T18") (pinfunction "USB1_VBUS_T18") (pintype "bidirectional"))
    )
    (net (code "171") (name "Net-(SIPE-RTC_KALDO_ENN)") (class "Default")
      (node (ref "R158") (pin "1") (pinfunction "1_1") (pintype "passive"))
      (node (ref "SIP") (pin "B4") (pinfunction "RTC_KALDO_ENN_B4") (pintype "bidirectional"))
    )
    (net (code "172") (name "Net-(U5-WP)") (class "Default")
      (node (ref "R58") (pin "1") (pinfunction "1_1") (pintype "passive"))
      (node (ref "U5") (pin "5") (pinfunction "WP_5") (pintype "input"))
      (node (ref "WP") (pin "P$1") (pinfunction "TP_P$1") (pintype "bidirectional"))
    )
    (net (code "173") (name "Net-(U7-BT_AUD_CLK)") (class "Default")
      (node (ref "R124") (pin "2") (pinfunction "2_2") (pintype "passive"))
      (node (ref "U7") (pin "60") (pinfunction "BT_AUD_CLK_60") (pintype "bidirectional"))
    )
    (net (code "174") (name "Net-(U7-BT_AUD_FSYNC)") (class "Default")
      (node (ref "R123") (pin "2") (pinfunction "2_2") (pintype "passive"))
      (node (ref "U7") (pin "58") (pinfunction "BT_AUD_FSYNC_58") (pintype "bidirectional"))
    )
    (net (code "175") (name "Net-(U7-BT_AUD_IN)") (class "Default")
      (node (ref "R97") (pin "2") (pinfunction "2_2") (pintype "passive"))
      (node (ref "U7") (pin "56") (pinfunction "BT_AUD_IN_56") (pintype "bidirectional"))
    )
    (net (code "176") (name "Net-(U7-BT_AUD_OUT)") (class "Default")
      (node (ref "R100") (pin "2") (pinfunction "2_2") (pintype "passive"))
      (node (ref "U7") (pin "57") (pinfunction "BT_AUD_OUT_57") (pintype "bidirectional"))
    )
    (net (code "177") (name "Net-(U7-BT_HCI_CTS)") (class "Default")
      (node (ref "R86") (pin "2") (pinfunction "2_2") (pintype "passive"))
      (node (ref "U7") (pin "51") (pinfunction "BT_HCI_CTS_51") (pintype "bidirectional"))
    )
    (net (code "178") (name "Net-(U7-BT_HCI_RTS)") (class "Default")
      (node (ref "R85") (pin "2") (pinfunction "2_2") (pintype "passive"))
      (node (ref "U7") (pin "50") (pinfunction "BT_HCI_RTS_50") (pintype "bidirectional"))
    )
    (net (code "179") (name "Net-(U7-BT_HCI_RX)") (class "Default")
      (node (ref "R96") (pin "2") (pinfunction "2_2") (pintype "passive"))
      (node (ref "U7") (pin "53") (pinfunction "BT_HCI_RX_53") (pintype "bidirectional"))
    )
    (net (code "180") (name "Net-(U7-BT_HCI_TX)") (class "Default")
      (node (ref "R92") (pin "2") (pinfunction "2_2") (pintype "passive"))
      (node (ref "U7") (pin "52") (pinfunction "BT_HCI_TX_52") (pintype "bidirectional"))
    )
    (net (code "181") (name "Net-(U7-RF_ANT1)") (class "Default")
      (node (ref "C48") (pin "2") (pinfunction "2_2") (pintype "passive"))
      (node (ref "U7") (pin "32") (pinfunction "RF_ANT1_32") (pintype "bidirectional"))
    )
    (net (code "182") (name "Net-(U7-RF_ANT2)") (class "Default")
      (node (ref "C58") (pin "2") (pinfunction "2_2") (pintype "passive"))
      (node (ref "U7") (pin "18") (pinfunction "RF_ANT2_18") (pintype "bidirectional"))
    )
    (net (code "183") (name "Net-(U7-WLAN_IRQ)") (class "Default")
      (node (ref "R84") (pin "2") (pinfunction "2_2") (pintype "passive"))
      (node (ref "R9") (pin "2") (pinfunction "2_2") (pintype "passive"))
      (node (ref "U7") (pin "14") (pinfunction "WLAN_IRQ_14") (pintype "bidirectional"))
    )
    (net (code "184") (name "Net-(U7-WL_SDIO_CLK)") (class "Default")
      (node (ref "R78") (pin "2") (pinfunction "2_2") (pintype "passive"))
      (node (ref "U7") (pin "8") (pinfunction "WL_SDIO_CLK_8") (pintype "bidirectional"))
    )
    (net (code "185") (name "Net-(U7-WL_SDIO_CMD)") (class "Default")
      (node (ref "R79") (pin "2") (pinfunction "2_2") (pintype "passive"))
      (node (ref "U7") (pin "6") (pinfunction "WL_SDIO_CMD_6") (pintype "bidirectional"))
    )
    (net (code "186") (name "Net-(U7-WL_SDIO_D0)") (class "Default")
      (node (ref "R80") (pin "2") (pinfunction "2_2") (pintype "passive"))
      (node (ref "U7") (pin "10") (pinfunction "WL_SDIO_D0_10") (pintype "bidirectional"))
    )
    (net (code "187") (name "Net-(U7-WL_SDIO_D1)") (class "Default")
      (node (ref "R81") (pin "2") (pinfunction "2_2") (pintype "passive"))
      (node (ref "U7") (pin "11") (pinfunction "WL_SDIO_D1_11") (pintype "bidirectional"))
    )
    (net (code "188") (name "Net-(U7-WL_SDIO_D2)") (class "Default")
      (node (ref "R82") (pin "2") (pinfunction "2_2") (pintype "passive"))
      (node (ref "U7") (pin "12") (pinfunction "WL_SDIO_D2_12") (pintype "bidirectional"))
    )
    (net (code "189") (name "Net-(U7-WL_SDIO_D3)") (class "Default")
      (node (ref "R83") (pin "2") (pinfunction "2_2") (pintype "passive"))
      (node (ref "U7") (pin "13") (pinfunction "WL_SDIO_D3_13") (pintype "bidirectional"))
    )
    (net (code "190") (name "Net-(U10-OE)") (class "Default")
      (node (ref "R106") (pin "2") (pinfunction "2_2") (pintype "passive"))
      (node (ref "R93") (pin "2") (pinfunction "2_2") (pintype "passive"))
      (node (ref "U10") (pin "10") (pinfunction "OE_10") (pintype "bidirectional"))
      (node (ref "U2") (pin "1") (pinfunction "OE_1") (pintype "input"))
      (node (ref "U9") (pin "10") (pinfunction "OE_10") (pintype "bidirectional"))
    )
    (net (code "191") (name "Net-(U13-VDDI)") (class "Default")
      (node (ref "C36") (pin "1") (pinfunction "1_1") (pintype "passive"))
      (node (ref "U13") (pin "C2") (pinfunction "VDDI_C2") (pintype "bidirectional"))
    )
    (net (code "192") (name "Net-(X3-GND)") (class "Default")
      (node (ref "L4") (pin "2") (pinfunction "2_2") (pintype "passive"))
      (node (ref "X3") (pin "4") (pinfunction "GND_4") (pintype "bidirectional"))
    )
    (net (code "193") (name "Net-(X3-VBUS)") (class "Default")
      (node (ref "L5") (pin "2") (pinfunction "2_2") (pintype "passive"))
      (node (ref "X3") (pin "1") (pinfunction "VBUS_1") (pintype "bidirectional"))
    )
    (net (code "194") (name "PAUSE_BTN") (class "Default")
      (node (ref "PAU") (pin "2") (pinfunction "2_2") (pintype "passive"))
      (node (ref "SIP") (pin "T6") (pinfunction "TIMER5_T6_T6") (pintype "bidirectional"))
    )
    (net (code "195") (name "PMIC_INT") (class "Default")
      (node (ref "SIP") (pin "B18") (pinfunction "EXTINTN_B18") (pintype "bidirectional"))
      (node (ref "SIP") (pin "B19") (pinfunction "PMIC_OUT_NINT_B19") (pintype "output"))
    )
    (net (code "196") (name "PMIC_NWAKEUP") (class "Default")
      (node (ref "SIP") (pin "A19") (pinfunction "PMIC_OUT_NWAKEUP_A19") (pintype "output"))
      (node (ref "SIP") (pin "C5") (pinfunction "EXT_WAKEUP_C5") (pintype "bidirectional"))
    )
    (net (code "197") (name "PMIC_PGOOD") (class "Default")
      (node (ref "SIP") (pin "A20") (pinfunction "PMIC_OUT_PGOOD_A20") (pintype "output"))
      (node (ref "SIP") (pin "B15") (pinfunction "PWRONRSTN_B15") (pintype "bidirectional"))
      (node (ref "U6") (pin "2") (pinfunction "A_2") (pintype "input"))
    )
    (net (code "198") (name "POWER_BTN") (class "Default")
      (node (ref "POW") (pin "2") (pinfunction "2_2") (pintype "passive"))
      (node (ref "SIP") (pin "D20") (pinfunction "PMIC_IN_PB_IN_D20") (pintype "bidirectional"))
    )
    (net (code "199") (name "PRU_E_A") (class "Default")
      (node (ref "E4") (pin "3") (pinfunction "3_3") (pintype "bidirectional"))
      (node (ref "SIP") (pin "V13") (pinfunction "GPIO1_14_V13_V13") (pintype "bidirectional"))
    )
    (net (code "200") (name "PRU_E_B") (class "Default")
      (node (ref "E4") (pin "4") (pinfunction "4_4") (pintype "bidirectional"))
      (node (ref "SIP") (pin "U13") (pinfunction "GPIO1_15_U13_U13") (pintype "bidirectional"))
    )
    (net (code "201") (name "PWM_1A") (class "Default")
      (node (ref "H1") (pin "23") (pinfunction "PWMA_23") (pintype "bidirectional"))
      (node (ref "SIP") (pin "U14") (pinfunction "EHRPWM1A_U14_U14") (pintype "bidirectional"))
    )
    (net (code "202") (name "PWM_1B") (class "Default")
      (node (ref "H1") (pin "15") (pinfunction "PWMB_15") (pintype "bidirectional"))
      (node (ref "SIP") (pin "T14") (pinfunction "EHRPWM1B_T14_T14") (pintype "bidirectional"))
    )
    (net (code "203") (name "PWM_2A") (class "Default")
      (node (ref "H2") (pin "23") (pinfunction "PWMA_23") (pintype "bidirectional"))
      (node (ref "SIP") (pin "U10") (pinfunction "EHRPWM2A_U10_U10") (pintype "bidirectional"))
    )
    (net (code "204") (name "PWM_2B") (class "Default")
      (node (ref "H2") (pin "15") (pinfunction "PWMB_15") (pintype "bidirectional"))
      (node (ref "SIP") (pin "T10") (pinfunction "EHRPWM2B_T10_T10") (pintype "bidirectional"))
    )
    (net (code "205") (name "PWR_LED") (class "Default")
      (node (ref "ON") (pin "C") (pinfunction "C_C") (pintype "passive"))
      (node (ref "R24") (pin "1") (pinfunction "1_1") (pintype "passive"))
    )
    (net (code "206") (name "RESET") (class "Default")
      (node (ref "C33") (pin "1") (pinfunction "1_1") (pintype "passive"))
      (node (ref "R60") (pin "1") (pinfunction "1_1") (pintype "passive"))
      (node (ref "RST") (pin "2") (pinfunction "2_2") (pintype "passive"))
      (node (ref "SIP") (pin "A10") (pinfunction "WARMRSTN_A10") (pintype "bidirectional"))
      (node (ref "U6") (pin "4") (pinfunction "Y_4") (pintype "output"))
    )
    (net (code "207") (name "SD_BOOT") (class "Default")
      (node (ref "R77") (pin "2") (pinfunction "2_2") (pintype "passive"))
      (node (ref "SD") (pin "2") (pinfunction "2_2") (pintype "passive"))
    )
    (net (code "208") (name "SERVO_EN") (class "Default")
      (node (ref "6VREG") (pin "8") (pinfunction "EN_8") (pintype "bidirectional"))
      (node (ref "R46") (pin "2") (pinfunction "2_2") (pintype "passive"))
      (node (ref "SIP") (pin "U3") (pinfunction "LCD_DATA10_U3_U3") (pintype "bidirectional"))
    )
    (net (code "209") (name "SPI1_MISO") (class "Default")
      (node (ref "S1.1") (pin "4") (pinfunction "4_4") (pintype "bidirectional"))
      (node (ref "S1.2") (pin "4") (pinfunction "4_4") (pintype "bidirectional"))
      (node (ref "SIP") (pin "B13") (pinfunction "SPI1_D0_B13_B13") (pintype "bidirectional"))
    )
    (net (code "210") (name "SPI1_MOSI") (class "Default")
      (node (ref "S1.1") (pin "3") (pinfunction "3_3") (pintype "bidirectional"))
      (node (ref "S1.2") (pin "3") (pinfunction "3_3") (pintype "bidirectional"))
      (node (ref "SIP") (pin "D12") (pinfunction "SPI1_D1_D12_D12") (pintype "bidirectional"))
    )
    (net (code "211") (name "SPI1_SCK") (class "Default")
      (node (ref "S1.1") (pin "5") (pinfunction "5_5") (pintype "bidirectional"))
      (node (ref "S1.2") (pin "5") (pinfunction "5_5") (pintype "bidirectional"))
      (node (ref "SIP") (pin "A13") (pinfunction "SPI1_CLK_A13_A13") (pintype "bidirectional"))
    )
    (net (code "212") (name "SPI1_SS1") (class "Default")
      (node (ref "S1.1") (pin "6") (pinfunction "6_6") (pintype "bidirectional"))
      (node (ref "SIP") (pin "H18") (pinfunction "H18_H18") (pintype "bidirectional"))
    )
    (net (code "213") (name "SPI1_SS2") (class "Default")
      (node (ref "S1.2") (pin "6") (pinfunction "6_6") (pintype "bidirectional"))
      (node (ref "SIP") (pin "C18") (pinfunction "GPIO0_7_C18_C18") (pintype "bidirectional"))
    )
    (net (code "214") (name "SVO1") (class "Default")
      (node (ref "R36") (pin "1") (pinfunction "1_1") (pintype "passive"))
      (node (ref "R50") (pin "1") (pinfunction "1_1") (pintype "passive"))
      (node (ref "SIP") (pin "U5") (pinfunction "LCD_VSYNC_U5_U5") (pintype "bidirectional"))
    )
    (net (code "215") (name "SVO2") (class "Default")
      (node (ref "R37") (pin "1") (pinfunction "1_1") (pintype "passive"))
      (node (ref "R51") (pin "1") (pinfunction "1_1") (pintype "passive"))
      (node (ref "SIP") (pin "V5") (pinfunction "LCD_PCLK_V5_V5") (pintype "bidirectional"))
    )
    (net (code "216") (name "SVO3") (class "Default")
      (node (ref "R38") (pin "1") (pinfunction "1_1") (pintype "passive"))
      (node (ref "R52") (pin "1") (pinfunction "1_1") (pintype "passive"))
      (node (ref "SIP") (pin "R5") (pinfunction "LCD_HSYNC_R5_R5") (pintype "bidirectional"))
    )
    (net (code "217") (name "SVO4") (class "Default")
      (node (ref "R39") (pin "1") (pinfunction "1_1") (pintype "passive"))
      (node (ref "R53") (pin "1") (pinfunction "1_1") (pintype "passive"))
      (node (ref "SIP") (pin "R6") (pinfunction "LCD_DE_R6_R6") (pintype "bidirectional"))
    )
    (net (code "218") (name "SVO5") (class "Default")
      (node (ref "R125") (pin "2") (pinfunction "2_2") (pintype "passive"))
      (node (ref "R40") (pin "1") (pinfunction "1_1") (pintype "passive"))
      (node (ref "SIP") (pin "T3") (pinfunction "LCD_DATA6_T3_T3") (pintype "bidirectional"))
    )
    (net (code "219") (name "SVO6") (class "Default")
      (node (ref "R127") (pin "2") (pinfunction "2_2") (pintype "passive"))
      (node (ref "R41") (pin "1") (pinfunction "1_1") (pintype "passive"))
      (node (ref "SIP") (pin "T4") (pinfunction "LCD_DATA7_T4_T4") (pintype "bidirectional"))
    )
    (net (code "220") (name "SVO7") (class "Default")
      (node (ref "R120") (pin "1") (pinfunction "1_1") (pintype "passive"))
      (node (ref "R42") (pin "1") (pinfunction "1_1") (pintype "passive"))
      (node (ref "SIP") (pin "T1") (pinfunction "LCD_DATA4_T1_T1") (pintype "bidirectional"))
    )
    (net (code "221") (name "SVO8") (class "Default")
      (node (ref "R122") (pin "1") (pinfunction "1_1") (pintype "passive"))
      (node (ref "R43") (pin "1") (pinfunction "1_1") (pintype "passive"))
      (node (ref "SIP") (pin "T2") (pinfunction "LCD_DATA5_T2_T2") (pintype "bidirectional"))
    )
    (net (code "222") (name "SYS_5V") (class "Default")
      (node (ref "C62") (pin "1") (pinfunction "1_1") (pintype "passive"))
      (node (ref "R121") (pin "2") (pinfunction "2_2") (pintype "passive"))
      (node (ref "SIP") (pin "W4") (pinfunction "VOUT_SYS_5V_0_W4") (pintype "power_in"))
      (node (ref "SIP") (pin "Y4") (pinfunction "VOUT_SYS_5V_1_Y4") (pintype "power_in"))
      (node (ref "TP1") (pin "TP") (pinfunction "TP_TP") (pintype "input"))
      (node (ref "U1") (pin "3") (pinfunction "VCC_3") (pintype "power_in"))
      (node (ref "U8") (pin "3") (pinfunction "IN2_3") (pintype "input"))
    )
    (net (code "223") (name "UART0_RX") (class "Default")
      (node (ref "SIP") (pin "E15") (pinfunction "UART0_RXD_E15_E15") (pintype "bidirectional"))
      (node (ref "UT0") (pin "3") (pinfunction "3_3") (pintype "bidirectional"))
    )
    (net (code "224") (name "UART0_TX") (class "Default")
      (node (ref "SIP") (pin "E16") (pinfunction "UART0_TXD_E16_E16") (pintype "bidirectional"))
      (node (ref "UT0") (pin "4") (pinfunction "4_4") (pintype "bidirectional"))
    )
    (net (code "225") (name "UART1_RX") (class "Default")
      (node (ref "SIP") (pin "D16") (pinfunction "UART1_RXD_D16_D16") (pintype "bidirectional"))
      (node (ref "UT1") (pin "3") (pinfunction "3_3") (pintype "bidirectional"))
    )
    (net (code "226") (name "UART1_TX") (class "Default")
      (node (ref "SIP") (pin "D15") (pinfunction "UART1_TXD_D15_D15") (pintype "bidirectional"))
      (node (ref "UT1") (pin "4") (pinfunction "4_4") (pintype "bidirectional"))
    )
    (net (code "227") (name "UART2_RX") (class "Default")
      (node (ref "GPS") (pin "3") (pinfunction "3_3") (pintype "bidirectional"))
      (node (ref "SIP") (pin "A17") (pinfunction "UART2_RXD_A17_A17") (pintype "bidirectional"))
    )
    (net (code "228") (name "UART2_TX") (class "Default")
      (node (ref "GPS") (pin "4") (pinfunction "4_4") (pintype "bidirectional"))
      (node (ref "SIP") (pin "B17") (pinfunction "UART2_TXD_B17_B17") (pintype "bidirectional"))
    )
    (net (code "229") (name "UART3_CTSN") (class "Default")
      (node (ref "R89") (pin "1") (pinfunction "1_1") (pintype "passive"))
      (node (ref "SIP") (pin "M17") (pinfunction "M17_M17") (pintype "bidirectional"))
      (node (ref "U10") (pin "12") (pinfunction "B8_12") (pintype "bidirectional"))
    )
    (net (code "230") (name "UART3_RTSN") (class "Default")
      (node (ref "R108") (pin "1") (pinfunction "1_1") (pintype "passive"))
      (node (ref "SIP") (pin "M18") (pinfunction "M18_M18") (pintype "bidirectional"))
      (node (ref "U10") (pin "13") (pinfunction "B7_13") (pintype "bidirectional"))
    )
    (net (code "231") (name "UART3_RX") (class "Default")
      (node (ref "SIP") (pin "L17") (pinfunction "L17_L17") (pintype "bidirectional"))
      (node (ref "U10") (pin "14") (pinfunction "B6_14") (pintype "bidirectional"))
    )
    (net (code "232") (name "UART3_TX") (class "Default")
      (node (ref "SIP") (pin "L16") (pinfunction "L16_L16") (pintype "bidirectional"))
      (node (ref "U10") (pin "15") (pinfunction "B5_15") (pintype "bidirectional"))
    )
    (net (code "233") (name "UART4_RX") (class "Default")
      (node (ref "DSM2") (pin "P$3") (pinfunction "3_P$3") (pintype "bidirectional"))
      (node (ref "SIP") (pin "T17") (pinfunction "UART4_RXD_T17_T17") (pintype "bidirectional"))
    )
    (net (code "234") (name "UART5_RX") (class "Default")
      (node (ref "R131") (pin "2") (pinfunction "2_2") (pintype "passive"))
      (node (ref "SIP") (pin "U2") (pinfunction "LCD_DATA9_U2_U2") (pintype "bidirectional"))
      (node (ref "UT5") (pin "3") (pinfunction "3_3") (pintype "bidirectional"))
    )
    (net (code "235") (name "UART5_TX") (class "Default")
      (node (ref "R129") (pin "2") (pinfunction "2_2") (pintype "passive"))
      (node (ref "SIP") (pin "U1") (pinfunction "LCD_DATA8_U1_U1") (pintype "bidirectional"))
      (node (ref "UT5") (pin "4") (pinfunction "4_4") (pintype "bidirectional"))
    )
    (net (code "236") (name "USB0_D_N") (class "Default")
      (node (ref "SIP") (pin "N18") (pinfunction "USB0_DM_N18") (pintype "bidirectional"))
      (node (ref "U3") (pin "2") (pinfunction "D-_2") (pintype "bidirectional"))
      (node (ref "X4") (pin "D-") (pinfunction "D-_D-") (pintype "input"))
    )
    (net (code "237") (name "USB0_D_P") (class "Default")
      (node (ref "SIP") (pin "N17") (pinfunction "USB0_DP_N17") (pintype "bidirectional"))
      (node (ref "U3") (pin "1") (pinfunction "D+_1") (pintype "bidirectional"))
      (node (ref "X4") (pin "D+") (pinfunction "D+_D+") (pintype "input"))
    )
    (net (code "238") (name "USB0_ID") (class "Default")
      (node (ref "SIP") (pin "P16") (pinfunction "USB0_ID_P16") (pintype "bidirectional"))
      (node (ref "U3") (pin "3") (pinfunction "ID_3") (pintype "bidirectional"))
      (node (ref "X4") (pin "ID") (pinfunction "ID_ID") (pintype "input"))
    )
    (net (code "239") (name "USB0_VBUS") (class "Default")
      (node (ref "C54") (pin "1") (pinfunction "1_1") (pintype "passive"))
      (node (ref "R112") (pin "2") (pinfunction "2_2") (pintype "passive"))
      (node (ref "R149") (pin "2") (pinfunction "2_2") (pintype "passive"))
      (node (ref "U3") (pin "6") (pinfunction "VBUS_6") (pintype "bidirectional"))
      (node (ref "X4") (pin "VBUS") (pinfunction "VBUS_VBUS") (pintype "input"))
    )
    (net (code "240") (name "USB1_D_N") (class "Default")
      (node (ref "SIP") (pin "R18") (pinfunction "USB1_DM_R18") (pintype "bidirectional"))
      (node (ref "U4") (pin "2") (pinfunction "D-_2") (pintype "bidirectional"))
      (node (ref "X3") (pin "2") (pinfunction "D-_2") (pintype "bidirectional"))
    )
    (net (code "241") (name "USB1_D_P") (class "Default")
      (node (ref "SIP") (pin "R17") (pinfunction "USB1_DP_R17") (pintype "bidirectional"))
      (node (ref "U4") (pin "1") (pinfunction "D+_1") (pintype "bidirectional"))
      (node (ref "X3") (pin "3") (pinfunction "D+_3") (pintype "bidirectional"))
    )
    (net (code "242") (name "USB1_VBUS") (class "Default")
      (node (ref "C45") (pin "1") (pinfunction "1_1") (pintype "passive"))
      (node (ref "C46") (pin "1") (pinfunction "1_1") (pintype "passive"))
      (node (ref "C55") (pin "1") (pinfunction "1_1") (pintype "passive"))
      (node (ref "C61") (pin "2") (pinfunction "2_2") (pintype "passive"))
      (node (ref "L5") (pin "1") (pinfunction "1_1") (pintype "passive"))
      (node (ref "R119") (pin "1") (pinfunction "1_1") (pintype "passive"))
      (node (ref "R121") (pin "1") (pinfunction "1_1") (pintype "passive"))
      (node (ref "R156") (pin "2") (pinfunction "2_2") (pintype "passive"))
      (node (ref "U4") (pin "6") (pinfunction "VBUS_6") (pintype "bidirectional"))
      (node (ref "U8") (pin "4") (pinfunction "OUT_4") (pintype "output"))
    )
    (net (code "243") (name "USB_DC") (class "Default")
      (node (ref "R112") (pin "1") (pinfunction "1_1") (pintype "passive"))
      (node (ref "SIP") (pin "Y8") (pinfunction "VIN_USB_0_Y8") (pintype "power_in"))
      (node (ref "SIP") (pin "Y9") (pinfunction "VIN_USB_1_Y9") (pintype "power_in"))
    )
    (net (code "244") (name "USR_LED0") (class "Default")
      (node (ref "0") (pin "A") (pinfunction "A_A") (pintype "passive"))
      (node (ref "SIP") (pin "V15") (pinfunction "USR0_V15_V15") (pintype "bidirectional"))
    )
    (net (code "245") (name "USR_LED1") (class "Default")
      (node (ref "1") (pin "A") (pinfunction "A_A") (pintype "passive"))
      (node (ref "SIP") (pin "U15") (pinfunction "USR1_U15_U15") (pintype "bidirectional"))
    )
    (net (code "246") (name "USR_LED2") (class "Default")
      (node (ref "2") (pin "A") (pinfunction "A_A") (pintype "passive"))
      (node (ref "SIP") (pin "T15") (pinfunction "USR2_T15_T15") (pintype "bidirectional"))
    )
    (net (code "247") (name "USR_LED3") (class "Default")
      (node (ref "3") (pin "A") (pinfunction "A_A") (pintype "passive"))
      (node (ref "SIP") (pin "V16") (pinfunction "USR3_V16_V16") (pintype "bidirectional"))
    )
    (net (code "248") (name "VCC") (class "Default")
      (node (ref "12V") (pin "IN") (pinfunction "IN_IN") (pintype "bidirectional"))
      (node (ref "C12") (pin "1") (pinfunction "1_1") (pintype "passive"))
      (node (ref "C7") (pin "1") (pinfunction "1_1") (pintype "passive"))
      (node (ref "CHG") (pin "A") (pinfunction "A_A") (pintype "passive"))
      (node (ref "CHGIC") (pin "2") (pinfunction "VIN_2") (pintype "bidirectional"))
      (node (ref "D3") (pin "A") (pinfunction "A_A") (pintype "passive"))
      (node (ref "R1") (pin "1") (pinfunction "1_1") (pintype "passive"))
    )
    (net (code "249") (name "VCC_CHG") (class "Default")
      (node (ref "C4") (pin "2") (pinfunction "2_2") (pintype "passive"))
      (node (ref "CHGIC") (pin "3") (pinfunction "VCC_3") (pintype "bidirectional"))
      (node (ref "R5") (pin "2") (pinfunction "2_2") (pintype "passive"))
    )
    (net (code "250") (name "VDD_1V8") (class "Default")
      (node (ref "C47") (pin "1") (pinfunction "1_1") (pintype "passive"))
      (node (ref "C50") (pin "1") (pinfunction "1_1") (pintype "passive"))
      (node (ref "C52") (pin "1") (pinfunction "1_1") (pintype "passive"))
      (node (ref "C57") (pin "2") (pinfunction "2_2") (pintype "passive"))
      (node (ref "C60") (pin "2") (pinfunction "2_2") (pintype "passive"))
      (node (ref "OSC1") (pin "4") (pinfunction "VCC_4") (pintype "bidirectional"))
      (node (ref "R101") (pin "1") (pinfunction "1_1") (pintype "passive"))
      (node (ref "R102") (pin "1") (pinfunction "1_1") (pintype "passive"))
      (node (ref "R103") (pin "1") (pinfunction "1_1") (pintype "passive"))
      (node (ref "R105") (pin "1") (pinfunction "1_1") (pintype "passive"))
      (node (ref "R9") (pin "1") (pinfunction "1_1") (pintype "passive"))
      (node (ref "R90") (pin "2") (pinfunction "2_2") (pintype "passive"))
      (node (ref "R98") (pin "1") (pinfunction "1_1") (pintype "passive"))
      (node (ref "R99") (pin "1") (pinfunction "1_1") (pintype "passive"))
      (node (ref "SIP") (pin "D10") (pinfunction "VDD_1V84_D10") (pintype "bidirectional"))
      (node (ref "SIP") (pin "E9") (pinfunction "VDD_1V83_E9") (pintype "bidirectional"))
      (node (ref "SIP") (pin "N16") (pinfunction "VOUT_LDO3_1P8V_0_N16") (pintype "power_in"))
      (node (ref "SIP") (pin "R16") (pinfunction "VOUT_LDO3_1P8V_1_R16") (pintype "power_in"))
      (node (ref "U10") (pin "2") (pinfunction "VCCA_2") (pintype "bidirectional"))
      (node (ref "U2") (pin "5") (pinfunction "VCC_5") (pintype "power_in"))
      (node (ref "U7") (pin "38") (pinfunction "VIO_38") (pintype "bidirectional"))
      (node (ref "U9") (pin "2") (pinfunction "VCCA_2") (pintype "bidirectional"))
    )
    (net (code "251") (name "VDD_3V3AUX") (class "Default")
      (node (ref "ON") (pin "A") (pinfunction "A_A") (pintype "passive"))
      (node (ref "SIP") (pin "Y11") (pinfunction "VOUT_LDO2_3P3V_Y11") (pintype "power_in"))
    )
    (net (code "252") (name "VDD_ADC") (class "Default")
      (node (ref "ADC") (pin "2") (pinfunction "2_2") (pintype "bidirectional"))
      (node (ref "C44") (pin "1") (pinfunction "1_1") (pintype "passive"))
      (node (ref "R111") (pin "1") (pinfunction "1_1") (pintype "passive"))
      (node (ref "SIP") (pin "A4") (pinfunction "VOUT_ADC_1P8V_0_A4") (pintype "bidirectional"))
      (node (ref "SIP") (pin "A5") (pinfunction "VOUT_ADC_1P8V_1_A5") (pintype "bidirectional"))
      (node (ref "SIP") (pin "D8") (pinfunction "VDDA_ADC_D8") (pintype "bidirectional"))
    )
    (net (code "253") (name "VDD_RTC") (class "Default")
      (node (ref "SIP") (pin "E14") (pinfunction "VDD_RTC3_E14") (pintype "bidirectional"))
      (node (ref "U6") (pin "5") (pinfunction "VCC_5") (pintype "power_in"))
    )
    (net (code "254") (name "VIN_BAT_0") (class "Default")
      (node (ref "SIP") (pin "Y2") (pinfunction "VIN_BAT_0_Y2") (pintype "power_in"))
    )
    (net (code "255") (name "VIN_BAT_1") (class "Default")
      (node (ref "SIP") (pin "Y3") (pinfunction "VIN_BAT_1_Y3") (pintype "power_in"))
    )
    (net (code "256") (name "V_BATT") (class "Default")
      (node (ref "6VREG") (pin "9") (pinfunction "VIN_9") (pintype "bidirectional"))
      (node (ref "C11") (pin "+") (pinfunction "+_+") (pintype "passive"))
      (node (ref "C20") (pin "2") (pinfunction "2_2") (pintype "passive"))
      (node (ref "C25") (pin "1") (pinfunction "1_1") (pintype "passive"))
      (node (ref "C26") (pin "1") (pinfunction "1_1") (pintype "passive"))
      (node (ref "CHGIC") (pin "9") (pinfunction "BATT_9") (pintype "bidirectional"))
      (node (ref "D2") (pin "A") (pinfunction "A_A") (pintype "passive"))
      (node (ref "H1") (pin "13") (pinfunction "VM2_13") (pintype "bidirectional"))
      (node (ref "H1") (pin "14") (pinfunction "VM3_14") (pintype "bidirectional"))
      (node (ref "H1") (pin "24") (pinfunction "VM1_24") (pintype "bidirectional"))
      (node (ref "H2") (pin "13") (pinfunction "VM2_13") (pintype "bidirectional"))
      (node (ref "H2") (pin "14") (pinfunction "VM3_14") (pintype "bidirectional"))
      (node (ref "H2") (pin "24") (pinfunction "VM1_24") (pintype "bidirectional"))
      (node (ref "LIPO") (pin "P$1") (pinfunction "1_P$1") (pintype "passive"))
      (node (ref "R19") (pin "1") (pinfunction "1_1") (pintype "passive"))
      (node (ref "R28") (pin "1") (pinfunction "1_1") (pintype "passive"))
      (node (ref "R34") (pin "1") (pinfunction "1_1") (pintype "passive"))
      (node (ref "R4") (pin "1") (pinfunction "1_1") (pintype "passive"))
    )
    (net (code "257") (name "V_DIV_BAT") (class "Default")
      (node (ref "R19") (pin "2") (pinfunction "2_2") (pintype "passive"))
      (node (ref "R25") (pin "1") (pinfunction "1_1") (pintype "passive"))
      (node (ref "SIP") (pin "A8") (pinfunction "AIN6_A8") (pintype "bidirectional"))
    )
    (net (code "258") (name "V_DIV_DC") (class "Default")
      (node (ref "R1") (pin "2") (pinfunction "2_2") (pintype "passive"))
      (node (ref "R14") (pin "1") (pinfunction "1_1") (pintype "passive"))
      (node (ref "SIP") (pin "B8") (pinfunction "AIN5_B8") (pintype "bidirectional"))
    )
    (net (code "259") (name "WIFI_LED") (class "Default")
      (node (ref "SIP") (pin "A15") (pinfunction "GPIO0_19_A15_A15") (pintype "bidirectional"))
      (node (ref "WIFI") (pin "A") (pinfunction "A_A") (pintype "passive"))
    )
    (net (code "260") (name "WLAN_IRQ") (class "Default")
      (node (ref "SIP") (pin "K16") (pinfunction "K16_K16") (pintype "bidirectional"))
      (node (ref "U2") (pin "4") (pinfunction "Y_4") (pintype "output"))
    )
    (net (code "261") (name "WL_BT_OE") (class "Default")
      (node (ref "R93") (pin "1") (pinfunction "1_1") (pintype "passive"))
      (node (ref "SIP") (pin "L18") (pinfunction "L18_L18") (pintype "bidirectional"))
    )
    (net (code "262") (name "WL_EN") (class "Default")
      (node (ref "SIP") (pin "K18") (pinfunction "K18_K18") (pintype "bidirectional"))
      (node (ref "U9") (pin "20") (pinfunction "B1_20") (pintype "bidirectional"))
    )
    (net (code "263") (name "WL_EN_1V8") (class "Default")
      (node (ref "R87") (pin "1") (pinfunction "1_1") (pintype "passive"))
      (node (ref "U7") (pin "40") (pinfunction "WLAN_EN_40") (pintype "bidirectional"))
      (node (ref "U9") (pin "1") (pinfunction "A1_1") (pintype "bidirectional"))
    )
    (net (code "264") (name "WL_IRQ") (class "Default")
      (node (ref "R84") (pin "1") (pinfunction "1_1") (pintype "passive"))
      (node (ref "U2") (pin "2") (pinfunction "A_2") (pintype "input"))
    )
    (net (code "265") (name "WL_SDIO_CLK") (class "Default")
      (node (ref "R103") (pin "2") (pinfunction "2_2") (pintype "passive"))
      (node (ref "R78") (pin "1") (pinfunction "1_1") (pintype "passive"))
      (node (ref "U9") (pin "8") (pinfunction "A7_8") (pintype "bidirectional"))
    )
    (net (code "266") (name "WL_SDIO_CMD") (class "Default")
      (node (ref "R105") (pin "2") (pinfunction "2_2") (pintype "passive"))
      (node (ref "R79") (pin "1") (pinfunction "1_1") (pintype "passive"))
      (node (ref "U9") (pin "9") (pinfunction "A8_9") (pintype "bidirectional"))
    )
    (net (code "267") (name "WL_SDIO_D0") (class "Default")
      (node (ref "R80") (pin "1") (pinfunction "1_1") (pintype "passive"))
      (node (ref "R98") (pin "2") (pinfunction "2_2") (pintype "passive"))
      (node (ref "U9") (pin "7") (pinfunction "A6_7") (pintype "bidirectional"))
    )
    (net (code "268") (name "WL_SDIO_D1") (class "Default")
      (node (ref "R81") (pin "1") (pinfunction "1_1") (pintype "passive"))
      (node (ref "R99") (pin "2") (pinfunction "2_2") (pintype "passive"))
      (node (ref "U9") (pin "6") (pinfunction "A5_6") (pintype "bidirectional"))
    )
    (net (code "269") (name "WL_SDIO_D2") (class "Default")
      (node (ref "R101") (pin "2") (pinfunction "2_2") (pintype "passive"))
      (node (ref "R82") (pin "1") (pinfunction "1_1") (pintype "passive"))
      (node (ref "U9") (pin "5") (pinfunction "A4_5") (pintype "bidirectional"))
    )
    (net (code "270") (name "WL_SDIO_D3") (class "Default")
      (node (ref "R102") (pin "2") (pinfunction "2_2") (pintype "passive"))
      (node (ref "R83") (pin "1") (pinfunction "1_1") (pintype "passive"))
      (node (ref "U9") (pin "4") (pinfunction "A3_4") (pintype "bidirectional"))
    )
    (net (code "271") (name "unconnected-(12V-PadOUT_CON)") (class "Default")
      (node (ref "12V") (pin "OUT_CON") (pinfunction "OUT_CON_OUT_CON") (pintype "bidirectional"))
    )
    (net (code "272") (name "unconnected-(CHGIC-ACOK-Pad12)") (class "Default")
      (node (ref "CHGIC") (pin "12") (pinfunction "ACOK_12") (pintype "bidirectional"))
    )
    (net (code "273") (name "unconnected-(CHGIC-CELL-Pad4)") (class "Default")
      (node (ref "CHGIC") (pin "4") (pinfunction "CELL_4") (pintype "bidirectional"))
    )
    (net (code "274") (name "unconnected-(CHGIC-SEL-Pad5)") (class "Default")
      (node (ref "CHGIC") (pin "5") (pinfunction "SEL_5") (pintype "bidirectional"))
    )
    (net (code "275") (name "unconnected-(FUD1-PadP$1)") (class "Default")
      (node (ref "FUD1") (pin "P$1") (pinfunction "P$1_P$1") (pintype "no_connect"))
    )
    (net (code "276") (name "unconnected-(FUD2-PadP$1)") (class "Default")
      (node (ref "FUD2") (pin "P$1") (pinfunction "P$1_P$1") (pintype "no_connect"))
    )
    (net (code "277") (name "unconnected-(FUD3-PadP$1)") (class "Default")
      (node (ref "FUD3") (pin "P$1") (pinfunction "P$1_P$1") (pintype "no_connect"))
    )
    (net (code "278") (name "unconnected-(FUD4-PadP$1)") (class "Default")
      (node (ref "FUD4") (pin "P$1") (pinfunction "P$1_P$1") (pintype "no_connect"))
    )
    (net (code "279") (name "unconnected-(FUD5-PadP$1)") (class "Default")
      (node (ref "FUD5") (pin "P$1") (pinfunction "P$1_P$1") (pintype "no_connect"))
    )
    (net (code "280") (name "unconnected-(FUD6-PadP$1)") (class "Default")
      (node (ref "FUD6") (pin "P$1") (pinfunction "P$1_P$1") (pintype "no_connect"))
    )
    (net (code "281") (name "unconnected-(GPS-Pad1)") (class "Default")
      (node (ref "GPS") (pin "1") (pinfunction "1_1") (pintype "bidirectional"))
    )
    (net (code "282") (name "unconnected-(IMU-AUX_CL-Pad7)") (class "Default")
      (node (ref "IMU") (pin "7") (pinfunction "AUX_CL_7") (pintype "bidirectional"))
    )
    (net (code "283") (name "unconnected-(IMU-AUX_DA-Pad21)") (class "Default")
      (node (ref "IMU") (pin "21") (pinfunction "AUX_DA_21") (pintype "bidirectional"))
    )
    (net (code "284") (name "unconnected-(IMU-FSYNC-Pad11)") (class "Default")
      (node (ref "IMU") (pin "11") (pinfunction "FSYNC_11") (pintype "bidirectional"))
    )
    (net (code "285") (name "unconnected-(IMU-NC-Pad2)") (class "Default")
      (node (ref "IMU") (pin "2") (pinfunction "NC_2") (pintype "bidirectional"))
    )
    (net (code "286") (name "unconnected-(IMU-NC-Pad3)") (class "Default")
      (node (ref "IMU") (pin "3") (pinfunction "NC_3") (pintype "bidirectional"))
    )
    (net (code "287") (name "unconnected-(IMU-NC-Pad4)") (class "Default")
      (node (ref "IMU") (pin "4") (pinfunction "NC_4") (pintype "bidirectional"))
    )
    (net (code "288") (name "unconnected-(IMU-NC-Pad5)") (class "Default")
      (node (ref "IMU") (pin "5") (pinfunction "NC_5") (pintype "bidirectional"))
    )
    (net (code "289") (name "unconnected-(IMU-NC-Pad6)") (class "Default")
      (node (ref "IMU") (pin "6") (pinfunction "NC_6") (pintype "bidirectional"))
    )
    (net (code "290") (name "unconnected-(IMU-NC-Pad14)") (class "Default")
      (node (ref "IMU") (pin "14") (pinfunction "NC_14") (pintype "bidirectional"))
    )
    (net (code "291") (name "unconnected-(IMU-NC-Pad15)") (class "Default")
      (node (ref "IMU") (pin "15") (pinfunction "NC_15") (pintype "bidirectional"))
    )
    (net (code "292") (name "unconnected-(IMU-NC-Pad16)") (class "Default")
      (node (ref "IMU") (pin "16") (pinfunction "NC_16") (pintype "bidirectional"))
    )
    (net (code "293") (name "unconnected-(IMU-NC-Pad17)") (class "Default")
      (node (ref "IMU") (pin "17") (pinfunction "NC_17") (pintype "bidirectional"))
    )
    (net (code "294") (name "unconnected-(IMU-RESV-Pad19)") (class "Default")
      (node (ref "IMU") (pin "19") (pinfunction "RESV_19") (pintype "bidirectional"))
    )
    (net (code "295") (name "unconnected-(PROT-CO-Pad3)") (class "Default")
      (node (ref "PROT") (pin "3") (pinfunction "CO_3") (pintype "bidirectional"))
    )
    (net (code "296") (name "unconnected-(PROT-DP-Pad4)") (class "Default")
      (node (ref "PROT") (pin "4") (pinfunction "DP_4") (pintype "bidirectional"))
    )
    (net (code "297") (name "unconnected-(SIPA-BAT_TEMP-PadW1)") (class "Default")
      (node (ref "SIP") (pin "W1") (pinfunction "BAT_TEMP_W1") (pintype "bidirectional"))
    )
    (net (code "298") (name "unconnected-(SIPA-BAT_VOLT-PadY1)") (class "Default")
      (node (ref "SIP") (pin "Y1") (pinfunction "BAT_VOLT_Y1") (pintype "bidirectional"))
    )
    (net (code "299") (name "unconnected-(SIPA-L1_IN-PadY14)") (class "Default")
      (node (ref "SIP") (pin "Y14") (pinfunction "L1_IN_Y14") (pintype "bidirectional"))
    )
    (net (code "300") (name "unconnected-(SIPA-L1_OUT-PadY13)") (class "Default")
      (node (ref "SIP") (pin "Y13") (pinfunction "L1_OUT_Y13") (pintype "bidirectional"))
    )
    (net (code "301") (name "unconnected-(SIPA-L2_IN-PadY17)") (class "Default")
      (node (ref "SIP") (pin "Y17") (pinfunction "L2_IN_Y17") (pintype "bidirectional"))
    )
    (net (code "302") (name "unconnected-(SIPA-L2_OUT-PadY16)") (class "Default")
      (node (ref "SIP") (pin "Y16") (pinfunction "L2_OUT_Y16") (pintype "bidirectional"))
    )
    (net (code "303") (name "unconnected-(SIPA-L3_IN-PadY20)") (class "Default")
      (node (ref "SIP") (pin "Y20") (pinfunction "L3_IN_Y20") (pintype "bidirectional"))
    )
    (net (code "304") (name "unconnected-(SIPA-L3_OUT-PadY19)") (class "Default")
      (node (ref "SIP") (pin "Y19") (pinfunction "L3_OUT_Y19") (pintype "bidirectional"))
    )
    (net (code "305") (name "unconnected-(SIPC-AIN4-PadC8)") (class "Default")
      (node (ref "SIP") (pin "C8") (pinfunction "AIN4_C8") (pintype "bidirectional"))
    )
    (net (code "306") (name "unconnected-(SIPC-USB0_CE-PadM15)") (class "Default")
      (node (ref "SIP") (pin "M15") (pinfunction "USB0_CE_M15") (pintype "bidirectional"))
    )
    (net (code "307") (name "unconnected-(SIPC-USB0_DRVVBUS-PadF16)") (class "Default")
      (node (ref "SIP") (pin "F16") (pinfunction "USB0_DRVVBUS_F16") (pintype "bidirectional"))
    )
    (net (code "308") (name "unconnected-(SIPC-USB1_CE-PadP18)") (class "Default")
      (node (ref "SIP") (pin "P18") (pinfunction "USB1_CE_P18") (pintype "bidirectional"))
    )
    (net (code "309") (name "unconnected-(SIPC-USB1_DRVVBUS-PadF15)") (class "Default")
      (node (ref "SIP") (pin "F15") (pinfunction "USB1_DRVVBUS_F15") (pintype "bidirectional"))
    )
    (net (code "310") (name "unconnected-(SIPD-NC1-PadV11)") (class "Default")
      (node (ref "SIP") (pin "V11") (pinfunction "NC1_V11") (pintype "bidirectional"))
    )
    (net (code "311") (name "unconnected-(SIPD-NC2-PadU11)") (class "Default")
      (node (ref "SIP") (pin "U11") (pinfunction "NC2_U11") (pintype "bidirectional"))
    )
    (net (code "312") (name "unconnected-(SIPD-NC3-PadV10)") (class "Default")
      (node (ref "SIP") (pin "V10") (pinfunction "NC3_V10") (pintype "bidirectional"))
    )
    (net (code "313") (name "unconnected-(SIPD-NC4-PadB1)") (class "Default")
      (node (ref "SIP") (pin "B1") (pinfunction "NC4_B1") (pintype "bidirectional"))
    )
    (net (code "314") (name "unconnected-(SIPD-NC5-PadB2)") (class "Default")
      (node (ref "SIP") (pin "B2") (pinfunction "NC5_B2") (pintype "bidirectional"))
    )
    (net (code "315") (name "unconnected-(SIPD-NC6-PadB3)") (class "Default")
      (node (ref "SIP") (pin "B3") (pinfunction "NC6_B3") (pintype "bidirectional"))
    )
    (net (code "316") (name "unconnected-(SIPD-NC12-PadC1)") (class "Default")
      (node (ref "SIP") (pin "C1") (pinfunction "NC12_C1") (pintype "bidirectional"))
    )
    (net (code "317") (name "unconnected-(SIPD-NC20-PadC2)") (class "Default")
      (node (ref "SIP") (pin "C2") (pinfunction "NC20_C2") (pintype "bidirectional"))
    )
    (net (code "318") (name "unconnected-(SIPD-NC21-PadC3)") (class "Default")
      (node (ref "SIP") (pin "C3") (pinfunction "NC21_C3") (pintype "bidirectional"))
    )
    (net (code "319") (name "unconnected-(SIPD-NC22-PadC4)") (class "Default")
      (node (ref "SIP") (pin "C4") (pinfunction "NC22_C4") (pintype "bidirectional"))
    )
    (net (code "320") (name "unconnected-(SIPD-NC23-PadP2)") (class "Default")
      (node (ref "SIP") (pin "P2") (pinfunction "NC23_P2") (pintype "bidirectional"))
    )
    (net (code "321") (name "unconnected-(SIPD-NC24-PadD1)") (class "Default")
      (node (ref "SIP") (pin "D1") (pinfunction "NC24_D1") (pintype "bidirectional"))
    )
    (net (code "322") (name "unconnected-(SIPD-NC31-PadD2)") (class "Default")
      (node (ref "SIP") (pin "D2") (pinfunction "NC31_D2") (pintype "bidirectional"))
    )
    (net (code "323") (name "unconnected-(SIPD-NC32-PadD3)") (class "Default")
      (node (ref "SIP") (pin "D3") (pinfunction "NC32_D3") (pintype "bidirectional"))
    )
    (net (code "324") (name "unconnected-(SIPD-NC33-PadD4)") (class "Default")
      (node (ref "SIP") (pin "D4") (pinfunction "NC33_D4") (pintype "bidirectional"))
    )
    (net (code "325") (name "unconnected-(SIPD-NC34-PadD5)") (class "Default")
      (node (ref "SIP") (pin "D5") (pinfunction "NC34_D5") (pintype "bidirectional"))
    )
    (net (code "326") (name "unconnected-(SIPD-NC45-PadP3)") (class "Default")
      (node (ref "SIP") (pin "P3") (pinfunction "NC45_P3") (pintype "bidirectional"))
    )
    (net (code "327") (name "unconnected-(SIPD-NC46-PadE1)") (class "Default")
      (node (ref "SIP") (pin "E1") (pinfunction "NC46_E1") (pintype "bidirectional"))
    )
    (net (code "328") (name "unconnected-(SIPD-NC47-PadE2)") (class "Default")
      (node (ref "SIP") (pin "E2") (pinfunction "NC47_E2") (pintype "bidirectional"))
    )
    (net (code "329") (name "unconnected-(SIPD-NC48-PadE3)") (class "Default")
      (node (ref "SIP") (pin "E3") (pinfunction "NC48_E3") (pintype "bidirectional"))
    )
    (net (code "330") (name "unconnected-(SIPD-NC58-PadE4)") (class "Default")
      (node (ref "SIP") (pin "E4") (pinfunction "NC58_E4") (pintype "bidirectional"))
    )
    (net (code "331") (name "unconnected-(SIPD-NC59-PadF1)") (class "Default")
      (node (ref "SIP") (pin "F1") (pinfunction "NC59_F1") (pintype "bidirectional"))
    )
    (net (code "332") (name "unconnected-(SIPD-NC60-PadF2)") (class "Default")
      (node (ref "SIP") (pin "F2") (pinfunction "NC60_F2") (pintype "bidirectional"))
    )
    (net (code "333") (name "unconnected-(SIPD-NC61-PadF3)") (class "Default")
      (node (ref "SIP") (pin "F3") (pinfunction "NC61_F3") (pintype "bidirectional"))
    )
    (net (code "334") (name "unconnected-(SIPD-NC68-PadF4)") (class "Default")
      (node (ref "SIP") (pin "F4") (pinfunction "NC68_F4") (pintype "bidirectional"))
    )
    (net (code "335") (name "unconnected-(SIPD-NC69-PadG1)") (class "Default")
      (node (ref "SIP") (pin "G1") (pinfunction "NC69_G1") (pintype "bidirectional"))
    )
    (net (code "336") (name "unconnected-(SIPD-NC70-PadG2)") (class "Default")
      (node (ref "SIP") (pin "G2") (pinfunction "NC70_G2") (pintype "bidirectional"))
    )
    (net (code "337") (name "unconnected-(SIPD-NC71-PadG3)") (class "Default")
      (node (ref "SIP") (pin "G3") (pinfunction "NC71_G3") (pintype "bidirectional"))
    )
    (net (code "338") (name "unconnected-(SIPD-NC76-PadG4)") (class "Default")
      (node (ref "SIP") (pin "G4") (pinfunction "NC76_G4") (pintype "bidirectional"))
    )
    (net (code "339") (name "unconnected-(SIPD-NC77-PadH1)") (class "Default")
      (node (ref "SIP") (pin "H1") (pinfunction "NC77_H1") (pintype "bidirectional"))
    )
    (net (code "340") (name "unconnected-(SIPD-NC78-PadH2)") (class "Default")
      (node (ref "SIP") (pin "H2") (pinfunction "NC78_H2") (pintype "bidirectional"))
    )
    (net (code "341") (name "unconnected-(SIPD-NC79-PadH3)") (class "Default")
      (node (ref "SIP") (pin "H3") (pinfunction "NC79_H3") (pintype "bidirectional"))
    )
    (net (code "342") (name "unconnected-(SIPD-NC84-PadH4)") (class "Default")
      (node (ref "SIP") (pin "H4") (pinfunction "NC84_H4") (pintype "bidirectional"))
    )
    (net (code "343") (name "unconnected-(SIPD-NC85-PadJ1)") (class "Default")
      (node (ref "SIP") (pin "J1") (pinfunction "NC85_J1") (pintype "bidirectional"))
    )
    (net (code "344") (name "unconnected-(SIPD-NC86-PadJ2)") (class "Default")
      (node (ref "SIP") (pin "J2") (pinfunction "NC86_J2") (pintype "bidirectional"))
    )
    (net (code "345") (name "unconnected-(SIPD-NC87-PadJ3)") (class "Default")
      (node (ref "SIP") (pin "J3") (pinfunction "NC87_J3") (pintype "bidirectional"))
    )
    (net (code "346") (name "unconnected-(SIPD-NC94-PadJ4)") (class "Default")
      (node (ref "SIP") (pin "J4") (pinfunction "NC94_J4") (pintype "bidirectional"))
    )
    (net (code "347") (name "unconnected-(SIPD-NC95-PadK1)") (class "Default")
      (node (ref "SIP") (pin "K1") (pinfunction "NC95_K1") (pintype "bidirectional"))
    )
    (net (code "348") (name "unconnected-(SIPD-NC96-PadK2)") (class "Default")
      (node (ref "SIP") (pin "K2") (pinfunction "NC96_K2") (pintype "bidirectional"))
    )
    (net (code "349") (name "unconnected-(SIPD-NC97-PadK3)") (class "Default")
      (node (ref "SIP") (pin "K3") (pinfunction "NC97_K3") (pintype "bidirectional"))
    )
    (net (code "350") (name "unconnected-(SIPD-NC104-PadK4)") (class "Default")
      (node (ref "SIP") (pin "K4") (pinfunction "NC104_K4") (pintype "bidirectional"))
    )
    (net (code "351") (name "unconnected-(SIPD-NC105-PadL1)") (class "Default")
      (node (ref "SIP") (pin "L1") (pinfunction "NC105_L1") (pintype "bidirectional"))
    )
    (net (code "352") (name "unconnected-(SIPD-NC106-PadL2)") (class "Default")
      (node (ref "SIP") (pin "L2") (pinfunction "NC106_L2") (pintype "bidirectional"))
    )
    (net (code "353") (name "unconnected-(SIPD-NC107-PadL3)") (class "Default")
      (node (ref "SIP") (pin "L3") (pinfunction "NC107_L3") (pintype "bidirectional"))
    )
    (net (code "354") (name "unconnected-(SIPD-NC111-PadL4)") (class "Default")
      (node (ref "SIP") (pin "L4") (pinfunction "NC111_L4") (pintype "bidirectional"))
    )
    (net (code "355") (name "unconnected-(SIPD-NC112-PadM1)") (class "Default")
      (node (ref "SIP") (pin "M1") (pinfunction "NC112_M1") (pintype "bidirectional"))
    )
    (net (code "356") (name "unconnected-(SIPD-NC113-PadM2)") (class "Default")
      (node (ref "SIP") (pin "M2") (pinfunction "NC113_M2") (pintype "bidirectional"))
    )
    (net (code "357") (name "unconnected-(SIPD-NC114-PadM3)") (class "Default")
      (node (ref "SIP") (pin "M3") (pinfunction "NC114_M3") (pintype "bidirectional"))
    )
    (net (code "358") (name "unconnected-(SIPD-NC121-PadM4)") (class "Default")
      (node (ref "SIP") (pin "M4") (pinfunction "NC121_M4") (pintype "bidirectional"))
    )
    (net (code "359") (name "unconnected-(SIPD-NC122-PadP4)") (class "Default")
      (node (ref "SIP") (pin "P4") (pinfunction "NC122_P4") (pintype "bidirectional"))
    )
    (net (code "360") (name "unconnected-(SIPD-NC123-PadN1)") (class "Default")
      (node (ref "SIP") (pin "N1") (pinfunction "NC123_N1") (pintype "bidirectional"))
    )
    (net (code "361") (name "unconnected-(SIPD-NC124-PadN2)") (class "Default")
      (node (ref "SIP") (pin "N2") (pinfunction "NC124_N2") (pintype "bidirectional"))
    )
    (net (code "362") (name "unconnected-(SIPD-NC136-PadN3)") (class "Default")
      (node (ref "SIP") (pin "N3") (pinfunction "NC136_N3") (pintype "bidirectional"))
    )
    (net (code "363") (name "unconnected-(SIPD-NC137-PadN4)") (class "Default")
      (node (ref "SIP") (pin "N4") (pinfunction "NC137_N4") (pintype "bidirectional"))
    )
    (net (code "364") (name "unconnected-(SIPD-NC138-PadP1)") (class "Default")
      (node (ref "SIP") (pin "P1") (pinfunction "NC138_P1") (pintype "bidirectional"))
    )
    (net (code "365") (name "unconnected-(SIPE-CAP_VBB_MPU-PadC10)") (class "Default")
      (node (ref "SIP") (pin "C10") (pinfunction "CAP_VBB_MPU_C10") (pintype "bidirectional"))
    )
    (net (code "366") (name "unconnected-(SIPE-CAP_VDD_RTC-PadD6)") (class "Default")
      (node (ref "SIP") (pin "D6") (pinfunction "CAP_VDD_RTC_D6") (pintype "bidirectional"))
    )
    (net (code "367") (name "unconnected-(SIPE-CAP_VDD_SRAM_COR-PadD9)") (class "Default")
      (node (ref "SIP") (pin "D9") (pinfunction "CAP_VDD_SRAM_COR_D9") (pintype "bidirectional"))
    )
    (net (code "368") (name "unconnected-(SIPE-CAP_VDD_SRAM_MPU-PadD11)") (class "Default")
      (node (ref "SIP") (pin "D11") (pinfunction "CAP_VDD_SRAM_MPU_D11") (pintype "bidirectional"))
    )
    (net (code "369") (name "unconnected-(SIPE-TESTOUT-PadA3)") (class "Default")
      (node (ref "SIP") (pin "A3") (pinfunction "TESTOUT_A3") (pintype "bidirectional"))
    )
    (net (code "370") (name "unconnected-(SIPE-VDDS_DDR1-PadE5)") (class "Default")
      (node (ref "SIP") (pin "E5") (pinfunction "VDDS_DDR1_E5") (pintype "bidirectional"))
    )
    (net (code "371") (name "unconnected-(SIPE-VDDS_DDR2-PadF5)") (class "Default")
      (node (ref "SIP") (pin "F5") (pinfunction "VDDS_DDR2_F5") (pintype "bidirectional"))
    )
    (net (code "372") (name "unconnected-(SIPE-VDDS_DDR3-PadG5)") (class "Default")
      (node (ref "SIP") (pin "G5") (pinfunction "VDDS_DDR3_G5") (pintype "bidirectional"))
    )
    (net (code "373") (name "unconnected-(SIPE-VDDS_DDR4-PadH5)") (class "Default")
      (node (ref "SIP") (pin "H5") (pinfunction "VDDS_DDR4_H5") (pintype "bidirectional"))
    )
    (net (code "374") (name "unconnected-(SIPE-VDDS_DDR5-PadJ5)") (class "Default")
      (node (ref "SIP") (pin "J5") (pinfunction "VDDS_DDR5_J5") (pintype "bidirectional"))
    )
    (net (code "375") (name "unconnected-(SIPE-VDDS_DDR6-PadK5)") (class "Default")
      (node (ref "SIP") (pin "K5") (pinfunction "VDDS_DDR6_K5") (pintype "bidirectional"))
    )
    (net (code "376") (name "unconnected-(SIPE-VDDS_DDR7-PadL5)") (class "Default")
      (node (ref "SIP") (pin "L5") (pinfunction "VDDS_DDR7_L5") (pintype "bidirectional"))
    )
    (net (code "377") (name "unconnected-(SIPE-VDD_3V3A1-PadE10)") (class "Default")
      (node (ref "SIP") (pin "E10") (pinfunction "VDD_3V3A1_E10") (pintype "bidirectional"))
    )
    (net (code "378") (name "unconnected-(SIPE-VDD_3V3A2-PadE11)") (class "Default")
      (node (ref "SIP") (pin "E11") (pinfunction "VDD_3V3A2_E11") (pintype "bidirectional"))
    )
    (net (code "379") (name "unconnected-(SIPE-VDD_3V3A3-PadE12)") (class "Default")
      (node (ref "SIP") (pin "E12") (pinfunction "VDD_3V3A3_E12") (pintype "bidirectional"))
    )
    (net (code "380") (name "unconnected-(SIPE-VDD_3V3A4-PadE13)") (class "Default")
      (node (ref "SIP") (pin "E13") (pinfunction "VDD_3V3A4_E13") (pintype "bidirectional"))
    )
    (net (code "381") (name "unconnected-(SIPE-VDD_3V3A5-PadF14)") (class "Default")
      (node (ref "SIP") (pin "F14") (pinfunction "VDD_3V3A5_F14") (pintype "bidirectional"))
    )
    (net (code "382") (name "unconnected-(SIPE-VDD_3V3A6-PadG14)") (class "Default")
      (node (ref "SIP") (pin "G14") (pinfunction "VDD_3V3A6_G14") (pintype "bidirectional"))
    )
    (net (code "383") (name "unconnected-(SIPE-VDD_3V3A7-PadH14)") (class "Default")
      (node (ref "SIP") (pin "H14") (pinfunction "VDD_3V3A7_H14") (pintype "bidirectional"))
    )
    (net (code "384") (name "unconnected-(SIPE-VDD_3V3A8-PadJ14)") (class "Default")
      (node (ref "SIP") (pin "J14") (pinfunction "VDD_3V3A8_J14") (pintype "bidirectional"))
    )
    (net (code "385") (name "unconnected-(SIPE-VDD_3V3A9-PadK14)") (class "Default")
      (node (ref "SIP") (pin "K14") (pinfunction "VDD_3V3A9_K14") (pintype "bidirectional"))
    )
    (net (code "386") (name "unconnected-(SIPE-VDD_3V3A10-PadL14)") (class "Default")
      (node (ref "SIP") (pin "L14") (pinfunction "VDD_3V3A10_L14") (pintype "bidirectional"))
    )
    (net (code "387") (name "unconnected-(SIPE-VDD_3V3A11-PadN5)") (class "Default")
      (node (ref "SIP") (pin "N5") (pinfunction "VDD_3V3A11_N5") (pintype "bidirectional"))
    )
    (net (code "388") (name "unconnected-(SIPE-VDD_3V3A12-PadN15)") (class "Default")
      (node (ref "SIP") (pin "N15") (pinfunction "VDD_3V3A12_N15") (pintype "bidirectional"))
    )
    (net (code "389") (name "unconnected-(SIPE-VDD_3V3A13-PadP5)") (class "Default")
      (node (ref "SIP") (pin "P5") (pinfunction "VDD_3V3A13_P5") (pintype "bidirectional"))
    )
    (net (code "390") (name "unconnected-(SIPE-VDD_3V3A14-PadP6)") (class "Default")
      (node (ref "SIP") (pin "P6") (pinfunction "VDD_3V3A14_P6") (pintype "bidirectional"))
    )
    (net (code "391") (name "unconnected-(SIPE-VDD_3V3A15-PadP7)") (class "Default")
      (node (ref "SIP") (pin "P7") (pinfunction "VDD_3V3A15_P7") (pintype "bidirectional"))
    )
    (net (code "392") (name "unconnected-(SIPE-VDD_3V3A16-PadP8)") (class "Default")
      (node (ref "SIP") (pin "P8") (pinfunction "VDD_3V3A16_P8") (pintype "bidirectional"))
    )
    (net (code "393") (name "unconnected-(SIPE-VDD_3V3A17-PadP10)") (class "Default")
      (node (ref "SIP") (pin "P10") (pinfunction "VDD_3V3A17_P10") (pintype "bidirectional"))
    )
    (net (code "394") (name "unconnected-(SIPE-VDD_3V3A18-PadP11)") (class "Default")
      (node (ref "SIP") (pin "P11") (pinfunction "VDD_3V3A18_P11") (pintype "bidirectional"))
    )
    (net (code "395") (name "unconnected-(SIPE-VDD_3V3A19-PadP12)") (class "Default")
      (node (ref "SIP") (pin "P12") (pinfunction "VDD_3V3A19_P12") (pintype "bidirectional"))
    )
    (net (code "396") (name "unconnected-(SIPE-VDD_3V3A20-PadP13)") (class "Default")
      (node (ref "SIP") (pin "P13") (pinfunction "VDD_3V3A20_P13") (pintype "bidirectional"))
    )
    (net (code "397") (name "unconnected-(SIPE-VDD_3V3A21-PadR15)") (class "Default")
      (node (ref "SIP") (pin "R15") (pinfunction "VDD_3V3A21_R15") (pintype "bidirectional"))
    )
    (net (code "398") (name "unconnected-(SIPE-VDD_CORE1-PadF6)") (class "Default")
      (node (ref "SIP") (pin "F6") (pinfunction "VDD_CORE1_F6") (pintype "bidirectional"))
    )
    (net (code "399") (name "unconnected-(SIPE-VDD_CORE2-PadF7)") (class "Default")
      (node (ref "SIP") (pin "F7") (pinfunction "VDD_CORE2_F7") (pintype "bidirectional"))
    )
    (net (code "400") (name "unconnected-(SIPE-VDD_CORE3-PadG6)") (class "Default")
      (node (ref "SIP") (pin "G6") (pinfunction "VDD_CORE3_G6") (pintype "bidirectional"))
    )
    (net (code "401") (name "unconnected-(SIPE-VDD_CORE4-PadG7)") (class "Default")
      (node (ref "SIP") (pin "G7") (pinfunction "VDD_CORE4_G7") (pintype "bidirectional"))
    )
    (net (code "402") (name "unconnected-(SIPE-VDD_CORE5-PadG10)") (class "Default")
      (node (ref "SIP") (pin "G10") (pinfunction "VDD_CORE5_G10") (pintype "bidirectional"))
    )
    (net (code "403") (name "unconnected-(SIPE-VDD_CORE6-PadH11)") (class "Default")
      (node (ref "SIP") (pin "H11") (pinfunction "VDD_CORE6_H11") (pintype "bidirectional"))
    )
    (net (code "404") (name "unconnected-(SIPE-VDD_CORE7-PadJ12)") (class "Default")
      (node (ref "SIP") (pin "J12") (pinfunction "VDD_CORE7_J12") (pintype "bidirectional"))
    )
    (net (code "405") (name "unconnected-(SIPE-VDD_CORE8-PadK6)") (class "Default")
      (node (ref "SIP") (pin "K6") (pinfunction "VDD_CORE8_K6") (pintype "bidirectional"))
    )
    (net (code "406") (name "unconnected-(SIPE-VDD_CORE9-PadK8)") (class "Default")
      (node (ref "SIP") (pin "K8") (pinfunction "VDD_CORE9_K8") (pintype "bidirectional"))
    )
    (net (code "407") (name "unconnected-(SIPE-VDD_CORE10-PadK12)") (class "Default")
      (node (ref "SIP") (pin "K12") (pinfunction "VDD_CORE10_K12") (pintype "bidirectional"))
    )
    (net (code "408") (name "unconnected-(SIPE-VDD_CORE11-PadL6)") (class "Default")
      (node (ref "SIP") (pin "L6") (pinfunction "VDD_CORE11_L6") (pintype "bidirectional"))
    )
    (net (code "409") (name "unconnected-(SIPE-VDD_CORE12-PadL7)") (class "Default")
      (node (ref "SIP") (pin "L7") (pinfunction "VDD_CORE12_L7") (pintype "bidirectional"))
    )
    (net (code "410") (name "unconnected-(SIPE-VDD_CORE13-PadL8)") (class "Default")
      (node (ref "SIP") (pin "L8") (pinfunction "VDD_CORE13_L8") (pintype "bidirectional"))
    )
    (net (code "411") (name "unconnected-(SIPE-VDD_CORE14-PadL9)") (class "Default")
      (node (ref "SIP") (pin "L9") (pinfunction "VDD_CORE14_L9") (pintype "bidirectional"))
    )
    (net (code "412") (name "unconnected-(SIPE-VDD_CORE15-PadM11)") (class "Default")
      (node (ref "SIP") (pin "M11") (pinfunction "VDD_CORE15_M11") (pintype "bidirectional"))
    )
    (net (code "413") (name "unconnected-(SIPE-VDD_CORE16-PadM13)") (class "Default")
      (node (ref "SIP") (pin "M13") (pinfunction "VDD_CORE16_M13") (pintype "bidirectional"))
    )
    (net (code "414") (name "unconnected-(SIPE-VDD_CORE17-PadN8)") (class "Default")
      (node (ref "SIP") (pin "N8") (pinfunction "VDD_CORE17_N8") (pintype "bidirectional"))
    )
    (net (code "415") (name "unconnected-(SIPE-VDD_CORE18-PadN9)") (class "Default")
      (node (ref "SIP") (pin "N9") (pinfunction "VDD_CORE18_N9") (pintype "bidirectional"))
    )
    (net (code "416") (name "unconnected-(SIPE-VDD_CORE19-PadN12)") (class "Default")
      (node (ref "SIP") (pin "N12") (pinfunction "VDD_CORE19_N12") (pintype "bidirectional"))
    )
    (net (code "417") (name "unconnected-(SIPE-VDD_CORE20-PadN13)") (class "Default")
      (node (ref "SIP") (pin "N13") (pinfunction "VDD_CORE20_N13") (pintype "bidirectional"))
    )
    (net (code "418") (name "unconnected-(SIPE-VDD_MPU0-PadF10)") (class "Default")
      (node (ref "SIP") (pin "F10") (pinfunction "VDD_MPU0_F10") (pintype "bidirectional"))
    )
    (net (code "419") (name "unconnected-(SIPE-VDD_MPU1-PadF11)") (class "Default")
      (node (ref "SIP") (pin "F11") (pinfunction "VDD_MPU1_F11") (pintype "bidirectional"))
    )
    (net (code "420") (name "unconnected-(SIPE-VDD_MPU2-PadF12)") (class "Default")
      (node (ref "SIP") (pin "F12") (pinfunction "VDD_MPU2_F12") (pintype "bidirectional"))
    )
    (net (code "421") (name "unconnected-(SIPE-VDD_MPU3-PadF13)") (class "Default")
      (node (ref "SIP") (pin "F13") (pinfunction "VDD_MPU3_F13") (pintype "bidirectional"))
    )
    (net (code "422") (name "unconnected-(SIPE-VDD_MPU4-PadG13)") (class "Default")
      (node (ref "SIP") (pin "G13") (pinfunction "VDD_MPU4_G13") (pintype "bidirectional"))
    )
    (net (code "423") (name "unconnected-(SIPE-VDD_MPU5-PadH13)") (class "Default")
      (node (ref "SIP") (pin "H13") (pinfunction "VDD_MPU5_H13") (pintype "bidirectional"))
    )
    (net (code "424") (name "unconnected-(SIPE-VDD_MPU6-PadJ13)") (class "Default")
      (node (ref "SIP") (pin "J13") (pinfunction "VDD_MPU6_J13") (pintype "bidirectional"))
    )
    (net (code "425") (name "unconnected-(SIPE-VDD_MPU_MON-PadA2)") (class "Default")
      (node (ref "SIP") (pin "A2") (pinfunction "VDD_MPU_MON_A2") (pintype "bidirectional"))
    )
    (net (code "426") (name "unconnected-(SIPE-VDD_PLL1-PadE7)") (class "Default")
      (node (ref "SIP") (pin "E7") (pinfunction "VDD_PLL1_E7") (pintype "bidirectional"))
    )
    (net (code "427") (name "unconnected-(SIPE-VDD_PLL2-PadH15)") (class "Default")
      (node (ref "SIP") (pin "H15") (pinfunction "VDD_PLL2_H15") (pintype "bidirectional"))
    )
    (net (code "428") (name "unconnected-(SIPE-VDD_PLL3-PadR10)") (class "Default")
      (node (ref "SIP") (pin "R10") (pinfunction "VDD_PLL3_R10") (pintype "bidirectional"))
    )
    (net (code "429") (name "unconnected-(SIPE-VDD_PLL4-PadR11)") (class "Default")
      (node (ref "SIP") (pin "R11") (pinfunction "VDD_PLL4_R11") (pintype "bidirectional"))
    )
    (net (code "430") (name "unconnected-(SIPE-VDD_RTC1-PadD7)") (class "Default")
      (node (ref "SIP") (pin "D7") (pinfunction "VDD_RTC1_D7") (pintype "bidirectional"))
    )
    (net (code "431") (name "unconnected-(SIPE-VDD_RTC2-PadE6)") (class "Default")
      (node (ref "SIP") (pin "E6") (pinfunction "VDD_RTC2_E6") (pintype "bidirectional"))
    )
    (net (code "432") (name "unconnected-(SIPE-VDD_RTC4-PadF9)") (class "Default")
      (node (ref "SIP") (pin "F9") (pinfunction "VDD_RTC4_F9") (pintype "bidirectional"))
    )
    (net (code "433") (name "unconnected-(SIPE-VDD_RTC5-PadK13)") (class "Default")
      (node (ref "SIP") (pin "K13") (pinfunction "VDD_RTC5_K13") (pintype "bidirectional"))
    )
    (net (code "434") (name "unconnected-(SIPE-VDD_RTC6-PadN6)") (class "Default")
      (node (ref "SIP") (pin "N6") (pinfunction "VDD_RTC6_N6") (pintype "bidirectional"))
    )
    (net (code "435") (name "unconnected-(SIPE-VDD_RTC7-PadP9)") (class "Default")
      (node (ref "SIP") (pin "P9") (pinfunction "VDD_RTC7_P9") (pintype "bidirectional"))
    )
    (net (code "436") (name "unconnected-(SIPE-VDD_RTC8-PadP14)") (class "Default")
      (node (ref "SIP") (pin "P14") (pinfunction "VDD_RTC8_P14") (pintype "bidirectional"))
    )
    (net (code "437") (name "unconnected-(SIPE-VPP-PadM5)") (class "Default")
      (node (ref "SIP") (pin "M5") (pinfunction "VPP_M5") (pintype "bidirectional"))
    )
    (net (code "438") (name "unconnected-(U3-NC-Pad5)") (class "Default")
      (node (ref "U3") (pin "5") (pinfunction "NC_5") (pintype "bidirectional"))
    )
    (net (code "439") (name "unconnected-(U4-ID-Pad3)") (class "Default")
      (node (ref "U4") (pin "3") (pinfunction "ID_3") (pintype "bidirectional"))
    )
    (net (code "440") (name "unconnected-(U4-NC-Pad5)") (class "Default")
      (node (ref "U4") (pin "5") (pinfunction "NC_5") (pintype "bidirectional"))
    )
    (net (code "441") (name "unconnected-(U6-NC-Pad1)") (class "Default")
      (node (ref "U6") (pin "1") (pinfunction "NC_1") (pintype "passive"))
    )
    (net (code "442") (name "unconnected-(U7-BT_UART_DBG-Pad43)") (class "Default")
      (node (ref "U7") (pin "43") (pinfunction "BT_UART_DBG_43") (pintype "bidirectional"))
    )
    (net (code "443") (name "unconnected-(U7-GPIO1-Pad27)") (class "Default")
      (node (ref "U7") (pin "27") (pinfunction "GPIO1_27") (pintype "bidirectional"))
    )
    (net (code "444") (name "unconnected-(U7-GPIO2-Pad26)") (class "Default")
      (node (ref "U7") (pin "26") (pinfunction "GPIO2_26") (pintype "bidirectional"))
    )
    (net (code "445") (name "unconnected-(U7-GPIO4-Pad25)") (class "Default")
      (node (ref "U7") (pin "25") (pinfunction "GPIO4_25") (pintype "bidirectional"))
    )
    (net (code "446") (name "unconnected-(U7-GPIO9-Pad3)") (class "Default")
      (node (ref "U7") (pin "3") (pinfunction "GPIO9_3") (pintype "bidirectional"))
    )
    (net (code "447") (name "unconnected-(U7-GPIO10-Pad4)") (class "Default")
      (node (ref "U7") (pin "4") (pinfunction "GPIO10_4") (pintype "bidirectional"))
    )
    (net (code "448") (name "unconnected-(U7-GPIO11-Pad2)") (class "Default")
      (node (ref "U7") (pin "2") (pinfunction "GPIO11_2") (pintype "bidirectional"))
    )
    (net (code "449") (name "unconnected-(U7-GPIO12-Pad5)") (class "Default")
      (node (ref "U7") (pin "5") (pinfunction "GPIO12_5") (pintype "bidirectional"))
    )
    (net (code "450") (name "unconnected-(U7-RESERVED1-Pad21)") (class "Default")
      (node (ref "U7") (pin "21") (pinfunction "RESERVED1_21") (pintype "bidirectional"))
    )
    (net (code "451") (name "unconnected-(U7-RESERVED2-Pad22)") (class "Default")
      (node (ref "U7") (pin "22") (pinfunction "RESERVED2_22") (pintype "bidirectional"))
    )
    (net (code "452") (name "unconnected-(U7-RESERVED3-Pad62)") (class "Default")
      (node (ref "U7") (pin "62") (pinfunction "RESERVED3_62") (pintype "bidirectional"))
    )
    (net (code "453") (name "unconnected-(U7-WL_UART_DBG-Pad42)") (class "Default")
      (node (ref "U7") (pin "42") (pinfunction "WL_UART_DBG_42") (pintype "bidirectional"))
    )
  )
)
